# PCB_KioskMB_r3_2.net
KiCad netlist of a schematic drawn in EAGLE
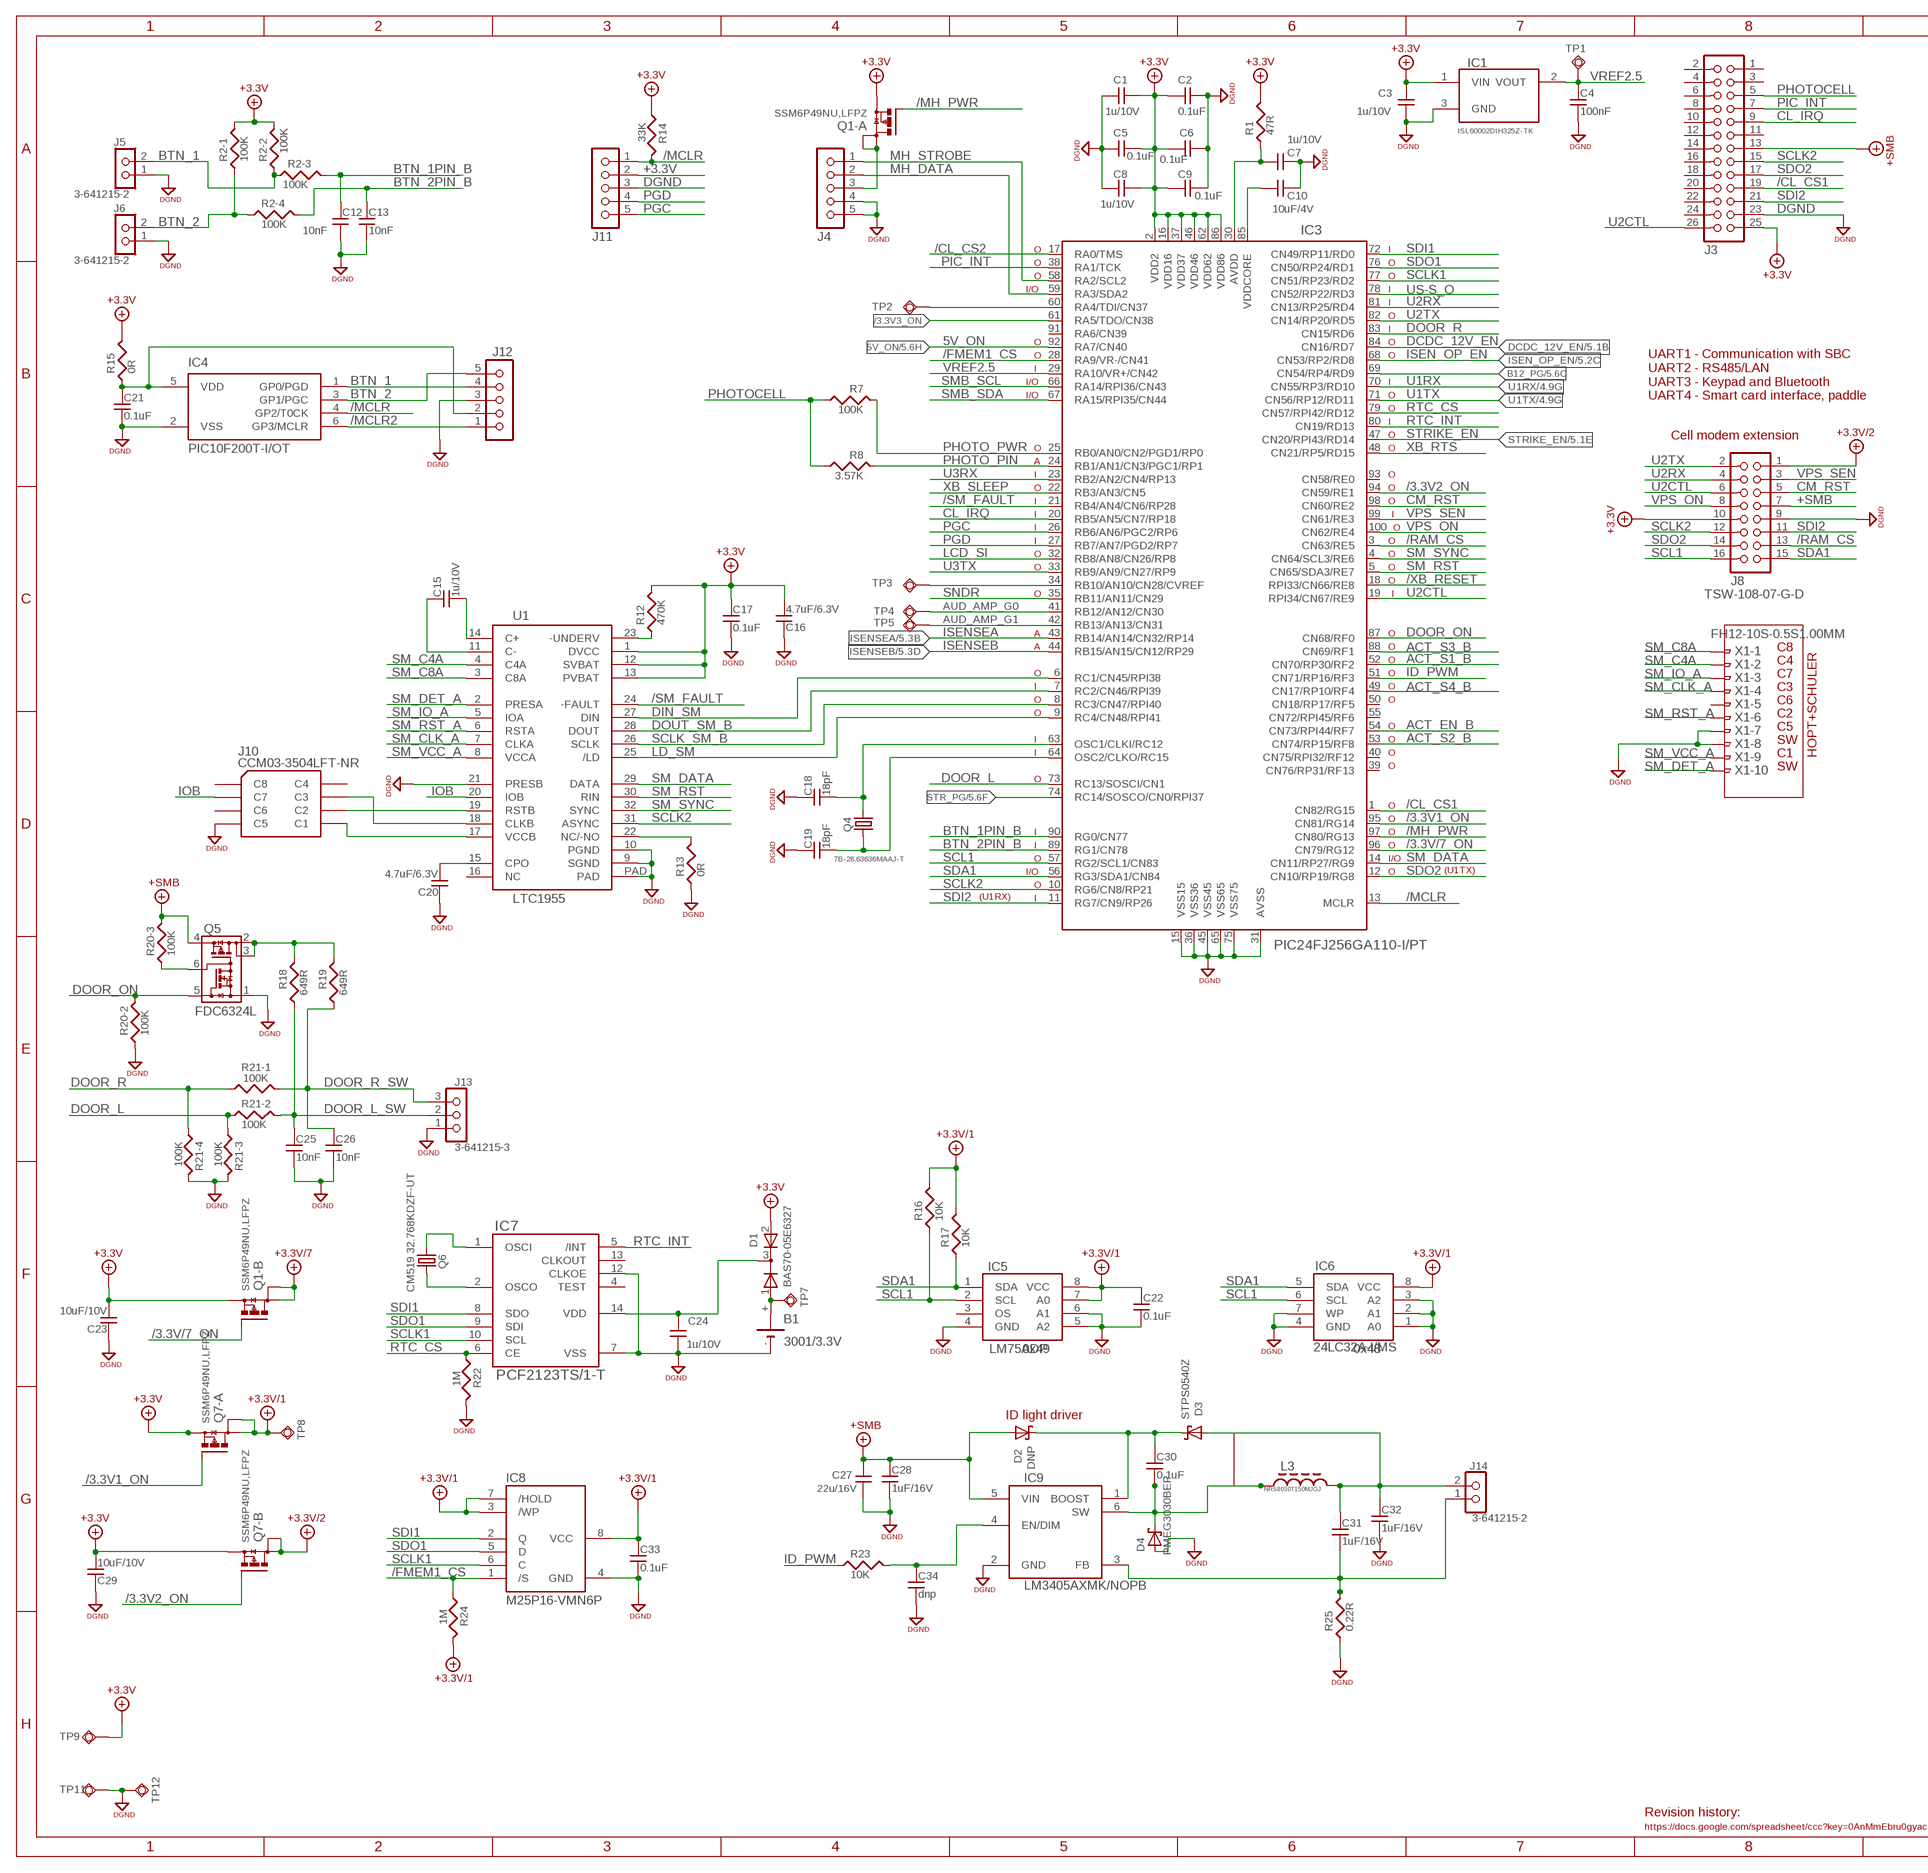
[diagram p0: schematic, sheet 1, part 1 of 2]
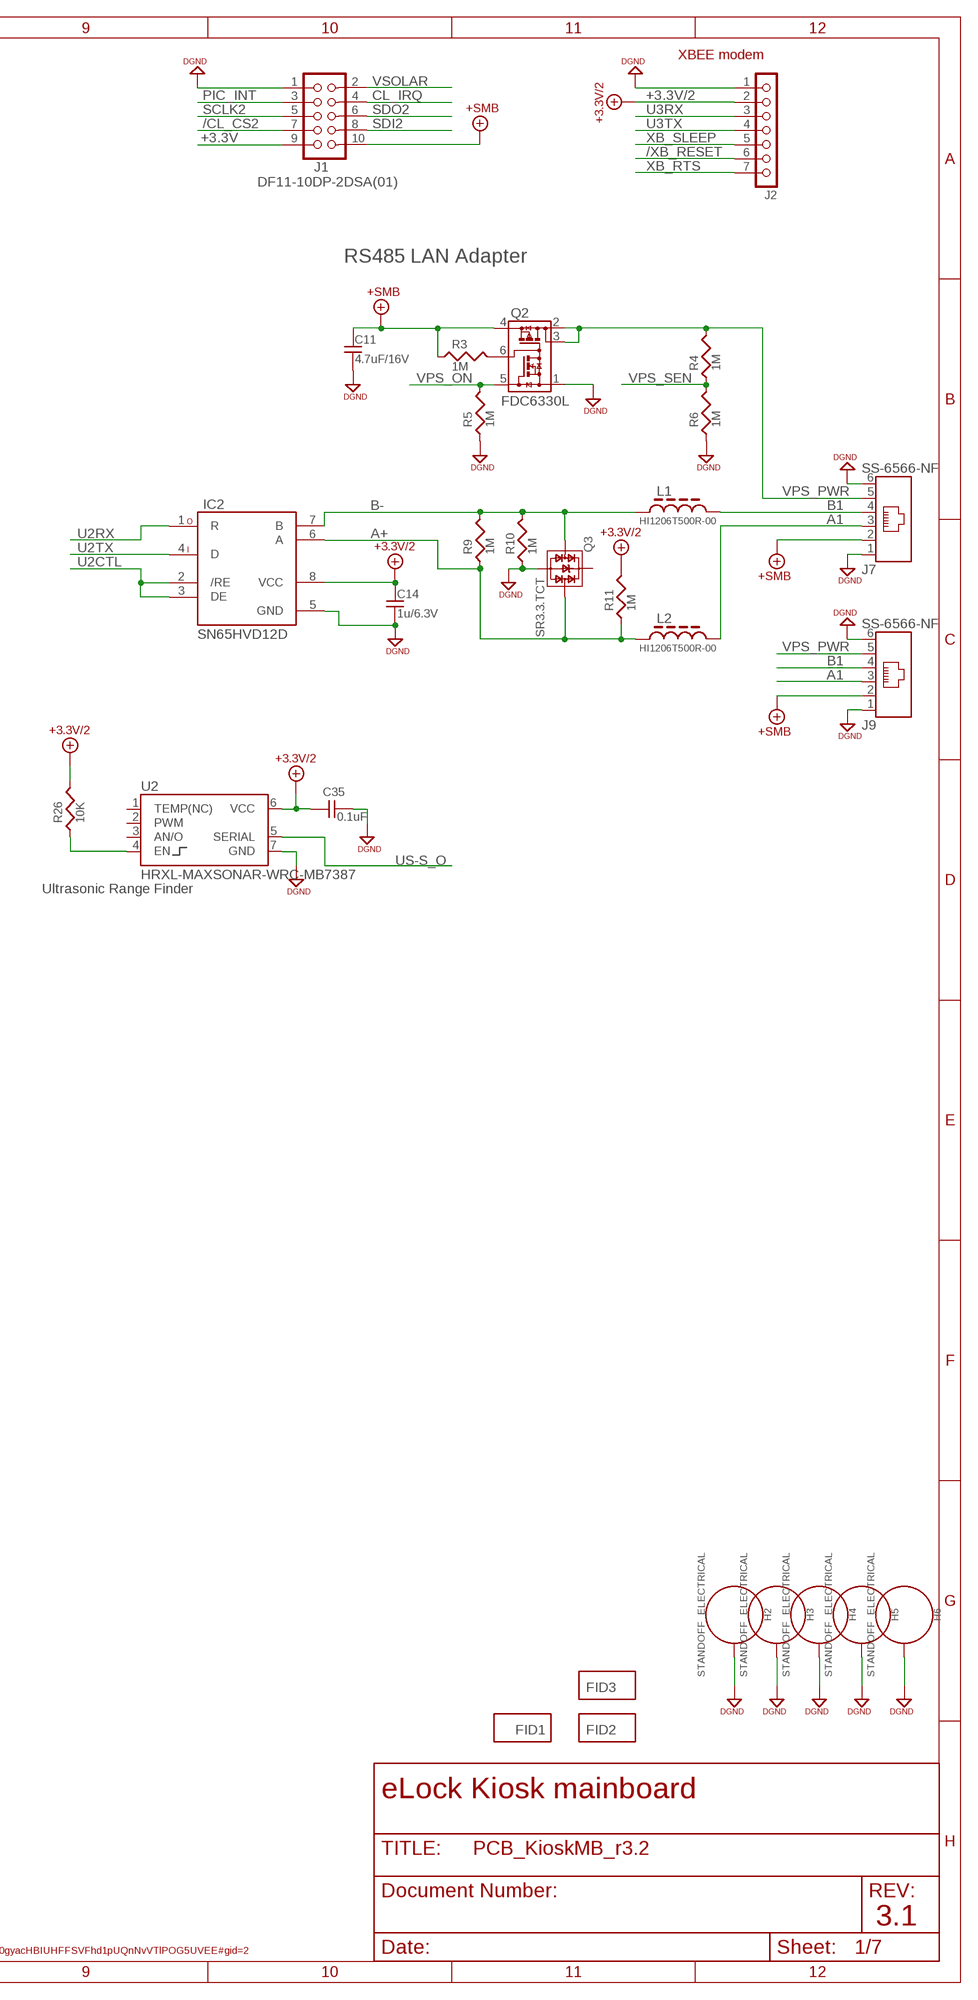
[diagram p1: schematic, sheet 1, part 2 of 2]
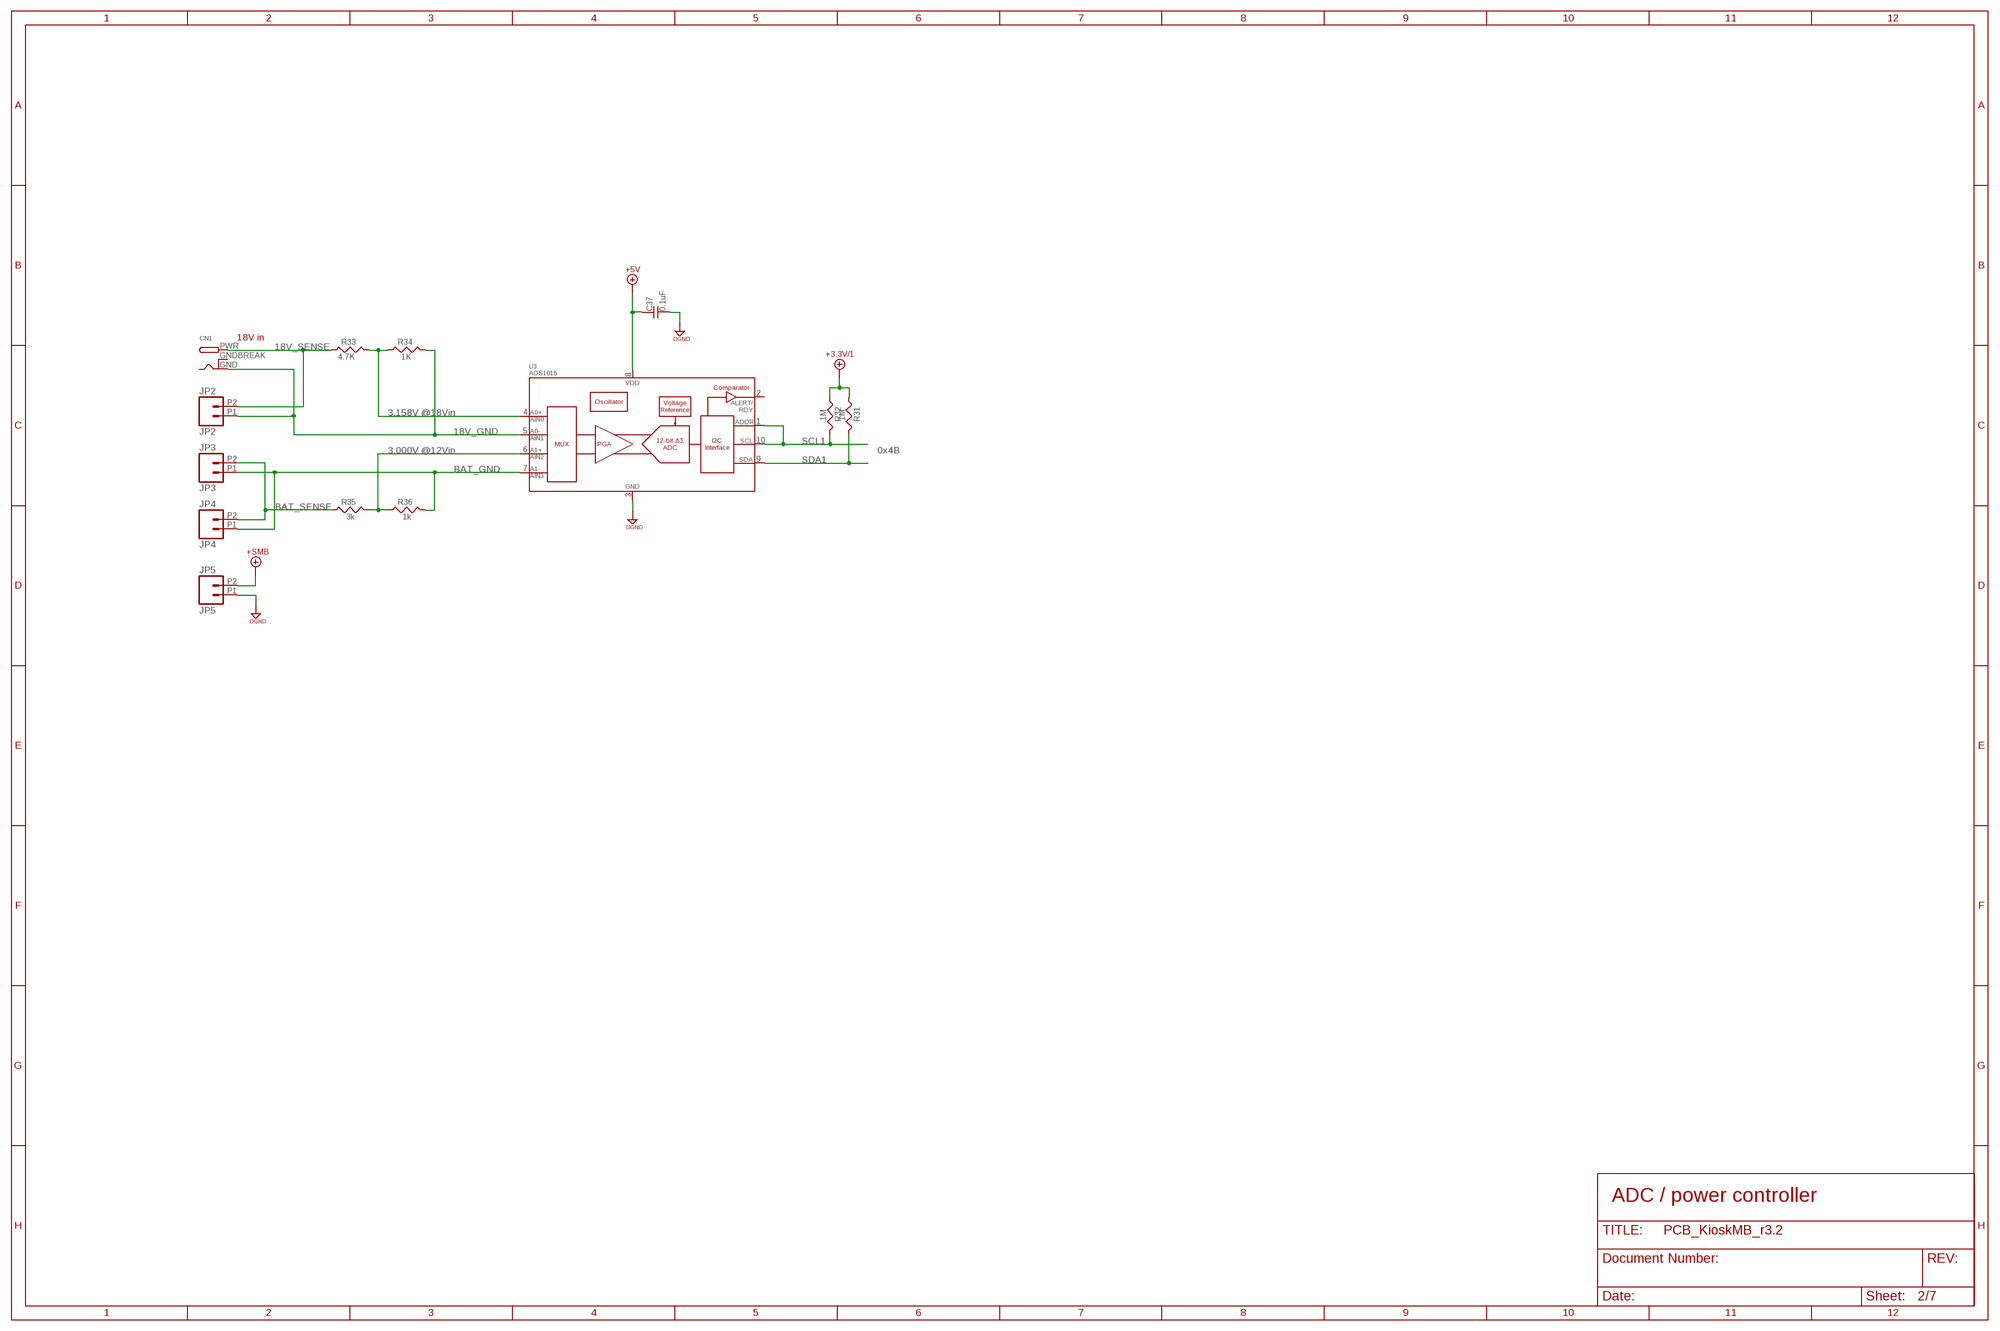
[diagram p2: schematic, sheet 2]
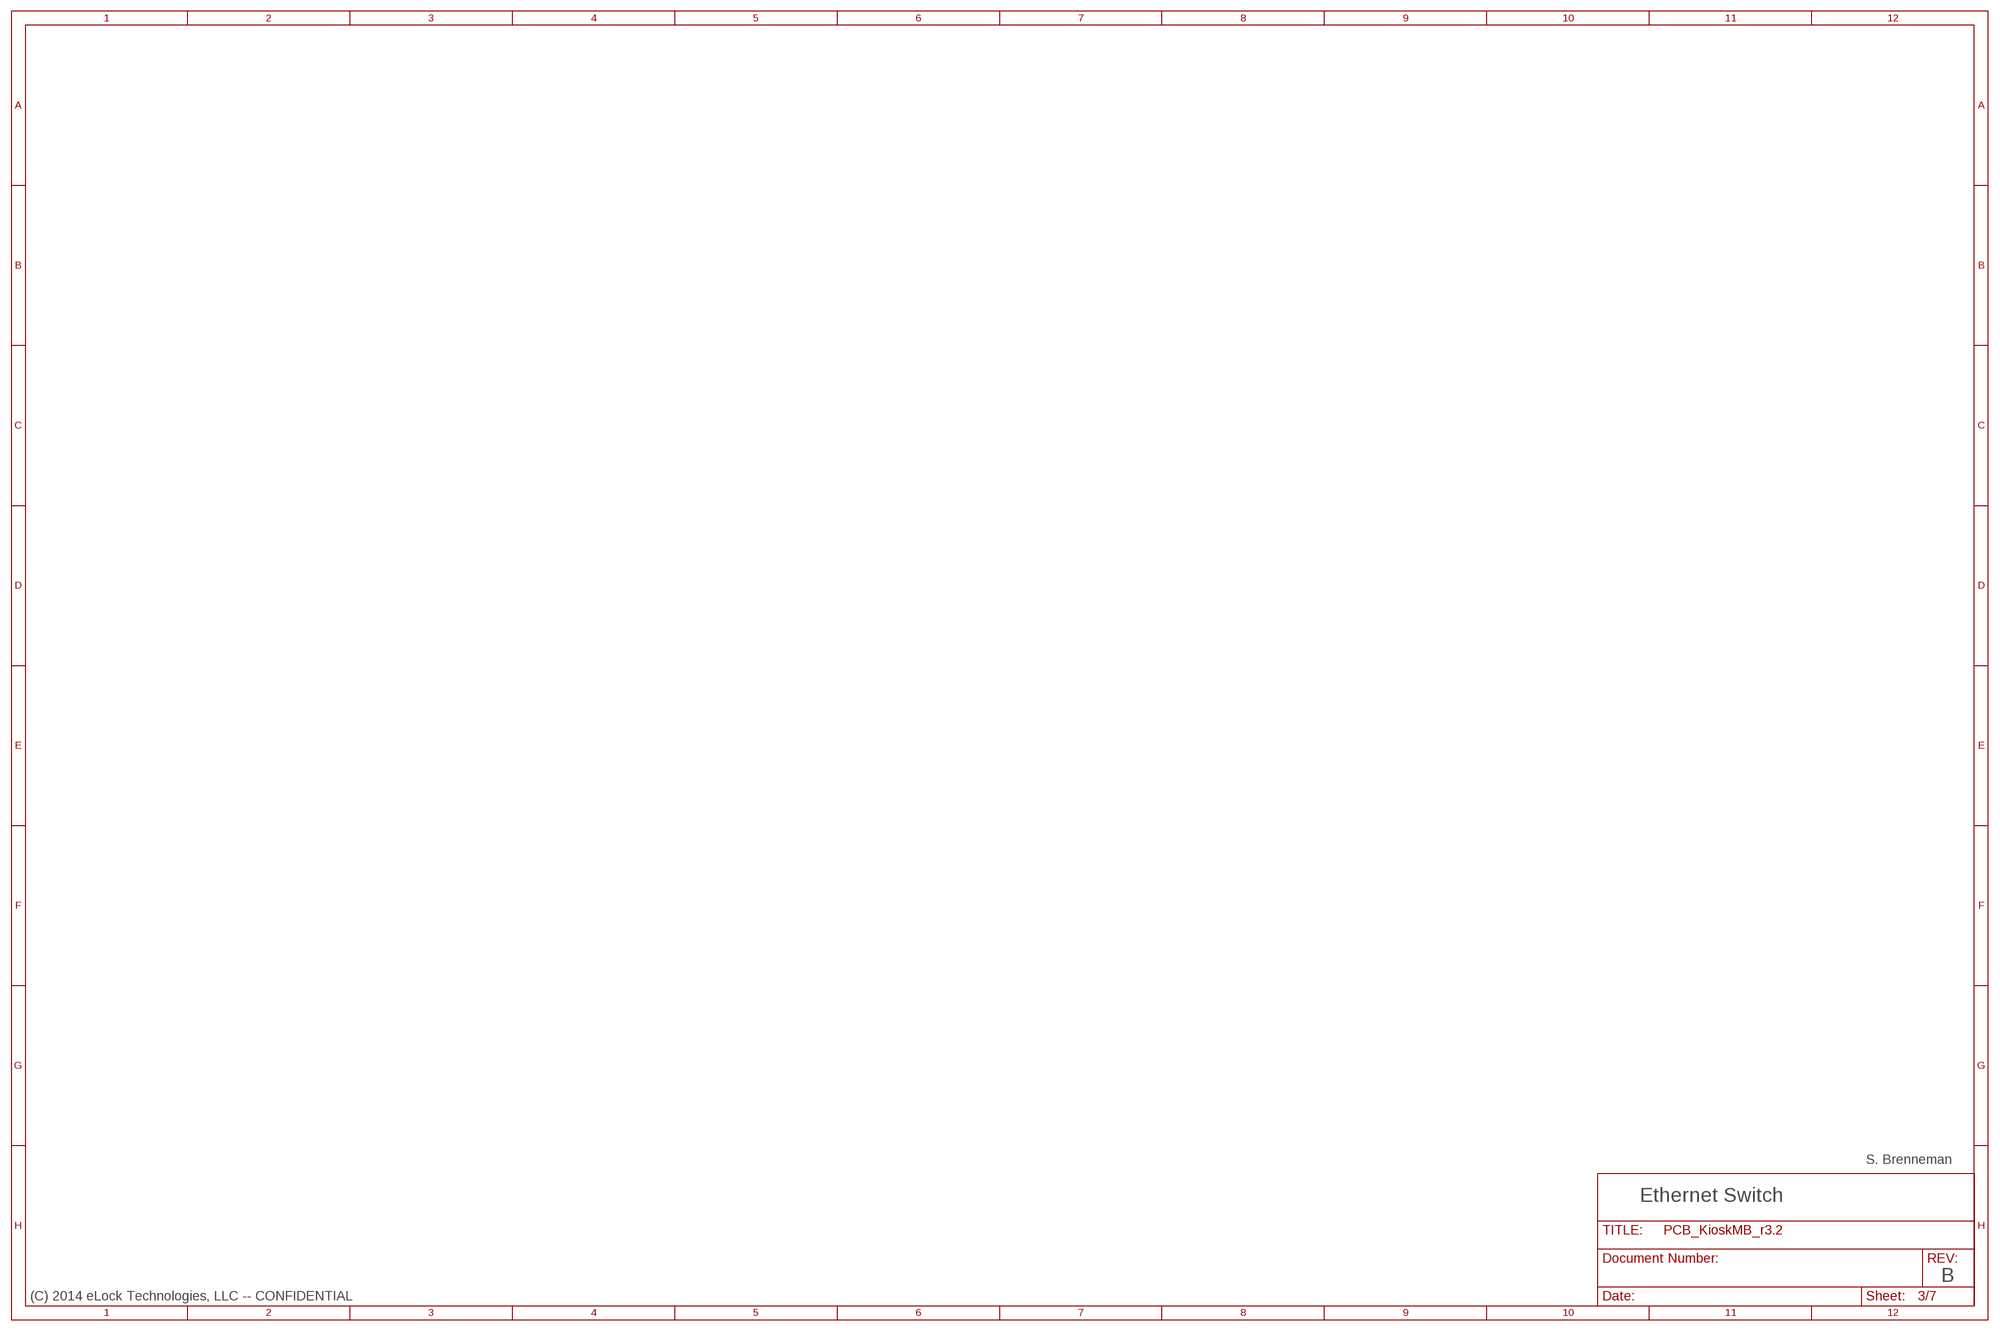
[diagram p3: schematic, sheet 3]
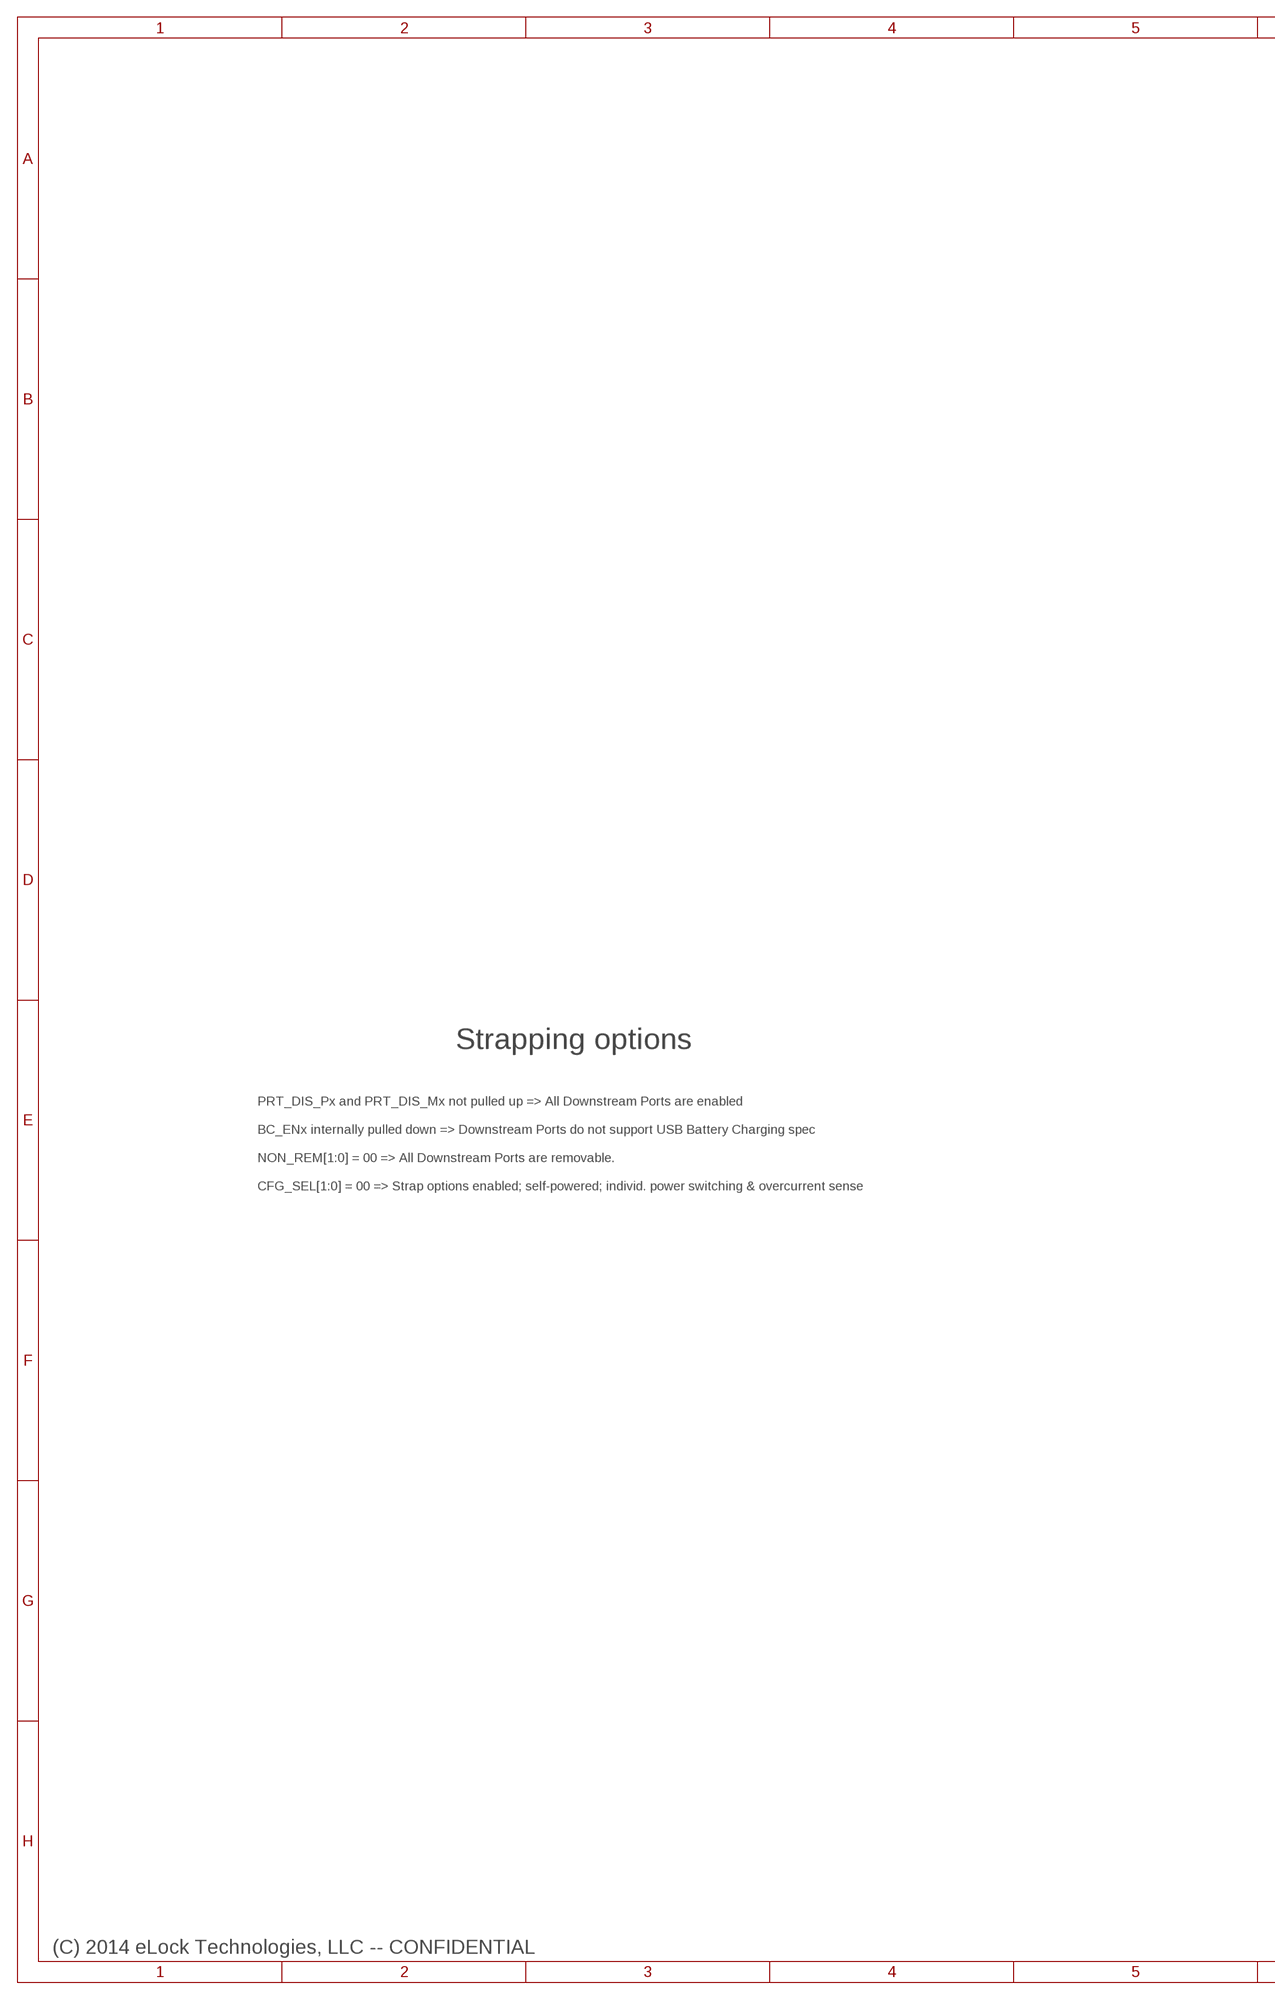
[diagram p4: schematic, sheet 4, part 1 of 2]
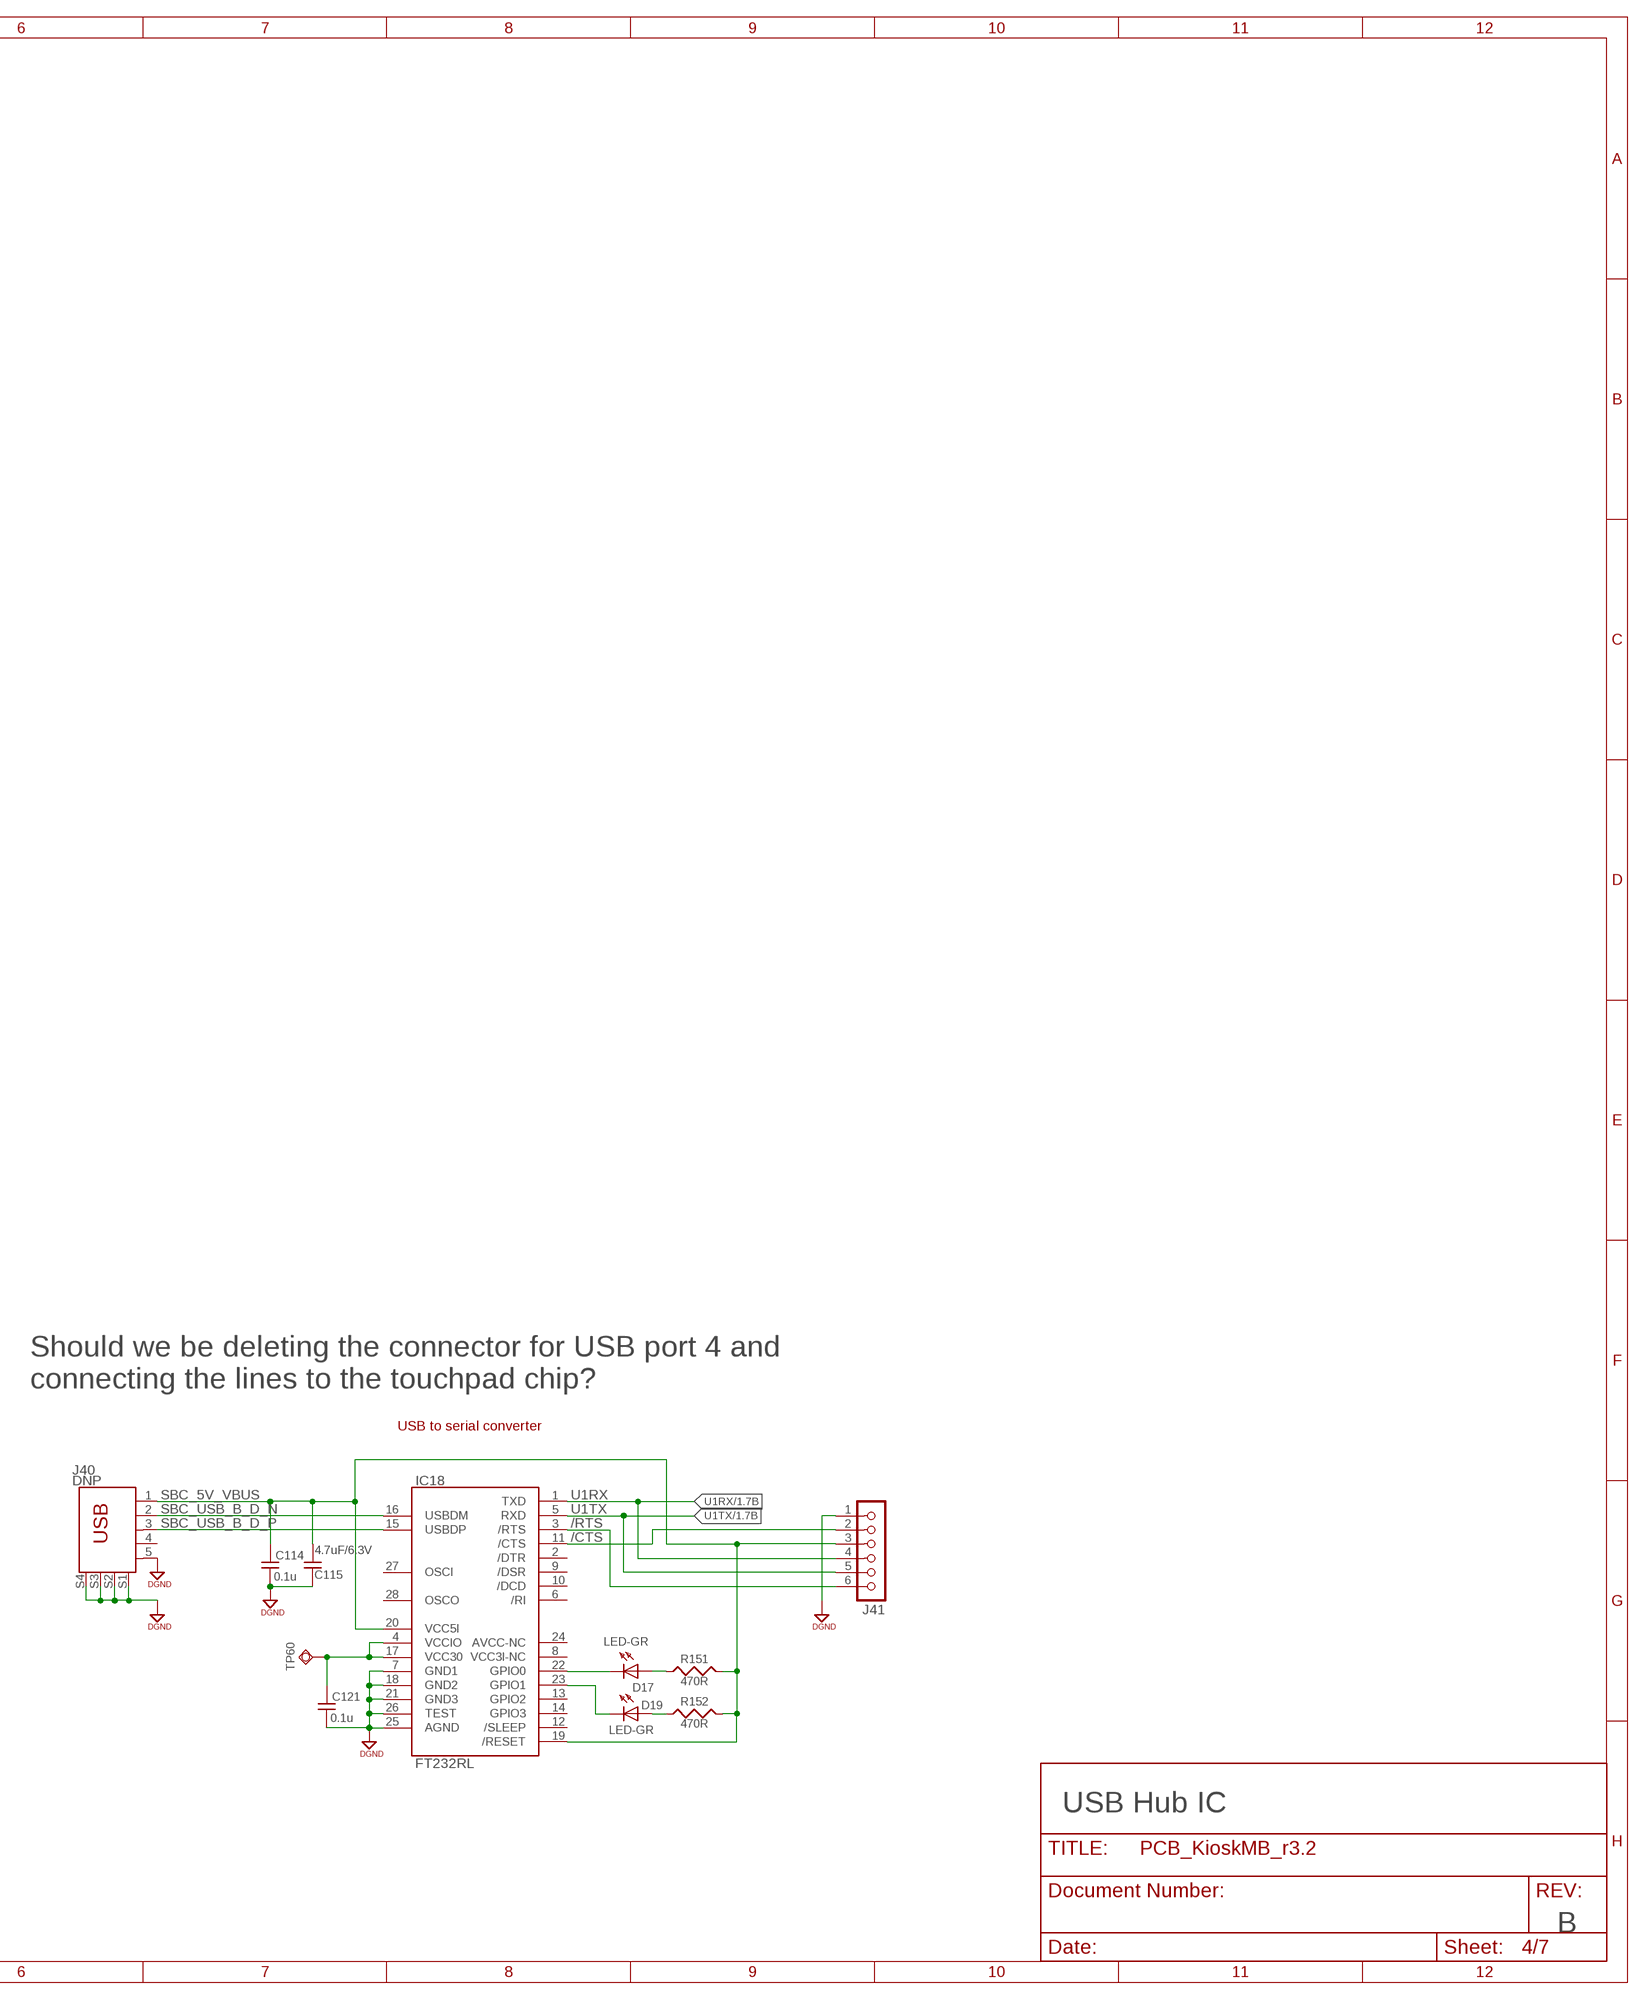
[diagram p5: schematic, sheet 4, part 2 of 2]
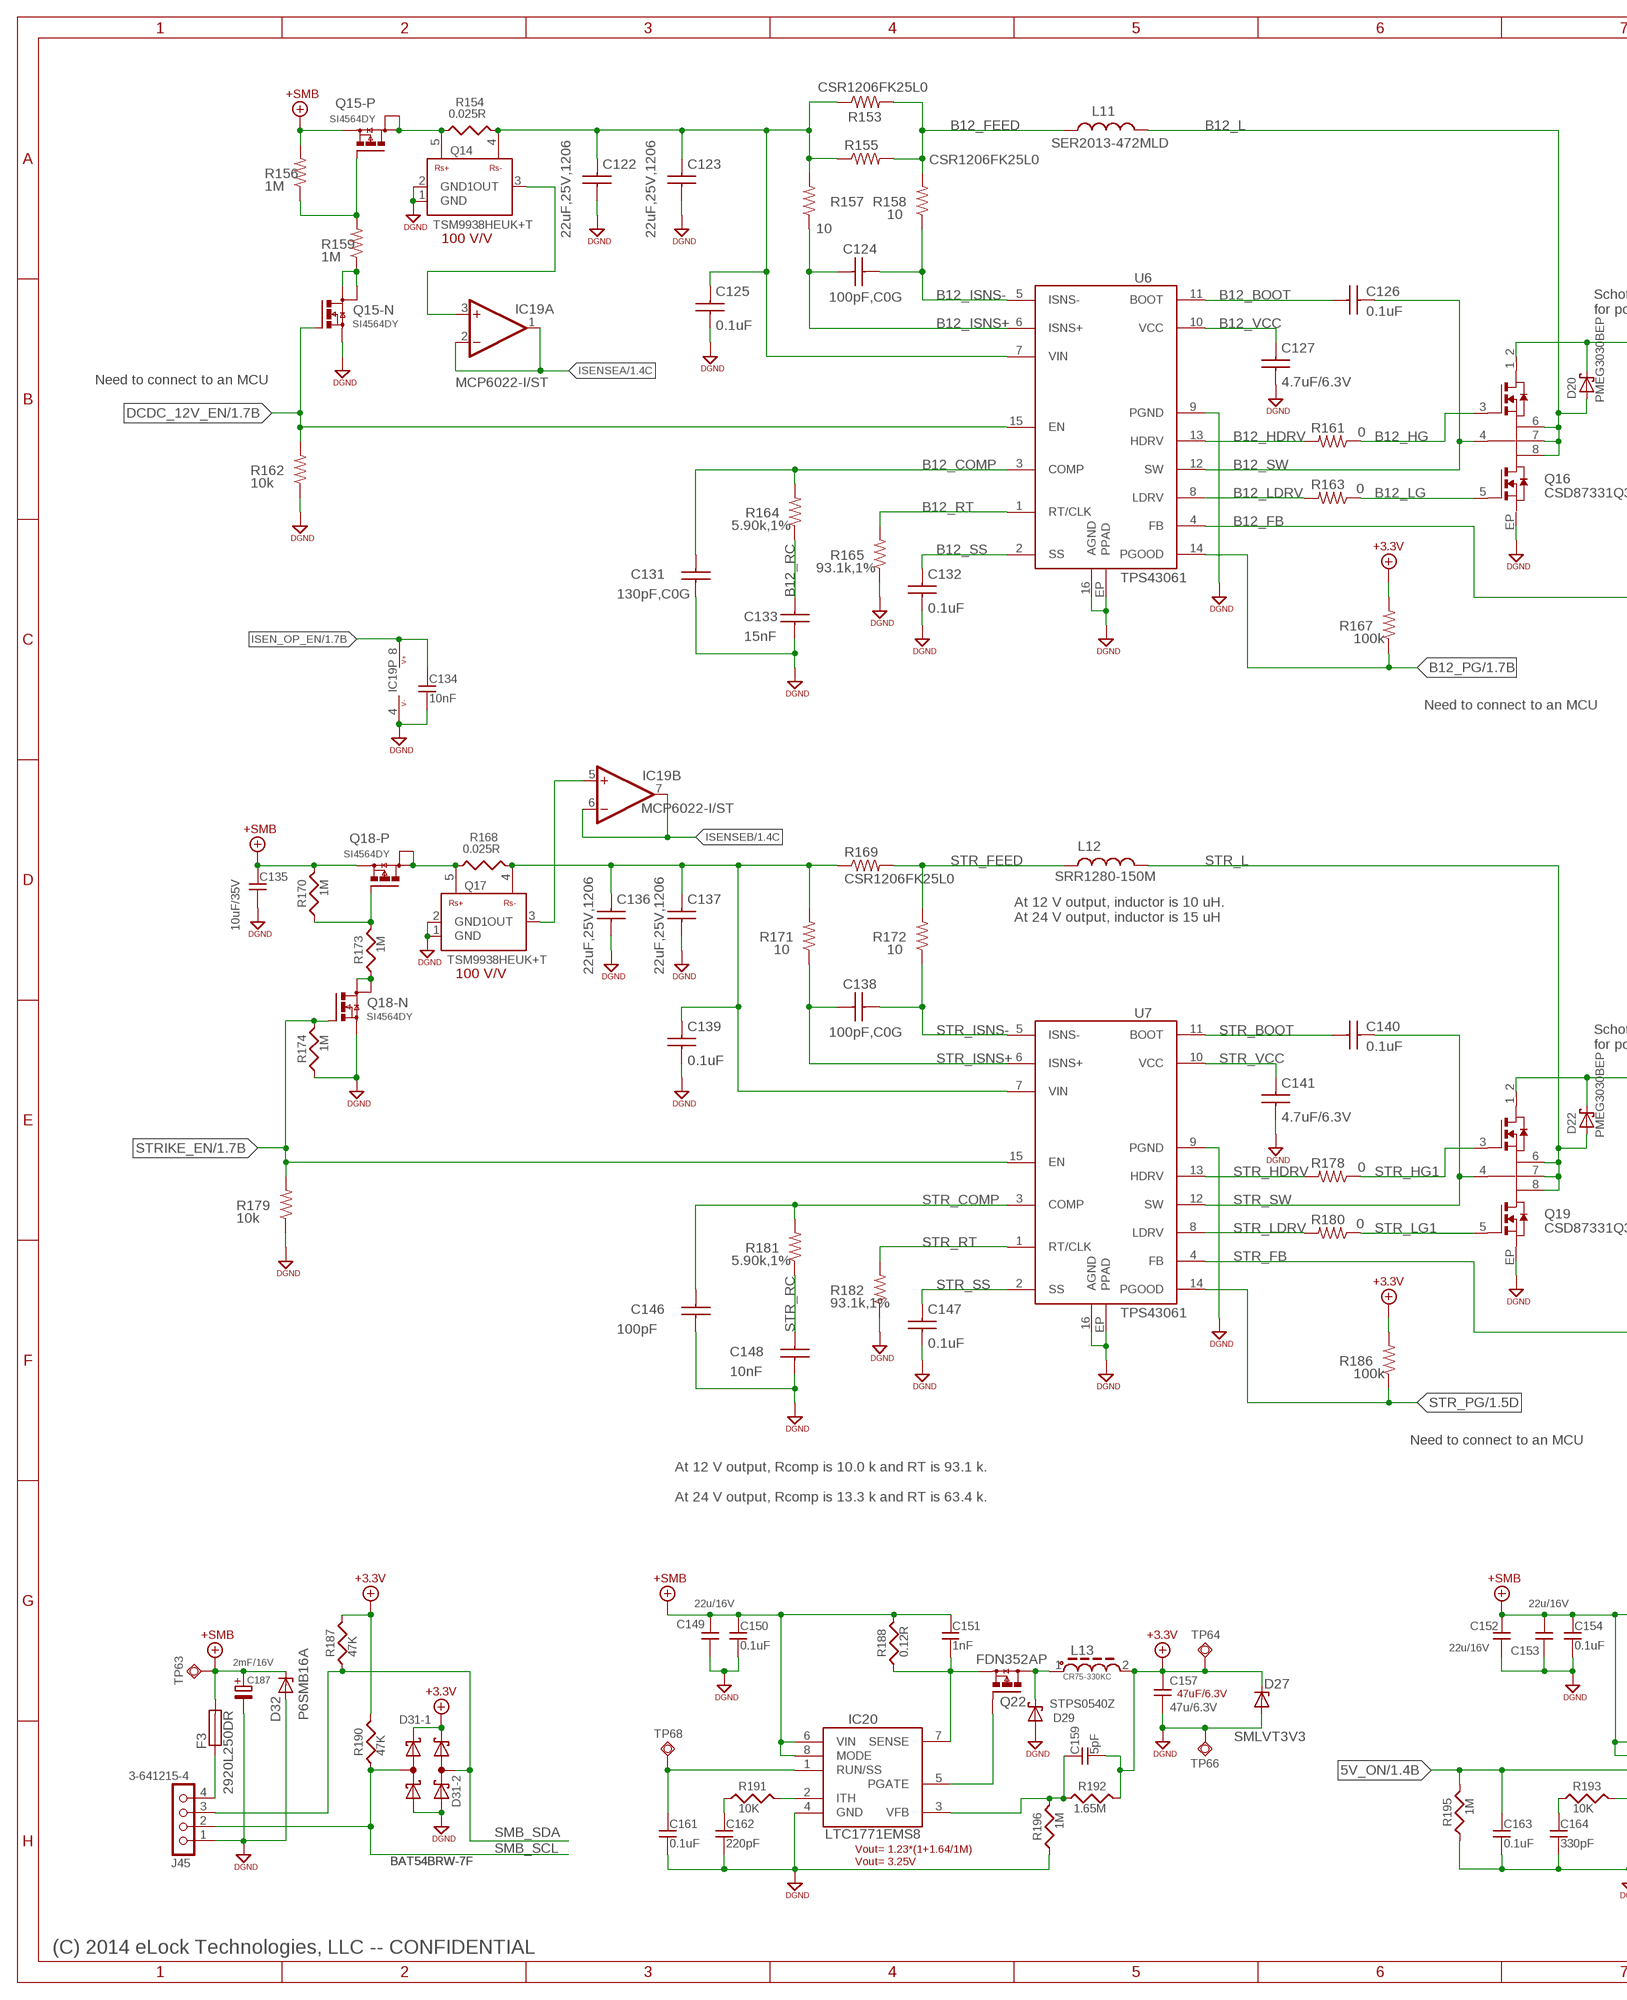
[diagram p6: schematic, sheet 5, part 1 of 2]
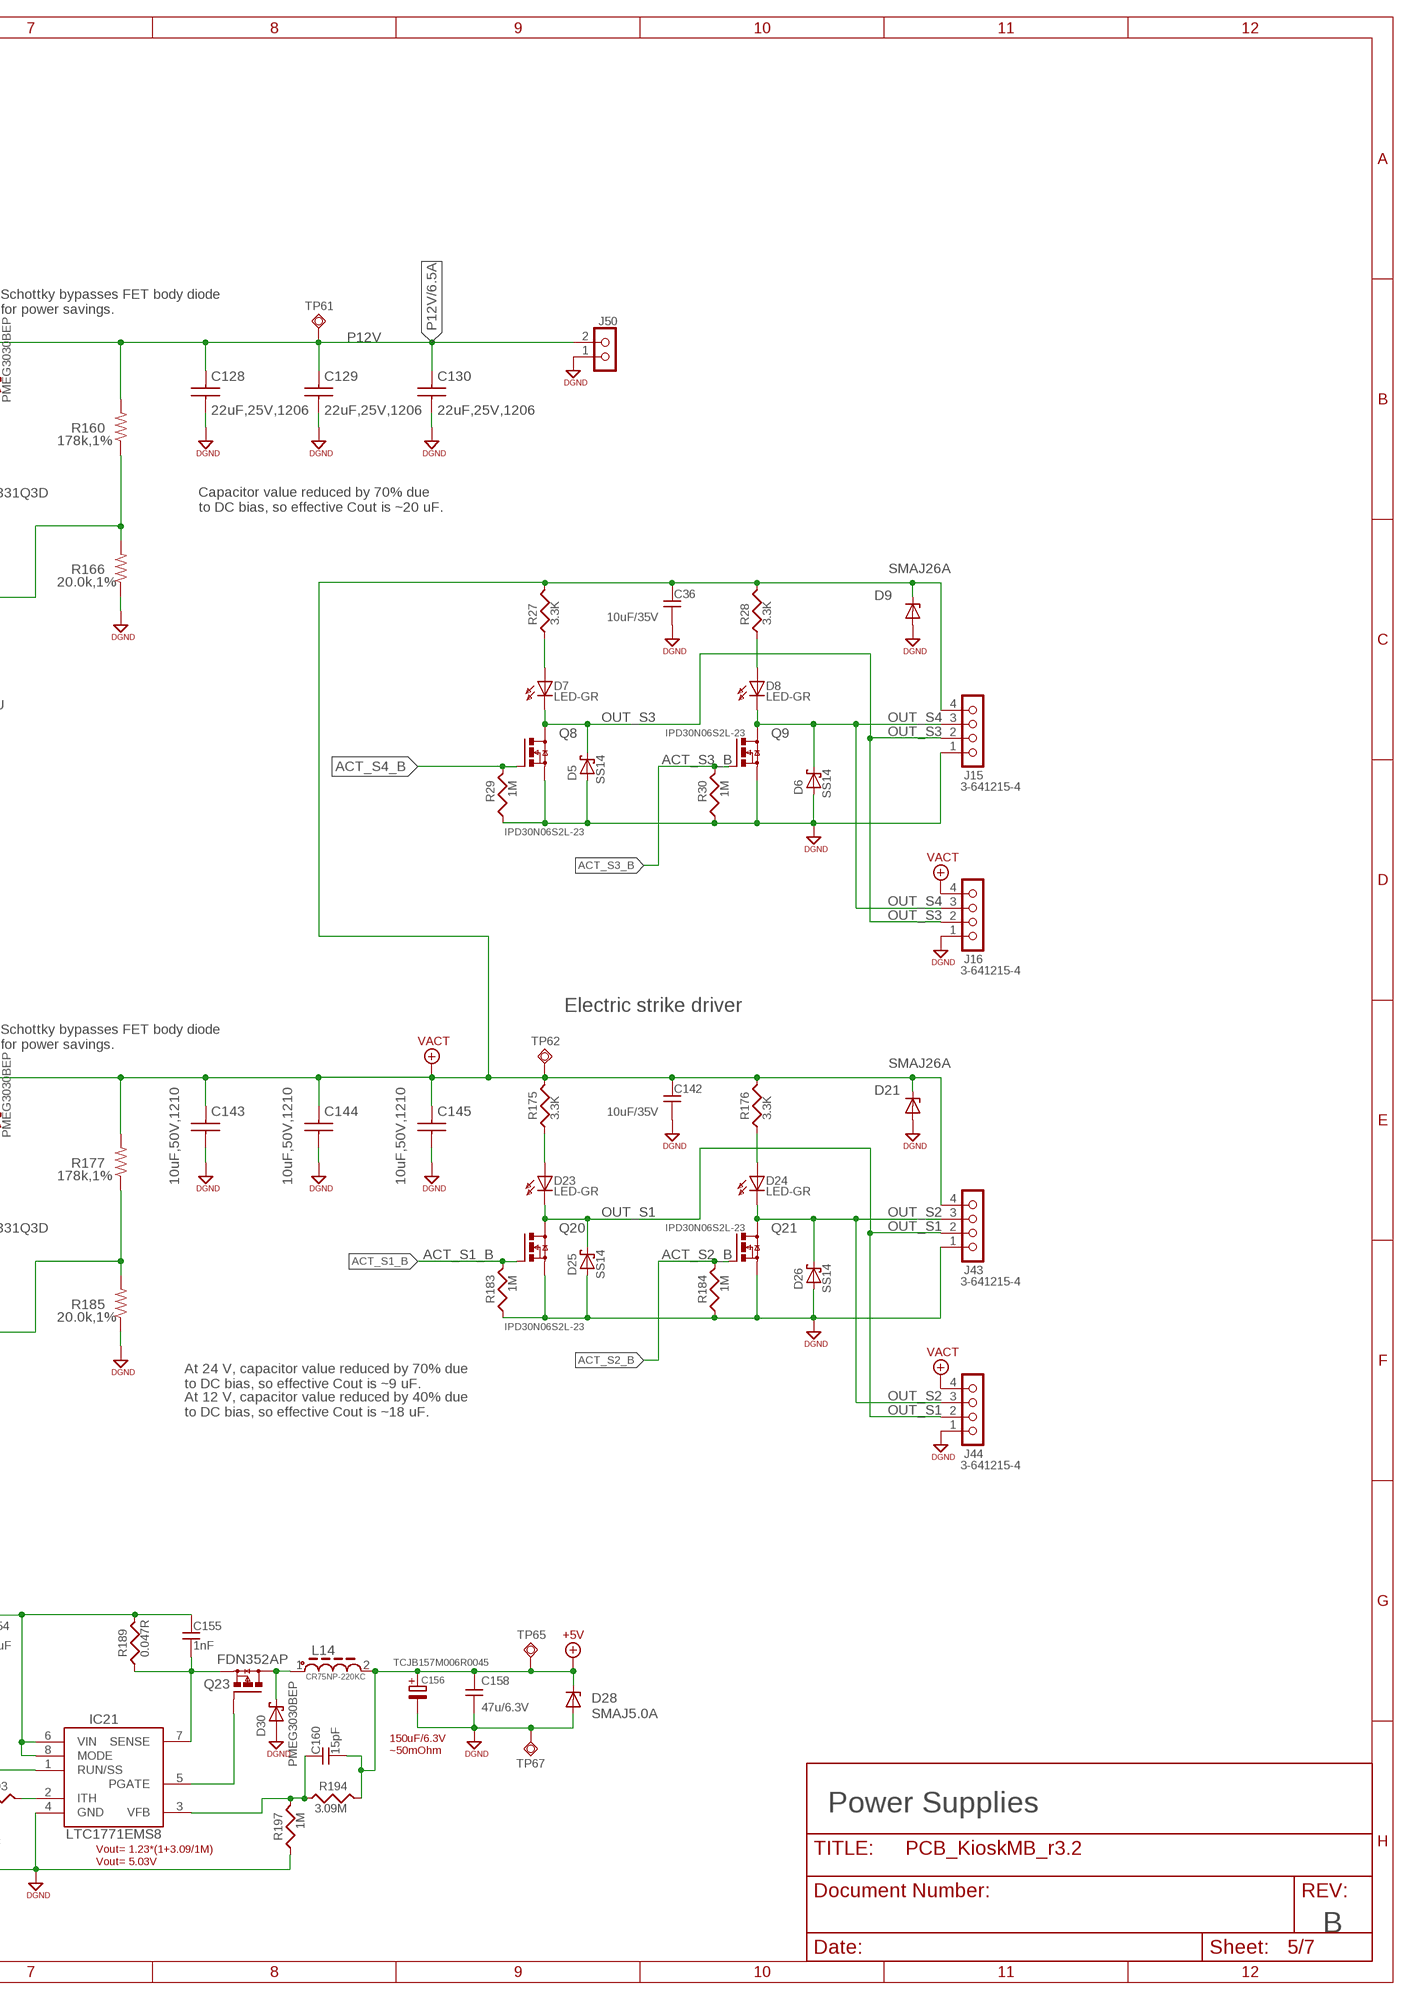
[diagram p7: schematic, sheet 5, part 2 of 2]
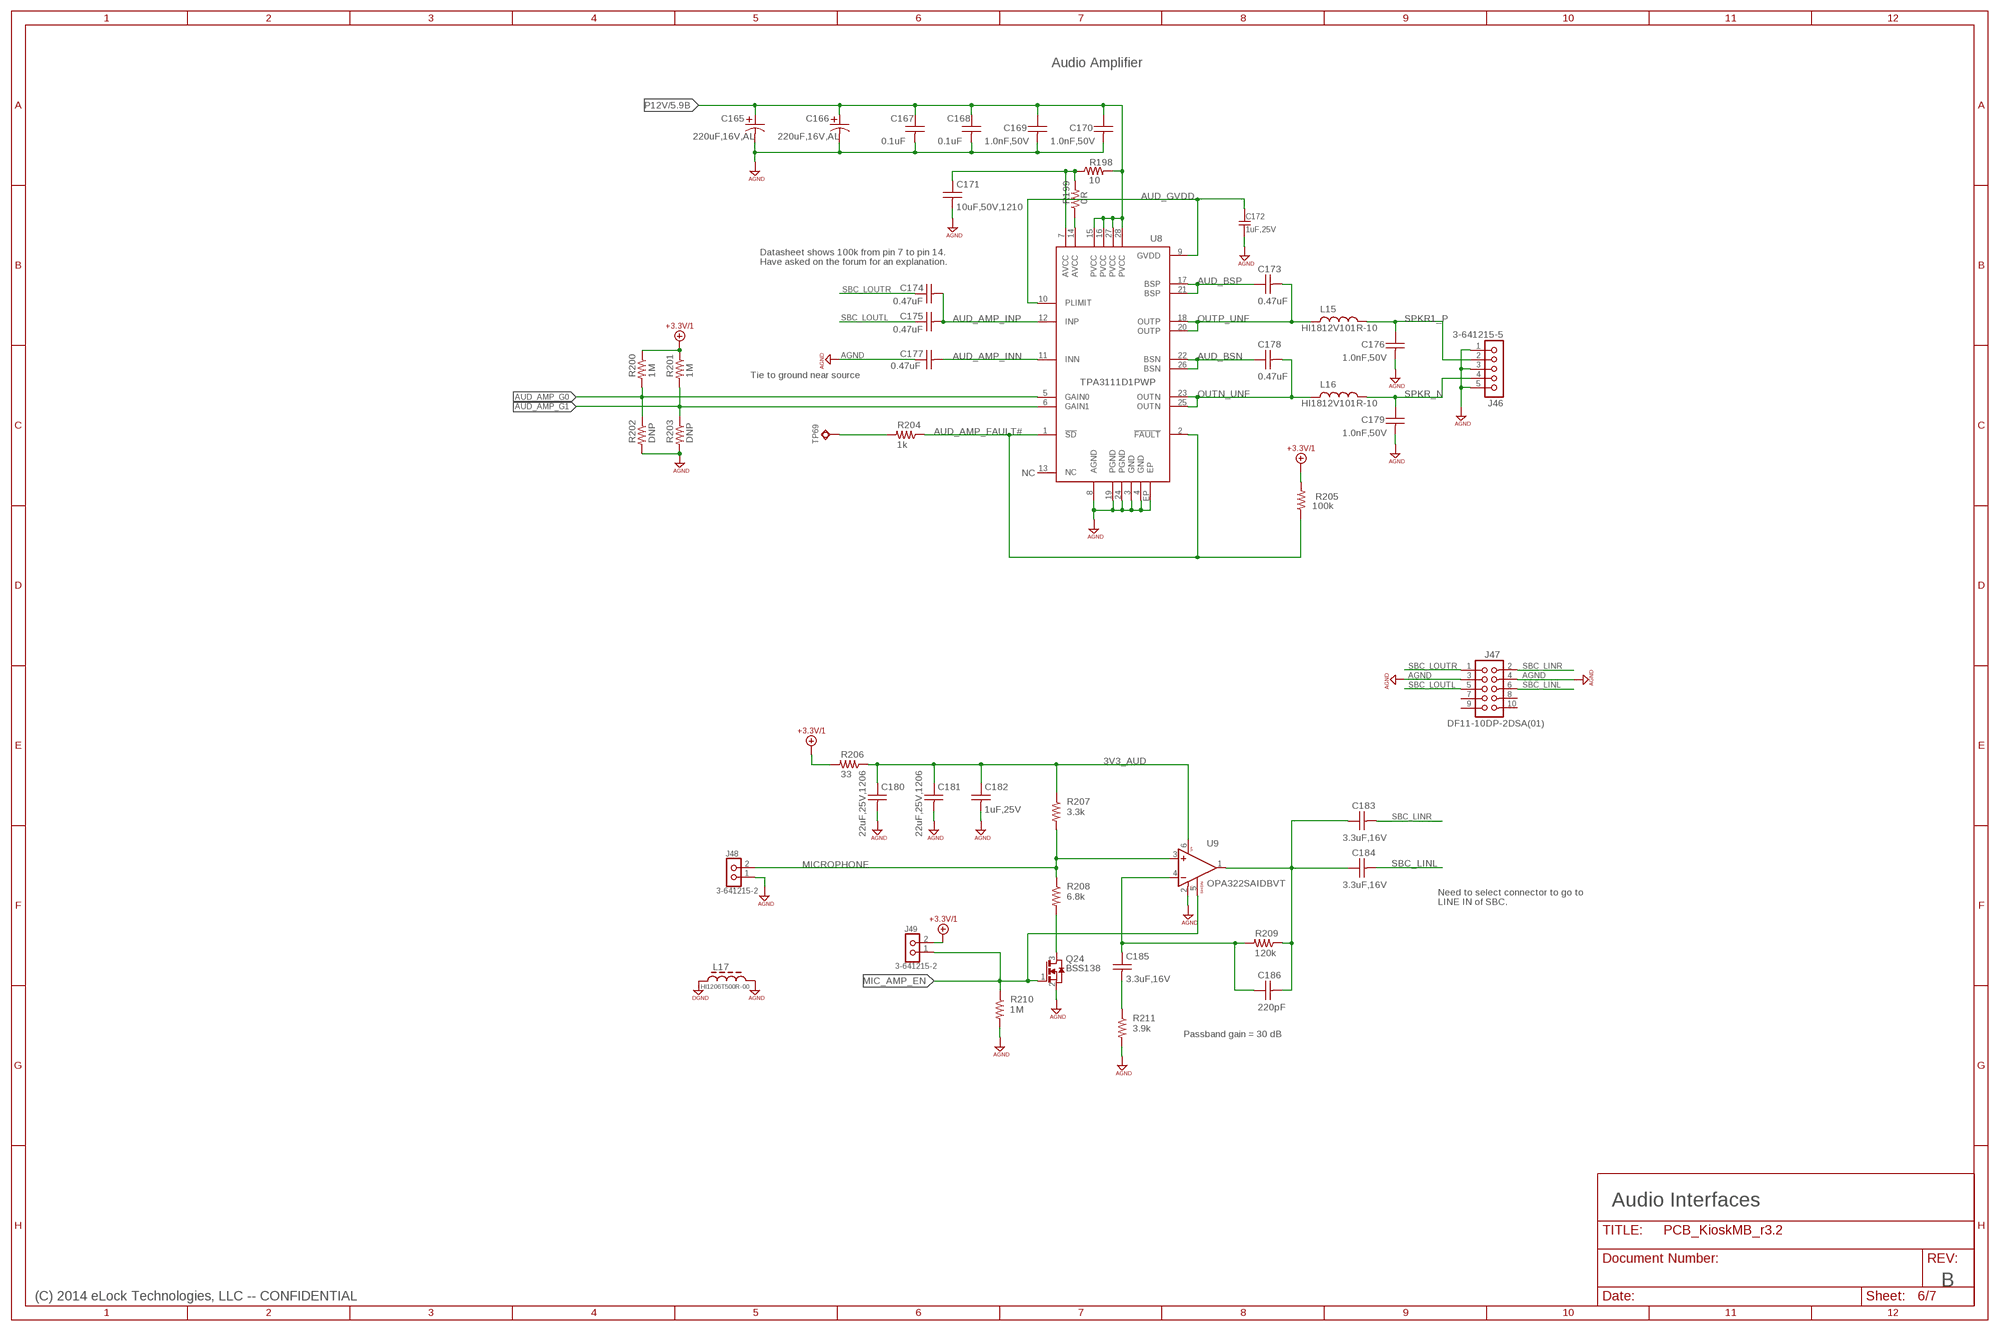
[diagram p8: schematic, sheet 6]
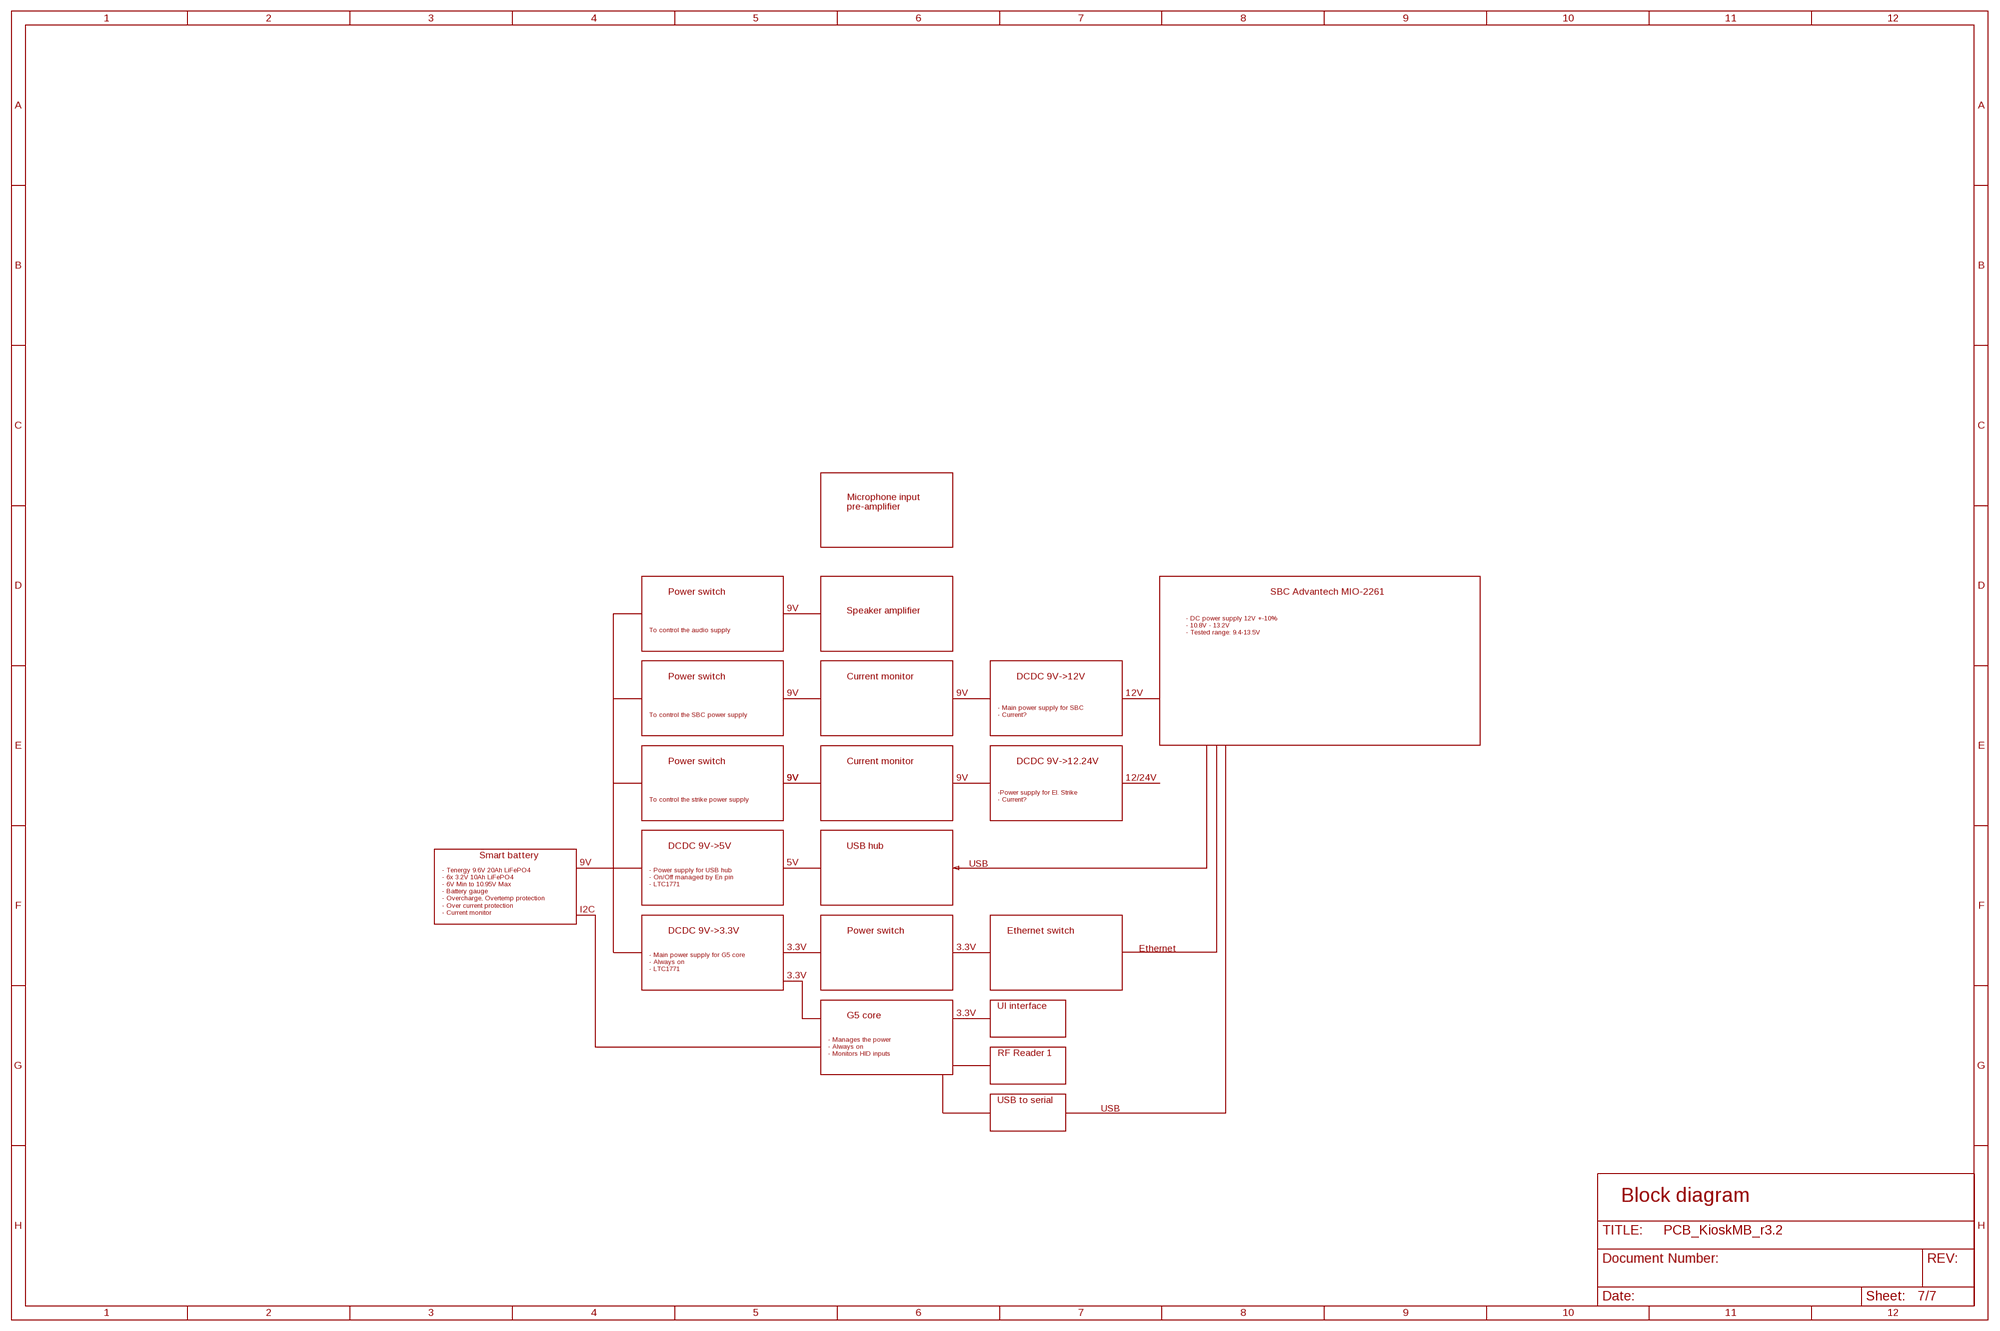
[diagram p9: schematic, sheet 7]

(export (version "E")
  (design (tool "Eeschema 10.0.6"))
  (components
    (comp (ref "C37")
      (value "0.1uF")
      (footprint "eagle-import:0603")
      (libsource (lib "eagle-import") (part "C-0603"))
    )
    (comp (ref "CN1")
      (value "DCBARRELPTH")
      (footprint "eagle-import:DCJACK_2MM_PTH")
      (libsource (lib "eagle-import") (part "DCBARRELPTH"))
    )
    (comp (ref "JP2")
      (value "M022.54MM_SCREWTERM")
      (footprint "eagle-import:1X02_2.54_SCREWTERM")
      (libsource (lib "eagle-import") (part "M022.54MM_SCREWTERM"))
    )
    (comp (ref "JP3")
      (value "M022.54MM_SCREWTERM")
      (footprint "eagle-import:1X02_2.54_SCREWTERM")
      (libsource (lib "eagle-import") (part "M022.54MM_SCREWTERM"))
    )
    (comp (ref "JP4")
      (value "M022.54MM_SCREWTERM")
      (footprint "eagle-import:1X02_2.54_SCREWTERM")
      (libsource (lib "eagle-import") (part "M022.54MM_SCREWTERM"))
    )
    (comp (ref "JP5")
      (value "M022.54MM_SCREWTERM")
      (footprint "eagle-import:1X02_2.54_SCREWTERM")
      (libsource (lib "eagle-import") (part "M022.54MM_SCREWTERM"))
    )
    (comp (ref "R31")
      (value "1M")
      (footprint "eagle-import:0603")
      (libsource (lib "eagle-import") (part "R-0603"))
    )
    (comp (ref "R32")
      (value "1M")
      (footprint "eagle-import:0603")
      (libsource (lib "eagle-import") (part "R-0603"))
    )
    (comp (ref "R33")
      (value "4.7K")
      (footprint "eagle-import:0603")
      (libsource (lib "eagle-import") (part "R-0603"))
    )
    (comp (ref "R34")
      (value "1K")
      (footprint "eagle-import:0603")
      (libsource (lib "eagle-import") (part "R-0603"))
    )
    (comp (ref "R35")
      (value "3k")
      (footprint "eagle-import:0603")
      (libsource (lib "eagle-import") (part "R-0603"))
    )
    (comp (ref "R36")
      (value "1k")
      (footprint "eagle-import:0603")
      (libsource (lib "eagle-import") (part "R-0603"))
    )
    (comp (ref "U3")
      (value "ADS1015")
      (footprint "eagle-import:MSOP10")
      (libsource (lib "eagle-import") (part "ADS1015"))
    )
    (comp (ref "C114")
      (value "0.1u")
      (footprint "eagle-import:0603")
      (libsource (lib "eagle-import") (part "C-0603"))
    )
    (comp (ref "C115")
      (value "4.7uF/6.3V")
      (footprint "eagle-import:0603")
      (libsource (lib "eagle-import") (part "C-0603"))
    )
    (comp (ref "C121")
      (value "0.1u")
      (footprint "eagle-import:0603")
      (libsource (lib "eagle-import") (part "C-0603"))
    )
    (comp (ref "D17")
      (value "LED-GR")
      (footprint "eagle-import:0805-POL")
      (libsource (lib "eagle-import") (part "LED-0805"))
    )
    (comp (ref "D19")
      (value "LED-GR")
      (footprint "eagle-import:0805-POL")
      (libsource (lib "eagle-import") (part "LED-0805"))
    )
    (comp (ref "IC18")
      (value "FT232RL")
      (footprint "eagle-import:SSOP28DB")
      (libsource (lib "eagle-import") (part "FT232RL"))
    )
    (comp (ref "J40")
      (value "DNP")
      (footprint "eagle-import:UX60")
      (libsource (lib "eagle-import") (part "UX60-MB-5ST"))
    )
    (comp (ref "J41")
      (value "MA06-1")
      (footprint "eagle-import:MA06-1")
      (libsource (lib "eagle-import") (part "MA06-1"))
    )
    (comp (ref "R151")
      (value "470R")
      (footprint "eagle-import:0603")
      (libsource (lib "eagle-import") (part "R-0603"))
    )
    (comp (ref "R152")
      (value "470R")
      (footprint "eagle-import:0603")
      (libsource (lib "eagle-import") (part "R-0603"))
    )
    (comp (ref "TP60")
      (value "ROUND_SMD0.7MM")
      (footprint "eagle-import:SMD_ROUND_07MM")
      (libsource (lib "eagle-import") (part "ROUND_SMD0.7MM"))
    )
    (comp (ref "C36")
      (value "10uF/35V")
      (footprint "eagle-import:1206")
      (libsource (lib "eagle-import") (part "C-1206"))
    )
    (comp (ref "C122")
      (value "22uF,25V,1206")
      (footprint "eagle-import:C1206")
      (fields (field (name "MANUFACTURER") "Samsung"))
      (libsource (lib "eagle-import") (part "C-US-NP1206"))
    )
    (comp (ref "C123")
      (value "22uF,25V,1206")
      (footprint "eagle-import:C1206")
      (fields (field (name "MANUFACTURER") "Samsung"))
      (libsource (lib "eagle-import") (part "C-US-NP1206"))
    )
    (comp (ref "C124")
      (value "100pF,C0G")
      (footprint "eagle-import:C0603")
      (fields (field (name "MANUFACTURER") "Samsung"))
      (libsource (lib "eagle-import") (part "C-US-NP0603"))
    )
    (comp (ref "C125")
      (value "0.1uF")
      (footprint "eagle-import:C0603")
      (fields (field (name "MANUFACTURER") "Murata"))
      (libsource (lib "eagle-import") (part "C-US-NP0603"))
    )
    (comp (ref "C126")
      (value "0.1uF")
      (footprint "eagle-import:C0603")
      (fields (field (name "MANUFACTURER") "Murata"))
      (libsource (lib "eagle-import") (part "C-US-NP0603"))
    )
    (comp (ref "C127")
      (value "4.7uF/6.3V")
      (footprint "eagle-import:C0603")
      (fields (field (name "MANUFACTURER") "Samsung"))
      (libsource (lib "eagle-import") (part "C-US-NP0603"))
    )
    (comp (ref "C128")
      (value "22uF,25V,1206")
      (footprint "eagle-import:C1206")
      (fields (field (name "MANUFACTURER") "Samsung"))
      (libsource (lib "eagle-import") (part "C-US-NP1206"))
    )
    (comp (ref "C129")
      (value "22uF,25V,1206")
      (footprint "eagle-import:C1206")
      (fields (field (name "MANUFACTURER") "Samsung"))
      (libsource (lib "eagle-import") (part "C-US-NP1206"))
    )
    (comp (ref "C130")
      (value "22uF,25V,1206")
      (footprint "eagle-import:C1206")
      (fields (field (name "MANUFACTURER") "Samsung"))
      (libsource (lib "eagle-import") (part "C-US-NP1206"))
    )
    (comp (ref "C131")
      (value "130pF,C0G")
      (footprint "eagle-import:C0603")
      (fields (field (name "MANUFACTURER") "Samsung"))
      (libsource (lib "eagle-import") (part "C-US-NP0603"))
    )
    (comp (ref "C132")
      (value "0.1uF")
      (footprint "eagle-import:C0603")
      (fields (field (name "MANUFACTURER") "Murata"))
      (libsource (lib "eagle-import") (part "C-US-NP0603"))
    )
    (comp (ref "C133")
      (value "15nF")
      (footprint "eagle-import:C0603")
      (fields (field (name "MANUFACTURER") "Samsung"))
      (libsource (lib "eagle-import") (part "C-US-NP0603"))
    )
    (comp (ref "C134")
      (value "10nF")
      (footprint "eagle-import:0603")
      (libsource (lib "eagle-import") (part "C-0603"))
    )
    (comp (ref "C135")
      (value "10uF/35V")
      (footprint "eagle-import:1206")
      (libsource (lib "eagle-import") (part "C-1206"))
    )
    (comp (ref "C136")
      (value "22uF,25V,1206")
      (footprint "eagle-import:C1206")
      (fields (field (name "MANUFACTURER") "Samsung"))
      (libsource (lib "eagle-import") (part "C-US-NP1206"))
    )
    (comp (ref "C137")
      (value "22uF,25V,1206")
      (footprint "eagle-import:C1206")
      (fields (field (name "MANUFACTURER") "Samsung"))
      (libsource (lib "eagle-import") (part "C-US-NP1206"))
    )
    (comp (ref "C138")
      (value "100pF,C0G")
      (footprint "eagle-import:C0603")
      (fields (field (name "MANUFACTURER") "Samsung"))
      (libsource (lib "eagle-import") (part "C-US-NP0603"))
    )
    (comp (ref "C139")
      (value "0.1uF")
      (footprint "eagle-import:C0603")
      (fields (field (name "MANUFACTURER") "Murata"))
      (libsource (lib "eagle-import") (part "C-US-NP0603"))
    )
    (comp (ref "C140")
      (value "0.1uF")
      (footprint "eagle-import:C0603")
      (fields (field (name "MANUFACTURER") "Murata"))
      (libsource (lib "eagle-import") (part "C-US-NP0603"))
    )
    (comp (ref "C141")
      (value "4.7uF/6.3V")
      (footprint "eagle-import:C0603")
      (fields (field (name "MANUFACTURER") "Samsung"))
      (libsource (lib "eagle-import") (part "C-US-NP0603"))
    )
    (comp (ref "C142")
      (value "10uF/35V")
      (footprint "eagle-import:1206")
      (libsource (lib "eagle-import") (part "C-1206"))
    )
    (comp (ref "C143")
      (value "10uF,50V,1210")
      (footprint "eagle-import:C1210")
      (fields (field (name "MANUFACTURER") "Samsung"))
      (libsource (lib "eagle-import") (part "C-US-NP1210"))
    )
    (comp (ref "C144")
      (value "10uF,50V,1210")
      (footprint "eagle-import:C1210")
      (fields (field (name "MANUFACTURER") "Samsung"))
      (libsource (lib "eagle-import") (part "C-US-NP1210"))
    )
    (comp (ref "C145")
      (value "10uF,50V,1210")
      (footprint "eagle-import:C1210")
      (fields (field (name "MANUFACTURER") "Samsung"))
      (libsource (lib "eagle-import") (part "C-US-NP1210"))
    )
    (comp (ref "C146")
      (value "100pF")
      (footprint "eagle-import:C0603")
      (fields (field (name "MANUFACTURER") "Samsung"))
      (libsource (lib "eagle-import") (part "C-US-NP0603"))
    )
    (comp (ref "C147")
      (value "0.1uF")
      (footprint "eagle-import:C0603")
      (fields (field (name "MANUFACTURER") "Murata"))
      (libsource (lib "eagle-import") (part "C-US-NP0603"))
    )
    (comp (ref "C148")
      (value "10nF")
      (footprint "eagle-import:C0603")
      (fields (field (name "MANUFACTURER") "Samsung"))
      (libsource (lib "eagle-import") (part "C-US-NP0603"))
    )
    (comp (ref "C149")
      (value "22u/16V")
      (footprint "eagle-import:1210")
      (libsource (lib "eagle-import") (part "C-1210"))
    )
    (comp (ref "C150")
      (value "0.1uF")
      (footprint "eagle-import:0603")
      (libsource (lib "eagle-import") (part "C-0603"))
    )
    (comp (ref "C151")
      (value "1nF")
      (footprint "eagle-import:0603")
      (libsource (lib "eagle-import") (part "C-0603"))
    )
    (comp (ref "C152")
      (value "22u/16V")
      (footprint "eagle-import:1210")
      (libsource (lib "eagle-import") (part "C-1210"))
    )
    (comp (ref "C153")
      (value "22u/16V")
      (footprint "eagle-import:1210")
      (libsource (lib "eagle-import") (part "C-1210"))
    )
    (comp (ref "C154")
      (value "0.1uF")
      (footprint "eagle-import:0603")
      (libsource (lib "eagle-import") (part "C-0603"))
    )
    (comp (ref "C155")
      (value "1nF")
      (footprint "eagle-import:0603")
      (libsource (lib "eagle-import") (part "C-0603"))
    )
    (comp (ref "C156")
      (value "TCJB157M006R0045")
      (footprint "eagle-import:3528-POL")
      (libsource (lib "eagle-import") (part "C-POL-3528"))
    )
    (comp (ref "C157")
      (value "47u/6.3V")
      (footprint "eagle-import:1210")
      (libsource (lib "eagle-import") (part "C-1210"))
    )
    (comp (ref "C158")
      (value "47u/6.3V")
      (footprint "eagle-import:1210")
      (libsource (lib "eagle-import") (part "C-1210"))
    )
    (comp (ref "C159")
      (value "5pF")
      (footprint "eagle-import:0603")
      (libsource (lib "eagle-import") (part "C-0603"))
    )
    (comp (ref "C160")
      (value "15pF")
      (footprint "eagle-import:0603")
      (libsource (lib "eagle-import") (part "C-0603"))
    )
    (comp (ref "C161")
      (value "0.1uF")
      (footprint "eagle-import:0603")
      (libsource (lib "eagle-import") (part "C-0603"))
    )
    (comp (ref "C162")
      (value "220pF")
      (footprint "eagle-import:0603")
      (libsource (lib "eagle-import") (part "C-0603"))
    )
    (comp (ref "C163")
      (value "0.1uF")
      (footprint "eagle-import:0603")
      (libsource (lib "eagle-import") (part "C-0603"))
    )
    (comp (ref "C164")
      (value "330pF")
      (footprint "eagle-import:0603")
      (libsource (lib "eagle-import") (part "C-0603"))
    )
    (comp (ref "C187")
      (value "2mF/16V")
      (footprint "eagle-import:ES-7,5")
      (libsource (lib "eagle-import") (part "ELC-7,5"))
    )
    (comp (ref "D5")
      (value "SS14")
      (footprint "eagle-import:SMA")
      (libsource (lib "eagle-import") (part "SS14"))
    )
    (comp (ref "D6")
      (value "SS14")
      (footprint "eagle-import:SMA")
      (libsource (lib "eagle-import") (part "SS14"))
    )
    (comp (ref "D7")
      (value "LED-GR")
      (footprint "eagle-import:0805-POL")
      (libsource (lib "eagle-import") (part "LED-0805"))
    )
    (comp (ref "D8")
      (value "LED-GR")
      (footprint "eagle-import:0805-POL")
      (libsource (lib "eagle-import") (part "LED-0805"))
    )
    (comp (ref "D9")
      (value "SMAJ26A")
      (footprint "eagle-import:SMA")
      (libsource (lib "eagle-import") (part "SMAJ5.0A"))
    )
    (comp (ref "D20")
      (value "PMEG3030BEP")
      (footprint "eagle-import:SOD-128")
      (libsource (lib "eagle-import") (part "PMEG3030BEP"))
    )
    (comp (ref "D21")
      (value "SMAJ26A")
      (footprint "eagle-import:SMA")
      (libsource (lib "eagle-import") (part "SMAJ5.0A"))
    )
    (comp (ref "D22")
      (value "PMEG3030BEP")
      (footprint "eagle-import:SOD-128")
      (libsource (lib "eagle-import") (part "PMEG3030BEP"))
    )
    (comp (ref "D23")
      (value "LED-GR")
      (footprint "eagle-import:0805-POL")
      (libsource (lib "eagle-import") (part "LED-0805"))
    )
    (comp (ref "D24")
      (value "LED-GR")
      (footprint "eagle-import:0805-POL")
      (libsource (lib "eagle-import") (part "LED-0805"))
    )
    (comp (ref "D25")
      (value "SS14")
      (footprint "eagle-import:SMA")
      (libsource (lib "eagle-import") (part "SS14"))
    )
    (comp (ref "D26")
      (value "SS14")
      (footprint "eagle-import:SMA")
      (libsource (lib "eagle-import") (part "SS14"))
    )
    (comp (ref "D27")
      (value "SMLVT3V3")
      (footprint "eagle-import:SMA")
      (libsource (lib "eagle-import") (part "SMLVT3V3"))
    )
    (comp (ref "D28")
      (value "SMAJ5.0A")
      (footprint "eagle-import:SMA")
      (libsource (lib "eagle-import") (part "SMAJ5.0A"))
    )
    (comp (ref "D29")
      (value "STPS0540Z")
      (footprint "eagle-import:SOD-123")
      (libsource (lib "eagle-import") (part "STPS0540Z"))
    )
    (comp (ref "D30")
      (value "PMEG3030BEP")
      (footprint "eagle-import:SOD-128")
      (libsource (lib "eagle-import") (part "PMEG3030BEP"))
    )
    (comp (ref "D31")
      (value "BAT54BRW-7F")
      (footprint "eagle-import:SOT-363")
      (libsource (lib "eagle-import") (part "BAT54BRW-7F"))
    )
    (comp (ref "D32")
      (value "P6SMB16A")
      (footprint "eagle-import:SMB")
      (libsource (lib "eagle-import") (part "P6SMB16A"))
    )
    (comp (ref "F3")
      (value "2920L250DR")
      (footprint "eagle-import:1812")
      (libsource (lib "eagle-import") (part "1812L014DR"))
    )
    (comp (ref "IC19")
      (value "MCP6022-I/ST")
      (footprint "eagle-import:TSSOP8")
      (libsource (lib "eagle-import") (part "MCP6022-I/ST"))
    )
    (comp (ref "IC20")
      (value "LTC1771EMS8")
      (footprint "eagle-import:MSOP-08")
      (libsource (lib "eagle-import") (part "LTC1771EMS8"))
    )
    (comp (ref "IC21")
      (value "LTC1771EMS8")
      (footprint "eagle-import:MSOP-08")
      (libsource (lib "eagle-import") (part "LTC1771EMS8"))
    )
    (comp (ref "J15")
      (value "3-641215-4")
      (footprint "eagle-import:3-641215-4")
      (libsource (lib "eagle-import") (part "3-641215-4"))
    )
    (comp (ref "J16")
      (value "3-641215-4")
      (footprint "eagle-import:3-641215-4")
      (libsource (lib "eagle-import") (part "3-641215-4"))
    )
    (comp (ref "J43")
      (value "3-641215-4")
      (footprint "eagle-import:3-641215-4")
      (libsource (lib "eagle-import") (part "3-641215-4"))
    )
    (comp (ref "J44")
      (value "3-641215-4")
      (footprint "eagle-import:3-641215-4")
      (libsource (lib "eagle-import") (part "3-641215-4"))
    )
    (comp (ref "J45")
      (value "3-641215-4")
      (footprint "eagle-import:3-641215-4")
      (libsource (lib "eagle-import") (part "3-641215-4"))
    )
    (comp (ref "J50")
      (value "TERM-2")
      (footprint "eagle-import:TERM-2")
      (libsource (lib "eagle-import") (part "TERM-2"))
    )
    (comp (ref "L11")
      (value "SER2013-472MLD")
      (footprint "eagle-import:L_SER20XX")
      (fields (field (name "MANUFACTURER") "Coilcraft"))
      (libsource (lib "eagle-import") (part "LSER20XX"))
    )
    (comp (ref "L12")
      (value "SRR1280-150M")
      (footprint "eagle-import:L_SRR1280")
      (fields (field (name "MANUFACTURER") "Bourns") (field (name "MFR_PN") "SRR1280-1x0M"))
      (libsource (lib "eagle-import") (part "LSRR1280"))
    )
    (comp (ref "L13")
      (value "CR75-330KC")
      (footprint "eagle-import:CR75")
      (libsource (lib "eagle-import") (part "CR75-330KC"))
    )
    (comp (ref "L14")
      (value "CR75NP-220KC")
      (footprint "eagle-import:CR75")
      (libsource (lib "eagle-import") (part "CR75-330KC"))
    )
    (comp (ref "Q8")
      (value "IPD30N06S2L-23")
      (footprint "eagle-import:TO252")
      (libsource (lib "eagle-import") (part "IPD30N06S2L-23"))
    )
    (comp (ref "Q9")
      (value "IPD30N06S2L-23")
      (footprint "eagle-import:TO252")
      (libsource (lib "eagle-import") (part "IPD30N06S2L-23"))
    )
    (comp (ref "Q14")
      (value "TSM9938HEUK+T")
      (footprint "eagle-import:SOT23-5")
      (libsource (lib "eagle-import") (part "TSM9938HEUK+T"))
    )
    (comp (ref "Q15")
      (value "SI4564DY")
      (footprint "eagle-import:SO-08")
      (libsource (lib "eagle-import") (part "SI4564DY"))
    )
    (comp (ref "Q16")
      (value "CSD87331Q3D")
      (footprint "eagle-import:SON8_3.3X3.3_TI")
      (fields (field (name "MANUFACTURER") "TI") (field (name "MFR_PN") "CSD87331Q3D"))
      (libsource (lib "eagle-import") (part "TRANS_DUAL_NFET_HALF-BRQ3D"))
    )
    (comp (ref "Q17")
      (value "TSM9938HEUK+T")
      (footprint "eagle-import:SOT23-5")
      (libsource (lib "eagle-import") (part "TSM9938HEUK+T"))
    )
    (comp (ref "Q18")
      (value "SI4564DY")
      (footprint "eagle-import:SO-08")
      (libsource (lib "eagle-import") (part "SI4564DY"))
    )
    (comp (ref "Q19")
      (value "CSD87331Q3D")
      (footprint "eagle-import:SON8_3.3X3.3_TI")
      (fields (field (name "MANUFACTURER") "TI") (field (name "MFR_PN") "CSD87331Q3D"))
      (libsource (lib "eagle-import") (part "TRANS_DUAL_NFET_HALF-BRQ3D"))
    )
    (comp (ref "Q20")
      (value "IPD30N06S2L-23")
      (footprint "eagle-import:TO252")
      (libsource (lib "eagle-import") (part "IPD30N06S2L-23"))
    )
    (comp (ref "Q21")
      (value "IPD30N06S2L-23")
      (footprint "eagle-import:TO252")
      (libsource (lib "eagle-import") (part "IPD30N06S2L-23"))
    )
    (comp (ref "Q22")
      (value "FDN352AP")
      (footprint "eagle-import:SOT-23")
      (libsource (lib "eagle-import") (part "FDN352AP"))
    )
    (comp (ref "Q23")
      (value "FDN352AP")
      (footprint "eagle-import:SOT-23")
      (libsource (lib "eagle-import") (part "FDN352AP"))
    )
    (comp (ref "R27")
      (value "3.3K")
      (footprint "eagle-import:0805")
      (libsource (lib "eagle-import") (part "R-0805"))
    )
    (comp (ref "R28")
      (value "3.3K")
      (footprint "eagle-import:0805")
      (libsource (lib "eagle-import") (part "R-0805"))
    )
    (comp (ref "R29")
      (value "1M")
      (footprint "eagle-import:0603")
      (libsource (lib "eagle-import") (part "R-0603"))
    )
    (comp (ref "R30")
      (value "1M")
      (footprint "eagle-import:0603")
      (libsource (lib "eagle-import") (part "R-0603"))
    )
    (comp (ref "R153")
      (value "CSR1206FK25L0")
      (footprint "eagle-import:R1206")
      (fields (field (name "MANUFACTURER") "Stackpole"))
      (libsource (lib "eagle-import") (part "R-US_R1206"))
    )
    (comp (ref "R154")
      (value "0.025R")
      (footprint "eagle-import:0805")
      (libsource (lib "eagle-import") (part "R-0805"))
    )
    (comp (ref "R155")
      (value "CSR1206FK25L0")
      (footprint "eagle-import:R1206")
      (fields (field (name "MANUFACTURER") "Stackpole"))
      (libsource (lib "eagle-import") (part "R-US_R1206"))
    )
    (comp (ref "R156")
      (value "1M")
      (footprint "eagle-import:R0603")
      (fields (field (name "MANUFACTURER") "Panasonic"))
      (libsource (lib "eagle-import") (part "R-US_R0603"))
    )
    (comp (ref "R157")
      (value "10")
      (footprint "eagle-import:R0603")
      (fields (field (name "MANUFACTURER") "Rohm"))
      (libsource (lib "eagle-import") (part "R-US_R0603"))
    )
    (comp (ref "R158")
      (value "10")
      (footprint "eagle-import:R0603")
      (fields (field (name "MANUFACTURER") "Rohm"))
      (libsource (lib "eagle-import") (part "R-US_R0603"))
    )
    (comp (ref "R159")
      (value "1M")
      (footprint "eagle-import:R0603")
      (fields (field (name "MANUFACTURER") "Panasonic"))
      (libsource (lib "eagle-import") (part "R-US_R0603"))
    )
    (comp (ref "R160")
      (value "178k,1%")
      (footprint "eagle-import:R0603")
      (fields (field (name "MANUFACTURER") "Panasonic"))
      (libsource (lib "eagle-import") (part "R-US_R0603"))
    )
    (comp (ref "R161")
      (value "0")
      (footprint "eagle-import:R0603")
      (fields (field (name "MANUFACTURER") "Panasonic"))
      (libsource (lib "eagle-import") (part "R-US_R0603"))
    )
    (comp (ref "R162")
      (value "10k")
      (footprint "eagle-import:R0603")
      (fields (field (name "MANUFACTURER") "Panasonic"))
      (libsource (lib "eagle-import") (part "R-US_R0603"))
    )
    (comp (ref "R163")
      (value "0")
      (footprint "eagle-import:R0603")
      (fields (field (name "MANUFACTURER") "Panasonic"))
      (libsource (lib "eagle-import") (part "R-US_R0603"))
    )
    (comp (ref "R164")
      (value "5.90k,1%")
      (footprint "eagle-import:R0603")
      (fields (field (name "MANUFACTURER") "Panasonic"))
      (libsource (lib "eagle-import") (part "R-US_R0603"))
    )
    (comp (ref "R165")
      (value "93.1k,1%")
      (footprint "eagle-import:R0603")
      (fields (field (name "MANUFACTURER") "Panasonic"))
      (libsource (lib "eagle-import") (part "R-US_R0603"))
    )
    (comp (ref "R166")
      (value "20.0k,1%")
      (footprint "eagle-import:R0603")
      (fields (field (name "MANUFACTURER") "Panasonic"))
      (libsource (lib "eagle-import") (part "R-US_R0603"))
    )
    (comp (ref "R167")
      (value "100k")
      (footprint "eagle-import:R0603")
      (fields (field (name "MANUFACTURER") "Panasonic"))
      (libsource (lib "eagle-import") (part "R-US_R0603"))
    )
    (comp (ref "R168")
      (value "0.025R")
      (footprint "eagle-import:0805")
      (libsource (lib "eagle-import") (part "R-0805"))
    )
    (comp (ref "R169")
      (value "CSR1206FK25L0")
      (footprint "eagle-import:R1206")
      (fields (field (name "MANUFACTURER") "Stackpole"))
      (libsource (lib "eagle-import") (part "R-US_R1206"))
    )
    (comp (ref "R170")
      (value "1M")
      (footprint "eagle-import:0603")
      (libsource (lib "eagle-import") (part "R-0603"))
    )
    (comp (ref "R171")
      (value "10")
      (footprint "eagle-import:R0603")
      (fields (field (name "MANUFACTURER") "Rohm"))
      (libsource (lib "eagle-import") (part "R-US_R0603"))
    )
    (comp (ref "R172")
      (value "10")
      (footprint "eagle-import:R0603")
      (fields (field (name "MANUFACTURER") "Rohm"))
      (libsource (lib "eagle-import") (part "R-US_R0603"))
    )
    (comp (ref "R173")
      (value "1M")
      (footprint "eagle-import:0603")
      (libsource (lib "eagle-import") (part "R-0603"))
    )
    (comp (ref "R174")
      (value "1M")
      (footprint "eagle-import:0603")
      (libsource (lib "eagle-import") (part "R-0603"))
    )
    (comp (ref "R175")
      (value "3.3K")
      (footprint "eagle-import:0805")
      (libsource (lib "eagle-import") (part "R-0805"))
    )
    (comp (ref "R176")
      (value "3.3K")
      (footprint "eagle-import:0805")
      (libsource (lib "eagle-import") (part "R-0805"))
    )
    (comp (ref "R177")
      (value "178k,1%")
      (footprint "eagle-import:R0603")
      (fields (field (name "MANUFACTURER") "Panasonic"))
      (libsource (lib "eagle-import") (part "R-US_R0603"))
    )
    (comp (ref "R178")
      (value "0")
      (footprint "eagle-import:R0603")
      (fields (field (name "MANUFACTURER") "Panasonic"))
      (libsource (lib "eagle-import") (part "R-US_R0603"))
    )
    (comp (ref "R179")
      (value "10k")
      (footprint "eagle-import:R0603")
      (fields (field (name "MANUFACTURER") "Panasonic"))
      (libsource (lib "eagle-import") (part "R-US_R0603"))
    )
    (comp (ref "R180")
      (value "0")
      (footprint "eagle-import:R0603")
      (fields (field (name "MANUFACTURER") "Panasonic"))
      (libsource (lib "eagle-import") (part "R-US_R0603"))
    )
    (comp (ref "R181")
      (value "5.90k,1%")
      (footprint "eagle-import:R0603")
      (fields (field (name "MANUFACTURER") "Panasonic"))
      (libsource (lib "eagle-import") (part "R-US_R0603"))
    )
    (comp (ref "R182")
      (value "93.1k,1%")
      (footprint "eagle-import:R0603")
      (fields (field (name "MANUFACTURER") "Panasonic"))
      (libsource (lib "eagle-import") (part "R-US_R0603"))
    )
    (comp (ref "R183")
      (value "1M")
      (footprint "eagle-import:0603")
      (libsource (lib "eagle-import") (part "R-0603"))
    )
    (comp (ref "R184")
      (value "1M")
      (footprint "eagle-import:0603")
      (libsource (lib "eagle-import") (part "R-0603"))
    )
    (comp (ref "R185")
      (value "20.0k,1%")
      (footprint "eagle-import:R0603")
      (fields (field (name "MANUFACTURER") "Panasonic"))
      (libsource (lib "eagle-import") (part "R-US_R0603"))
    )
    (comp (ref "R186")
      (value "100k")
      (footprint "eagle-import:R0603")
      (fields (field (name "MANUFACTURER") "Panasonic"))
      (libsource (lib "eagle-import") (part "R-US_R0603"))
    )
    (comp (ref "R187")
      (value "47K")
      (footprint "eagle-import:0603")
      (libsource (lib "eagle-import") (part "R-0603"))
    )
    (comp (ref "R188")
      (value "0.12R")
      (footprint "eagle-import:0805")
      (libsource (lib "eagle-import") (part "R-0805"))
    )
    (comp (ref "R189")
      (value "0.047R")
      (footprint "eagle-import:0805")
      (libsource (lib "eagle-import") (part "R-0805"))
    )
    (comp (ref "R190")
      (value "47K")
      (footprint "eagle-import:0603")
      (libsource (lib "eagle-import") (part "R-0603"))
    )
    (comp (ref "R191")
      (value "10K")
      (footprint "eagle-import:0603")
      (libsource (lib "eagle-import") (part "R-0603"))
    )
    (comp (ref "R192")
      (value "1.65M")
      (footprint "eagle-import:0603")
      (libsource (lib "eagle-import") (part "R-0603"))
    )
    (comp (ref "R193")
      (value "10K")
      (footprint "eagle-import:0603")
      (libsource (lib "eagle-import") (part "R-0603"))
    )
    (comp (ref "R194")
      (value "3.09M")
      (footprint "eagle-import:0603")
      (libsource (lib "eagle-import") (part "R-0603"))
    )
    (comp (ref "R195")
      (value "1M")
      (footprint "eagle-import:0603")
      (libsource (lib "eagle-import") (part "R-0603"))
    )
    (comp (ref "R196")
      (value "1M")
      (footprint "eagle-import:0603")
      (libsource (lib "eagle-import") (part "R-0603"))
    )
    (comp (ref "R197")
      (value "1M")
      (footprint "eagle-import:0603")
      (libsource (lib "eagle-import") (part "R-0603"))
    )
    (comp (ref "TP61")
      (value "TP0.8")
      (footprint "eagle-import:TP_0.8")
      (libsource (lib "eagle-import") (part "TP0.8"))
    )
    (comp (ref "TP62")
      (value "TP0.8")
      (footprint "eagle-import:TP_0.8")
      (libsource (lib "eagle-import") (part "TP0.8"))
    )
    (comp (ref "TP63")
      (value "TP0.8")
      (footprint "eagle-import:TP_0.8")
      (libsource (lib "eagle-import") (part "TP0.8"))
    )
    (comp (ref "TP64")
      (value "TP0.8")
      (footprint "eagle-import:TP_0.8")
      (libsource (lib "eagle-import") (part "TP0.8"))
    )
    (comp (ref "TP65")
      (value "TP0.8")
      (footprint "eagle-import:TP_0.8")
      (libsource (lib "eagle-import") (part "TP0.8"))
    )
    (comp (ref "TP66")
      (value "TP0.8")
      (footprint "eagle-import:TP_0.8")
      (libsource (lib "eagle-import") (part "TP0.8"))
    )
    (comp (ref "TP67")
      (value "TP0.8")
      (footprint "eagle-import:TP_0.8")
      (libsource (lib "eagle-import") (part "TP0.8"))
    )
    (comp (ref "TP68")
      (value "TP0.8")
      (footprint "eagle-import:TP_0.8")
      (libsource (lib "eagle-import") (part "TP0.8"))
    )
    (comp (ref "U6")
      (value "TPS43061")
      (footprint "eagle-import:QFN16_3X3_EP")
      (fields (field (name "MANUFACTURER") "TI"))
      (libsource (lib "eagle-import") (part "IC_TI_TPS43061RTE"))
    )
    (comp (ref "U7")
      (value "TPS43061")
      (footprint "eagle-import:QFN16_3X3_EP")
      (fields (field (name "MANUFACTURER") "TI"))
      (libsource (lib "eagle-import") (part "IC_TI_TPS43061RTE"))
    )
    (comp (ref "C165")
      (value "220uF,16V,AL")
      (footprint "eagle-import:CAP_6.3MM_DIA_SMT")
      (fields (field (name "MANUFACTURER") "Kemet") (field (name "MFR_PN") "EEV227M016A9HAA"))
      (libsource (lib "eagle-import") (part "CAP_ELEC_6.3MM_SMD"))
    )
    (comp (ref "C166")
      (value "220uF,16V,AL")
      (footprint "eagle-import:CAP_6.3MM_DIA_SMT")
      (fields (field (name "MANUFACTURER") "Kemet") (field (name "MFR_PN") "EEV227M016A9HAA"))
      (libsource (lib "eagle-import") (part "CAP_ELEC_6.3MM_SMD"))
    )
    (comp (ref "C167")
      (value "0.1uF")
      (footprint "eagle-import:C0603")
      (libsource (lib "eagle-import") (part "C-US-NP0603"))
    )
    (comp (ref "C168")
      (value "0.1uF")
      (footprint "eagle-import:C0603")
      (libsource (lib "eagle-import") (part "C-US-NP0603"))
    )
    (comp (ref "C169")
      (value "1.0nF,50V")
      (footprint "eagle-import:C0603")
      (fields (field (name "MANUFACTURER") "Samsung"))
      (libsource (lib "eagle-import") (part "C-US-NP0603"))
    )
    (comp (ref "C170")
      (value "1.0nF,50V")
      (footprint "eagle-import:C0603")
      (fields (field (name "MANUFACTURER") "Samsung"))
      (libsource (lib "eagle-import") (part "C-US-NP0603"))
    )
    (comp (ref "C171")
      (value "10uF,50V,1210")
      (footprint "eagle-import:C1210")
      (fields (field (name "MANUFACTURER") "Samsung"))
      (libsource (lib "eagle-import") (part "C-US-NP1210"))
    )
    (comp (ref "C172")
      (value "1uF,25V")
      (footprint "eagle-import:0603")
      (libsource (lib "eagle-import") (part "C-0603"))
    )
    (comp (ref "C173")
      (value "0.47uF")
      (footprint "eagle-import:C0603")
      (fields (field (name "MANUFACTURER") "Taiyo Yuden"))
      (libsource (lib "eagle-import") (part "C-US-NP0603"))
    )
    (comp (ref "C174")
      (value "0.47uF")
      (footprint "eagle-import:C0603")
      (fields (field (name "MANUFACTURER") "Samsung"))
      (libsource (lib "eagle-import") (part "C-US-NP0603"))
    )
    (comp (ref "C175")
      (value "0.47uF")
      (footprint "eagle-import:C0603")
      (fields (field (name "MANUFACTURER") "Samsung"))
      (libsource (lib "eagle-import") (part "C-US-NP0603"))
    )
    (comp (ref "C176")
      (value "1.0nF,50V")
      (footprint "eagle-import:C0603")
      (fields (field (name "MANUFACTURER") "Samsung"))
      (libsource (lib "eagle-import") (part "C-US-NP0603"))
    )
    (comp (ref "C177")
      (value "0.47uF")
      (footprint "eagle-import:C0603")
      (fields (field (name "MANUFACTURER") "Samsung"))
      (libsource (lib "eagle-import") (part "C-US-NP0603"))
    )
    (comp (ref "C178")
      (value "0.47uF")
      (footprint "eagle-import:C0603")
      (fields (field (name "MANUFACTURER") "Taiyo Yuden"))
      (libsource (lib "eagle-import") (part "C-US-NP0603"))
    )
    (comp (ref "C179")
      (value "1.0nF,50V")
      (footprint "eagle-import:C0603")
      (fields (field (name "MANUFACTURER") "Samsung"))
      (libsource (lib "eagle-import") (part "C-US-NP0603"))
    )
    (comp (ref "C180")
      (value "22uF,25V,1206")
      (footprint "eagle-import:C1206")
      (fields (field (name "MANUFACTURER") "Samsung"))
      (libsource (lib "eagle-import") (part "C-US-NP1206"))
    )
    (comp (ref "C181")
      (value "22uF,25V,1206")
      (footprint "eagle-import:C1206")
      (fields (field (name "MANUFACTURER") "Samsung"))
      (libsource (lib "eagle-import") (part "C-US-NP1206"))
    )
    (comp (ref "C182")
      (value "1uF,25V")
      (footprint "eagle-import:C0603")
      (libsource (lib "eagle-import") (part "C-US-NP0603"))
    )
    (comp (ref "C183")
      (value "3.3uF,16V")
      (footprint "eagle-import:C0603")
      (libsource (lib "eagle-import") (part "C-US-NP0603"))
    )
    (comp (ref "C184")
      (value "3.3uF,16V")
      (footprint "eagle-import:C0603")
      (libsource (lib "eagle-import") (part "C-US-NP0603"))
    )
    (comp (ref "C185")
      (value "3.3uF,16V")
      (footprint "eagle-import:C0603")
      (libsource (lib "eagle-import") (part "C-US-NP0603"))
    )
    (comp (ref "C186")
      (value "220pF")
      (footprint "eagle-import:C0603")
      (libsource (lib "eagle-import") (part "C-US-NP0603"))
    )
    (comp (ref "J46")
      (value "3-641215-5")
      (footprint "eagle-import:3-641215-5")
      (libsource (lib "eagle-import") (part "3-641215-5"))
    )
    (comp (ref "J47")
      (value "DF11-10DP-2DSA(01)")
      (footprint "eagle-import:DF11-10DP-2DSA")
      (libsource (lib "eagle-import") (part "DF11-10DP-2DSA(01)"))
    )
    (comp (ref "J48")
      (value "3-641215-2")
      (footprint "eagle-import:3-641215-2")
      (libsource (lib "eagle-import") (part "3-641215-2"))
    )
    (comp (ref "J49")
      (value "3-641215-2")
      (footprint "eagle-import:3-641215-2")
      (libsource (lib "eagle-import") (part "3-641215-2"))
    )
    (comp (ref "L15")
      (value "HI1812V101R-10")
      (footprint "eagle-import:L1812")
      (fields (field (name "MANUFACTURER") "Laird") (field (name "MFR_PN") "HI1812V101R-10"))
      (libsource (lib "eagle-import") (part "L1812"))
    )
    (comp (ref "L16")
      (value "HI1812V101R-10")
      (footprint "eagle-import:L1812")
      (fields (field (name "MANUFACTURER") "Laird") (field (name "MFR_PN") "HI1812V101R-10"))
      (libsource (lib "eagle-import") (part "L1812"))
    )
    (comp (ref "L17")
      (value "HI1206T500R-00")
      (footprint "eagle-import:1206")
      (libsource (lib "eagle-import") (part "L-1206"))
    )
    (comp (ref "Q24")
      (value "BSS138")
      (footprint "eagle-import:SOT23")
      (libsource (lib "eagle-import") (part "BSS138"))
    )
    (comp (ref "R198")
      (value "10")
      (footprint "eagle-import:R0603")
      (fields (field (name "MANUFACTURER") "Rohm"))
      (libsource (lib "eagle-import") (part "R-US_R0603"))
    )
    (comp (ref "R199")
      (value "0R")
      (footprint "eagle-import:R0603")
      (fields (field (name "MANUFACTURER") "Rohm"))
      (libsource (lib "eagle-import") (part "R-US_R0603"))
    )
    (comp (ref "R200")
      (value "1M")
      (footprint "eagle-import:R0603")
      (libsource (lib "eagle-import") (part "R-US_R0603"))
    )
    (comp (ref "R201")
      (value "1M")
      (footprint "eagle-import:R0603")
      (libsource (lib "eagle-import") (part "R-US_R0603"))
    )
    (comp (ref "R202")
      (value "DNP")
      (footprint "eagle-import:R0603")
      (libsource (lib "eagle-import") (part "R-US_R0603"))
    )
    (comp (ref "R203")
      (value "DNP")
      (footprint "eagle-import:R0603")
      (libsource (lib "eagle-import") (part "R-US_R0603"))
    )
    (comp (ref "R204")
      (value "1k")
      (footprint "eagle-import:R0603")
      (libsource (lib "eagle-import") (part "R-US_R0603"))
    )
    (comp (ref "R205")
      (value "100k")
      (footprint "eagle-import:R0603")
      (libsource (lib "eagle-import") (part "R-US_R0603"))
    )
    (comp (ref "R206")
      (value "33")
      (footprint "eagle-import:R0603")
      (libsource (lib "eagle-import") (part "R-US_R0603"))
    )
    (comp (ref "R207")
      (value "3.3k")
      (footprint "eagle-import:R0603")
      (libsource (lib "eagle-import") (part "R-US_R0603"))
    )
    (comp (ref "R208")
      (value "6.8k")
      (footprint "eagle-import:R0603")
      (libsource (lib "eagle-import") (part "R-US_R0603"))
    )
    (comp (ref "R209")
      (value "120k")
      (footprint "eagle-import:R0603")
      (libsource (lib "eagle-import") (part "R-US_R0603"))
    )
    (comp (ref "R210")
      (value "1M")
      (footprint "eagle-import:R0603")
      (libsource (lib "eagle-import") (part "R-US_R0603"))
    )
    (comp (ref "R211")
      (value "3.9k")
      (footprint "eagle-import:R0603")
      (libsource (lib "eagle-import") (part "R-US_R0603"))
    )
    (comp (ref "TP69")
      (value "P1-13")
      (footprint "eagle-import:P1-13")
      (libsource (lib "eagle-import") (part "P1-13"))
    )
    (comp (ref "U8")
      (value "TPA3111D1PWP")
      (footprint "eagle-import:TSSOP28_EP")
      (fields (field (name "MANUFACTURER") "TI"))
      (libsource (lib "eagle-import") (part "IC_TI_TPA3111D1PWP"))
    )
    (comp (ref "U9")
      (value "OPA322SAIDBVT")
      (footprint "eagle-import:SOT23-6")
      (fields (field (name "MANUFACTURER") "TI"))
      (libsource (lib "eagle-import") (part "IC_TI_OPA322SDBVAI"))
    )
    (comp (ref "B1")
      (value "3001/3.3V")
      (footprint "eagle-import:3001")
      (libsource (lib "eagle-import") (part "3001"))
    )
    (comp (ref "C1")
      (value "1u/10V")
      (footprint "eagle-import:0603")
      (libsource (lib "eagle-import") (part "C-0603"))
    )
    (comp (ref "C2")
      (value "0.1uF")
      (footprint "eagle-import:0603")
      (libsource (lib "eagle-import") (part "C-0603"))
    )
    (comp (ref "C3")
      (value "1u/10V")
      (footprint "eagle-import:0603")
      (libsource (lib "eagle-import") (part "C-0603"))
    )
    (comp (ref "C4")
      (value "100nF")
      (footprint "eagle-import:0603")
      (libsource (lib "eagle-import") (part "C-0603"))
    )
    (comp (ref "C5")
      (value "0.1uF")
      (footprint "eagle-import:0603")
      (libsource (lib "eagle-import") (part "C-0603"))
    )
    (comp (ref "C6")
      (value "0.1uF")
      (footprint "eagle-import:0603")
      (libsource (lib "eagle-import") (part "C-0603"))
    )
    (comp (ref "C7")
      (value "1u/10V")
      (footprint "eagle-import:0603")
      (libsource (lib "eagle-import") (part "C-0603"))
    )
    (comp (ref "C8")
      (value "1u/10V")
      (footprint "eagle-import:0603")
      (libsource (lib "eagle-import") (part "C-0603"))
    )
    (comp (ref "C9")
      (value "0.1uF")
      (footprint "eagle-import:0603")
      (libsource (lib "eagle-import") (part "C-0603"))
    )
    (comp (ref "C10")
      (value "10uF/4V")
      (footprint "eagle-import:0603")
      (libsource (lib "eagle-import") (part "C-0603"))
    )
    (comp (ref "C11")
      (value "4.7uF/16V")
      (footprint "eagle-import:0805")
      (libsource (lib "eagle-import") (part "C-0805"))
    )
    (comp (ref "C12")
      (value "10nF")
      (footprint "eagle-import:0603")
      (libsource (lib "eagle-import") (part "C-0603"))
    )
    (comp (ref "C13")
      (value "10nF")
      (footprint "eagle-import:0603")
      (libsource (lib "eagle-import") (part "C-0603"))
    )
    (comp (ref "C14")
      (value "1u/6.3V")
      (footprint "eagle-import:0603")
      (libsource (lib "eagle-import") (part "C-0603"))
    )
    (comp (ref "C15")
      (value "1u/10V")
      (footprint "eagle-import:0603")
      (libsource (lib "eagle-import") (part "C-0603"))
    )
    (comp (ref "C16")
      (value "4.7uF/6.3V")
      (footprint "eagle-import:0603")
      (libsource (lib "eagle-import") (part "C-0603"))
    )
    (comp (ref "C17")
      (value "0.1uF")
      (footprint "eagle-import:0603")
      (libsource (lib "eagle-import") (part "C-0603"))
    )
    (comp (ref "C18")
      (value "18pF")
      (footprint "eagle-import:0603")
      (libsource (lib "eagle-import") (part "C-0603"))
    )
    (comp (ref "C19")
      (value "18pF")
      (footprint "eagle-import:0603")
      (libsource (lib "eagle-import") (part "C-0603"))
    )
    (comp (ref "C20")
      (value "4.7uF/6.3V")
      (footprint "eagle-import:0603")
      (libsource (lib "eagle-import") (part "C-0603"))
    )
    (comp (ref "C21")
      (value "0.1uF")
      (footprint "eagle-import:0603")
      (libsource (lib "eagle-import") (part "C-0603"))
    )
    (comp (ref "C22")
      (value "0.1uF")
      (footprint "eagle-import:0603")
      (libsource (lib "eagle-import") (part "C-0603"))
    )
    (comp (ref "C23")
      (value "10uF/10V")
      (footprint "eagle-import:0603")
      (libsource (lib "eagle-import") (part "C-0603"))
    )
    (comp (ref "C24")
      (value "1u/10V")
      (footprint "eagle-import:0603")
      (libsource (lib "eagle-import") (part "C-0603"))
    )
    (comp (ref "C25")
      (value "10nF")
      (footprint "eagle-import:0603")
      (libsource (lib "eagle-import") (part "C-0603"))
    )
    (comp (ref "C26")
      (value "10nF")
      (footprint "eagle-import:0603")
      (libsource (lib "eagle-import") (part "C-0603"))
    )
    (comp (ref "C27")
      (value "22u/16V")
      (footprint "eagle-import:1210")
      (libsource (lib "eagle-import") (part "C-1210"))
    )
    (comp (ref "C28")
      (value "1uF/16V")
      (footprint "eagle-import:0603")
      (libsource (lib "eagle-import") (part "C-0603"))
    )
    (comp (ref "C29")
      (value "10uF/10V")
      (footprint "eagle-import:0603")
      (libsource (lib "eagle-import") (part "C-0603"))
    )
    (comp (ref "C30")
      (value "0.1uF")
      (footprint "eagle-import:0603")
      (libsource (lib "eagle-import") (part "C-0603"))
    )
    (comp (ref "C31")
      (value "1uF/16V")
      (footprint "eagle-import:0603")
      (libsource (lib "eagle-import") (part "C-0603"))
    )
    (comp (ref "C32")
      (value "1uF/16V")
      (footprint "eagle-import:0603")
      (libsource (lib "eagle-import") (part "C-0603"))
    )
    (comp (ref "C33")
      (value "0.1uF")
      (footprint "eagle-import:0603")
      (libsource (lib "eagle-import") (part "C-0603"))
    )
    (comp (ref "C34")
      (value "dnp")
      (footprint "eagle-import:0603")
      (libsource (lib "eagle-import") (part "C-0603"))
    )
    (comp (ref "C35")
      (value "0.1uF")
      (footprint "eagle-import:0603")
      (libsource (lib "eagle-import") (part "C-0603"))
    )
    (comp (ref "D1")
      (value "BAS70-05E6327")
      (footprint "eagle-import:SOT-23")
      (libsource (lib "eagle-import") (part "BAS70-05E6327"))
    )
    (comp (ref "D2")
      (value "DNP")
      (footprint "eagle-import:SOD-123")
      (libsource (lib "eagle-import") (part "STPS0540Z"))
    )
    (comp (ref "D3")
      (value "STPS0540Z")
      (footprint "eagle-import:SOD-123")
      (libsource (lib "eagle-import") (part "STPS0540Z"))
    )
    (comp (ref "D4")
      (value "PMEG3030BEP")
      (footprint "eagle-import:SOD-128")
      (libsource (lib "eagle-import") (part "PMEG3030BEP"))
    )
    (comp (ref "FID1")
      (value "REF")
      (footprint "eagle-import:REF")
      (libsource (lib "eagle-import") (part "REF"))
    )
    (comp (ref "FID2")
      (value "REF")
      (footprint "eagle-import:REF")
      (libsource (lib "eagle-import") (part "REF"))
    )
    (comp (ref "FID3")
      (value "REF")
      (footprint "eagle-import:REF")
      (libsource (lib "eagle-import") (part "REF"))
    )
    (comp (ref "H2")
      (value "STANDOFF_ELECTRICAL")
      (footprint "eagle-import:STANDOFF-ELECTRICAL")
      (libsource (lib "eagle-import") (part "STANDOFF_ELECTRICAL"))
    )
    (comp (ref "H3")
      (value "STANDOFF_ELECTRICAL")
      (footprint "eagle-import:STANDOFF-ELECTRICAL")
      (libsource (lib "eagle-import") (part "STANDOFF_ELECTRICAL"))
    )
    (comp (ref "H4")
      (value "STANDOFF_ELECTRICAL")
      (footprint "eagle-import:STANDOFF-ELECTRICAL")
      (libsource (lib "eagle-import") (part "STANDOFF_ELECTRICAL"))
    )
    (comp (ref "H5")
      (value "STANDOFF_ELECTRICAL")
      (footprint "eagle-import:STANDOFF-ELECTRICAL")
      (libsource (lib "eagle-import") (part "STANDOFF_ELECTRICAL"))
    )
    (comp (ref "H6")
      (value "STANDOFF_ELECTRICAL")
      (footprint "eagle-import:STANDOFF-ELECTRICAL")
      (libsource (lib "eagle-import") (part "STANDOFF_ELECTRICAL"))
    )
    (comp (ref "IC1")
      (value "ISL60002DIH325Z-TK")
      (footprint "eagle-import:SOT-23")
      (libsource (lib "eagle-import") (part "ISL60002DIH325Z-TK"))
    )
    (comp (ref "IC2")
      (value "SN65HVD12D")
      (footprint "eagle-import:SO08")
      (libsource (lib "eagle-import") (part "SN65HVD3082ED"))
    )
    (comp (ref "IC3")
      (value "PIC24FJ256GA110-I/PT")
      (footprint "eagle-import:SQFP-S-12X12-100")
      (libsource (lib "eagle-import") (part "PIC24FJ256GA110-I/PT"))
    )
    (comp (ref "IC4")
      (value "PIC10F200T-I/OT")
      (footprint "eagle-import:SOT23-6")
      (libsource (lib "eagle-import") (part "PIC10F200T-I/OT"))
    )
    (comp (ref "IC5")
      (value "LM75ADP")
      (footprint "eagle-import:TSSOP08-3")
      (libsource (lib "eagle-import") (part "LM75ADP"))
    )
    (comp (ref "IC6")
      (value "24LC32A-I/MS")
      (footprint "eagle-import:MSOP-08")
      (libsource (lib "eagle-import") (part "24-I/MS"))
    )
    (comp (ref "IC7")
      (value "PCF2123TS/1-T")
      (footprint "eagle-import:TSSOP014")
      (libsource (lib "eagle-import") (part "PCF2123TS/1-T"))
    )
    (comp (ref "IC8")
      (value "M25P16-VMN6P")
      (footprint "eagle-import:SO-08")
      (libsource (lib "eagle-import") (part "M25P16-VMN6P"))
    )
    (comp (ref "IC9")
      (value "LM3405AXMK/NOPB")
      (footprint "eagle-import:SOT23-6")
      (libsource (lib "eagle-import") (part "LM3405AXMK/NOPB"))
    )
    (comp (ref "J1")
      (value "DF11-10DP-2DSA(01)")
      (footprint "eagle-import:DF11-10DP-2DSA")
      (libsource (lib "eagle-import") (part "DF11-10DP-2DSA(01)"))
    )
    (comp (ref "J2")
      (value "MA07-1")
      (footprint "eagle-import:MA07-1")
      (libsource (lib "eagle-import") (part "MA07-1"))
    )
    (comp (ref "J3")
      (value "MA13-2")
      (footprint "eagle-import:MA13-2")
      (libsource (lib "eagle-import") (part "MA13-2"))
    )
    (comp (ref "J4")
      (value "53047-05")
      (footprint "eagle-import:53047-05")
      (libsource (lib "eagle-import") (part "53?-05047"))
    )
    (comp (ref "J5")
      (value "3-641215-2")
      (footprint "eagle-import:3-641215-2")
      (libsource (lib "eagle-import") (part "3-641215-2"))
    )
    (comp (ref "J6")
      (value "3-641215-2")
      (footprint "eagle-import:3-641215-2")
      (libsource (lib "eagle-import") (part "3-641215-2"))
    )
    (comp (ref "J7")
      (value "SS-6566-NF")
      (footprint "eagle-import:SS-6566-NF")
      (libsource (lib "eagle-import") (part "SS-6566-NF"))
    )
    (comp (ref "J8")
      (value "TSW-108-07-G-D")
      (footprint "eagle-import:MA08-2")
      (libsource (lib "eagle-import") (part "MA08-2"))
    )
    (comp (ref "J9")
      (value "SS-6566-NF")
      (footprint "eagle-import:SS-6566-NF")
      (libsource (lib "eagle-import") (part "SS-6566-NF"))
    )
    (comp (ref "J10")
      (value "CCM03-3504LFT-NR")
      (footprint "eagle-import:CCM03-3504LFT-NR")
      (libsource (lib "eagle-import") (part "CCM03-3504LFT-NR"))
    )
    (comp (ref "J11")
      (value "MA05-1")
      (footprint "eagle-import:MA05-1")
      (libsource (lib "eagle-import") (part "MA05-1"))
    )
    (comp (ref "J12")
      (value "MA05-1")
      (footprint "eagle-import:MA05-1")
      (libsource (lib "eagle-import") (part "MA05-1"))
    )
    (comp (ref "J13")
      (value "3-641215-3")
      (footprint "eagle-import:3-641215-3")
      (libsource (lib "eagle-import") (part "3-641215-3"))
    )
    (comp (ref "J14")
      (value "3-641215-2")
      (footprint "eagle-import:3-641215-2")
      (libsource (lib "eagle-import") (part "3-641215-2"))
    )
    (comp (ref "L1")
      (value "HI1206T500R-00")
      (footprint "eagle-import:1206")
      (libsource (lib "eagle-import") (part "L-1206"))
    )
    (comp (ref "L2")
      (value "HI1206T500R-00")
      (footprint "eagle-import:1206")
      (libsource (lib "eagle-import") (part "L-1206"))
    )
    (comp (ref "L3")
      (value "NRS8030T150MJGJ")
      (footprint "eagle-import:NRS8030")
      (libsource (lib "eagle-import") (part "NRS8030T150MJGJ"))
    )
    (comp (ref "Q1")
      (value "SSM6P49NU,LFPZ")
      (footprint "eagle-import:MICRO_FET")
      (libsource (lib "eagle-import") (part "SSM6P49PZNU,LF"))
    )
    (comp (ref "Q2")
      (value "FDC6330L")
      (footprint "eagle-import:SSOT-6")
      (libsource (lib "eagle-import") (part "FDC6330L"))
    )
    (comp (ref "Q3")
      (value "SR3.3.TCT")
      (footprint "eagle-import:SOT-143")
      (libsource (lib "eagle-import") (part "SR05.TCT"))
    )
    (comp (ref "Q4")
      (value "7B-28.63636MAAJ-T")
      (footprint "eagle-import:7B")
      (libsource (lib "eagle-import") (part "7B-27.120MAAJ-T"))
    )
    (comp (ref "Q5")
      (value "FDC6324L")
      (footprint "eagle-import:SSOT-6")
      (libsource (lib "eagle-import") (part "FDC6324L"))
    )
    (comp (ref "Q6")
      (value "CM519 32.768KDZF-UT")
      (footprint "eagle-import:CM519")
      (libsource (lib "eagle-import") (part "CM519"))
    )
    (comp (ref "Q7")
      (value "SSM6P49NU,LFPZ")
      (footprint "eagle-import:MICRO_FET")
      (libsource (lib "eagle-import") (part "SSM6P49PZNU,LF"))
    )
    (comp (ref "R1")
      (value "47R")
      (footprint "eagle-import:0603")
      (libsource (lib "eagle-import") (part "R-0603"))
    )
    (comp (ref "R2")
      (value "100K")
      (footprint "eagle-import:0603-ARRAY")
      (libsource (lib "eagle-import") (part "EXB-38"))
    )
    (comp (ref "R3")
      (value "1M")
      (footprint "eagle-import:0603")
      (libsource (lib "eagle-import") (part "R-0603"))
    )
    (comp (ref "R4")
      (value "1M")
      (footprint "eagle-import:0603")
      (libsource (lib "eagle-import") (part "R-0603"))
    )
    (comp (ref "R5")
      (value "1M")
      (footprint "eagle-import:0603")
      (libsource (lib "eagle-import") (part "R-0603"))
    )
    (comp (ref "R6")
      (value "1M")
      (footprint "eagle-import:0603")
      (libsource (lib "eagle-import") (part "R-0603"))
    )
    (comp (ref "R7")
      (value "100K")
      (footprint "eagle-import:0603")
      (libsource (lib "eagle-import") (part "R-0603"))
    )
    (comp (ref "R8")
      (value "3.57K")
      (footprint "eagle-import:0603")
      (libsource (lib "eagle-import") (part "R-0603"))
    )
    (comp (ref "R9")
      (value "1M")
      (footprint "eagle-import:0603")
      (libsource (lib "eagle-import") (part "R-0603"))
    )
    (comp (ref "R10")
      (value "1M")
      (footprint "eagle-import:0603")
      (libsource (lib "eagle-import") (part "R-0603"))
    )
    (comp (ref "R11")
      (value "1M")
      (footprint "eagle-import:0603")
      (libsource (lib "eagle-import") (part "R-0603"))
    )
    (comp (ref "R12")
      (value "470K")
      (footprint "eagle-import:0603-0RTOP")
      (libsource (lib "eagle-import") (part "R-0603-0RTOP"))
    )
    (comp (ref "R13")
      (value "0R")
      (footprint "eagle-import:0603-0RTOP")
      (libsource (lib "eagle-import") (part "R-0603-0RTOP"))
    )
    (comp (ref "R14")
      (value "33K")
      (footprint "eagle-import:0603")
      (libsource (lib "eagle-import") (part "R-0603"))
    )
    (comp (ref "R15")
      (value "0R")
      (footprint "eagle-import:0603-0RTOP")
      (libsource (lib "eagle-import") (part "R-0603-0RTOP"))
    )
    (comp (ref "R16")
      (value "10K")
      (footprint "eagle-import:0603-0RTOP")
      (libsource (lib "eagle-import") (part "R-0603-0RTOP"))
    )
    (comp (ref "R17")
      (value "10K")
      (footprint "eagle-import:0603-0RTOP")
      (libsource (lib "eagle-import") (part "R-0603-0RTOP"))
    )
    (comp (ref "R18")
      (value "649R")
      (footprint "eagle-import:0603")
      (libsource (lib "eagle-import") (part "R-0603"))
    )
    (comp (ref "R19")
      (value "649R")
      (footprint "eagle-import:0603")
      (libsource (lib "eagle-import") (part "R-0603"))
    )
    (comp (ref "R20")
      (value "100K")
      (footprint "eagle-import:0603-ARRAY")
      (libsource (lib "eagle-import") (part "EXB-38"))
    )
    (comp (ref "R21")
      (value "100K")
      (footprint "eagle-import:0603-ARRAY")
      (libsource (lib "eagle-import") (part "EXB-38"))
    )
    (comp (ref "R22")
      (value "1M")
      (footprint "eagle-import:0603")
      (libsource (lib "eagle-import") (part "R-0603"))
    )
    (comp (ref "R23")
      (value "10K")
      (footprint "eagle-import:0603-0RTOP")
      (libsource (lib "eagle-import") (part "R-0603-0RTOP"))
    )
    (comp (ref "R24")
      (value "1M")
      (footprint "eagle-import:0603")
      (libsource (lib "eagle-import") (part "R-0603"))
    )
    (comp (ref "R25")
      (value "0.22R")
      (footprint "eagle-import:0603-0RTOP")
      (libsource (lib "eagle-import") (part "R-0603-0RTOP"))
    )
    (comp (ref "R26")
      (value "10K")
      (footprint "eagle-import:0603-0RTOP")
      (libsource (lib "eagle-import") (part "R-0603-0RTOP"))
    )
    (comp (ref "TP1")
      (value "ROUND_SMD1MM")
      (footprint "eagle-import:SMD_ROUND_1MM")
      (libsource (lib "eagle-import") (part "ROUND_SMD1MM"))
    )
    (comp (ref "TP2")
      (value "ROUND_SMD1MM")
      (footprint "eagle-import:SMD_ROUND_1MM")
      (libsource (lib "eagle-import") (part "ROUND_SMD1MM"))
    )
    (comp (ref "TP3")
      (value "ROUND_SMD1MM")
      (footprint "eagle-import:SMD_ROUND_1MM")
      (libsource (lib "eagle-import") (part "ROUND_SMD1MM"))
    )
    (comp (ref "TP4")
      (value "ROUND_SMD1MM")
      (footprint "eagle-import:SMD_ROUND_1MM")
      (libsource (lib "eagle-import") (part "ROUND_SMD1MM"))
    )
    (comp (ref "TP5")
      (value "ROUND_SMD1MM")
      (footprint "eagle-import:SMD_ROUND_1MM")
      (libsource (lib "eagle-import") (part "ROUND_SMD1MM"))
    )
    (comp (ref "TP7")
      (value "ROUND_SMD1MM")
      (footprint "eagle-import:SMD_ROUND_1MM")
      (libsource (lib "eagle-import") (part "ROUND_SMD1MM"))
    )
    (comp (ref "TP8")
      (value "ROUND_SMD1MM")
      (footprint "eagle-import:SMD_ROUND_1MM")
      (libsource (lib "eagle-import") (part "ROUND_SMD1MM"))
    )
    (comp (ref "TP9")
      (value "ROUND_SMD0.7MM")
      (footprint "eagle-import:SMD_ROUND_07MM")
      (libsource (lib "eagle-import") (part "ROUND_SMD0.7MM"))
    )
    (comp (ref "TP11")
      (value "ROUND_SMD0.7MM")
      (footprint "eagle-import:SMD_ROUND_07MM")
      (libsource (lib "eagle-import") (part "ROUND_SMD0.7MM"))
    )
    (comp (ref "TP12")
      (value "TP_0812")
      (footprint "eagle-import:TP_0.8_1.2")
      (libsource (lib "eagle-import") (part "TP_0812"))
    )
    (comp (ref "U1")
      (value "LTC1955")
      (footprint "eagle-import:LFCSP_5X5_032")
      (libsource (lib "eagle-import") (part "LTC1955"))
    )
    (comp (ref "U2")
      (value "HRXL-MAXSONAR-WRC-MB7387")
      (footprint "eagle-import:HRXL-MAXSONAR-WRC-MB7387")
      (libsource (lib "eagle-import") (part "HRXL-MAXSONAR-WRC-MB7387"))
    )
    (comp (ref "X1")
      (value "FH12-10S-0.5S1.00MM")
      (footprint "eagle-import:CON-FPC-1.0MM-10POS")
      (libsource (lib "eagle-import") (part "FH12-10S-0.5S1.00MM"))
    )
  )
  (nets
    (net (code "1") (name "+3.3V") (class "Default")
      (node (ref "C1") (pin "1") (pinfunction "1_1") (pintype "passive"))
      (node (ref "C157") (pin "1") (pinfunction "1_1") (pintype "passive"))
      (node (ref "C159") (pin "2") (pinfunction "2_2") (pintype "passive"))
      (node (ref "C16") (pin "2") (pinfunction "2_2") (pintype "passive"))
      (node (ref "C17") (pin "1") (pinfunction "1_1") (pintype "passive"))
      (node (ref "C2") (pin "1") (pinfunction "1_1") (pintype "passive"))
      (node (ref "C23") (pin "2") (pinfunction "2_2") (pintype "passive"))
      (node (ref "C29") (pin "2") (pinfunction "2_2") (pintype "passive"))
      (node (ref "C3") (pin "1") (pinfunction "1_1") (pintype "passive"))
      (node (ref "C5") (pin "1") (pinfunction "1_1") (pintype "passive"))
      (node (ref "C6") (pin "1") (pinfunction "1_1") (pintype "passive"))
      (node (ref "C8") (pin "1") (pinfunction "1_1") (pintype "passive"))
      (node (ref "C9") (pin "1") (pinfunction "1_1") (pintype "passive"))
      (node (ref "D1") (pin "2") (pinfunction "A2_2") (pintype "passive"))
      (node (ref "D27") (pin "+") (pinfunction "C_+") (pintype "passive"))
      (node (ref "D31") (pin "4") (pinfunction "K_4") (pintype "passive"))
      (node (ref "D31") (pin "5") (pinfunction "K_5") (pintype "passive"))
      (node (ref "IC1") (pin "1") (pinfunction "VIN_1") (pintype "power_in"))
      (node (ref "IC3") (pin "16") (pinfunction "VDD16_16") (pintype "power_in"))
      (node (ref "IC3") (pin "2") (pinfunction "VDD2_2") (pintype "power_in"))
      (node (ref "IC3") (pin "37") (pinfunction "VDD37_37") (pintype "power_in"))
      (node (ref "IC3") (pin "46") (pinfunction "VDD46_46") (pintype "power_in"))
      (node (ref "IC3") (pin "62") (pinfunction "VDD62_62") (pintype "power_in"))
      (node (ref "IC3") (pin "86") (pinfunction "VDD86_86") (pintype "power_in"))
      (node (ref "J1") (pin "9") (pinfunction "9_9") (pintype "passive"))
      (node (ref "J11") (pin "2") (pinfunction "2_2") (pintype "passive"))
      (node (ref "J3") (pin "25") (pinfunction "25_25") (pintype "passive"))
      (node (ref "J8") (pin "10") (pinfunction "10_10") (pintype "passive"))
      (node (ref "L13") (pin "2") (pinfunction "2_2") (pintype "passive"))
      (node (ref "Q1") (pin "1") (pinfunction "S_1") (pintype "passive"))
      (node (ref "Q1") (pin "4") (pinfunction "S_4") (pintype "passive"))
      (node (ref "Q7") (pin "1") (pinfunction "S_1") (pintype "passive"))
      (node (ref "Q7") (pin "4") (pinfunction "S_4") (pintype "passive"))
      (node (ref "R1") (pin "2") (pinfunction "2_2") (pintype "passive"))
      (node (ref "R12") (pin "2") (pinfunction "2_2") (pintype "passive"))
      (node (ref "R14") (pin "2") (pinfunction "2_2") (pintype "passive"))
      (node (ref "R15") (pin "2") (pinfunction "2_2") (pintype "passive"))
      (node (ref "R167") (pin "2") (pinfunction "2_2") (pintype "passive"))
      (node (ref "R186") (pin "2") (pinfunction "2_2") (pintype "passive"))
      (node (ref "R187") (pin "2") (pinfunction "2_2") (pintype "passive"))
      (node (ref "R190") (pin "2") (pinfunction "2_2") (pintype "passive"))
      (node (ref "R192") (pin "1") (pinfunction "1_1") (pintype "passive"))
      (node (ref "R2") (pin "7") (pinfunction "2_7") (pintype "passive"))
      (node (ref "R2") (pin "8") (pinfunction "2_8") (pintype "passive"))
      (node (ref "TP64") (pin "1") (pinfunction "TP_1") (pintype "passive"))
      (node (ref "TP9") (pin "P$1") (pinfunction "TP_P$1") (pintype "passive"))
      (node (ref "U1") (pin "1") (pinfunction "DVCC_1") (pintype "bidirectional"))
      (node (ref "U1") (pin "12") (pinfunction "SVBAT_12") (pintype "bidirectional"))
      (node (ref "U1") (pin "13") (pinfunction "PVBAT_13") (pintype "bidirectional"))
    )
    (net (code "2") (name "+3.3V{slash}1") (class "Default")
      (node (ref "C22") (pin "1") (pinfunction "1_1") (pintype "passive"))
      (node (ref "C33") (pin "1") (pinfunction "1_1") (pintype "passive"))
      (node (ref "IC5") (pin "7") (pinfunction "A0_7") (pintype "input"))
      (node (ref "IC5") (pin "8") (pinfunction "VCC_8") (pintype "power_in"))
      (node (ref "IC6") (pin "8") (pinfunction "VCC_8") (pintype "power_in"))
      (node (ref "IC8") (pin "3") (pinfunction "/WP_3") (pintype "input"))
      (node (ref "IC8") (pin "7") (pinfunction "/HOLD_7") (pintype "input"))
      (node (ref "IC8") (pin "8") (pinfunction "VCC_8") (pintype "power_in"))
      (node (ref "J49") (pin "2") (pinfunction "2_2") (pintype "passive"))
      (node (ref "Q7") (pin "6") (pinfunction "D_6") (pintype "passive"))
      (node (ref "Q7") (pin "P1") (pinfunction "D1_P1") (pintype "passive"))
      (node (ref "R16") (pin "2") (pinfunction "2_2") (pintype "passive"))
      (node (ref "R17") (pin "2") (pinfunction "2_2") (pintype "passive"))
      (node (ref "R200") (pin "1") (pinfunction "1_1") (pintype "passive"))
      (node (ref "R201") (pin "1") (pinfunction "1_1") (pintype "passive"))
      (node (ref "R205") (pin "2") (pinfunction "2_2") (pintype "passive"))
      (node (ref "R206") (pin "2") (pinfunction "2_2") (pintype "passive"))
      (node (ref "R24") (pin "1") (pinfunction "1_1") (pintype "passive"))
      (node (ref "R31") (pin "2") (pinfunction "2_2") (pintype "passive"))
      (node (ref "R32") (pin "2") (pinfunction "2_2") (pintype "passive"))
      (node (ref "TP8") (pin "P$1") (pinfunction "TP_P$1") (pintype "passive"))
    )
    (net (code "3") (name "+3.3V{slash}2") (class "Default")
      (node (ref "C14") (pin "1") (pinfunction "1_1") (pintype "passive"))
      (node (ref "C35") (pin "2") (pinfunction "2_2") (pintype "passive"))
      (node (ref "IC2") (pin "8") (pinfunction "VCC_8") (pintype "power_in"))
      (node (ref "J2") (pin "2") (pinfunction "2_2") (pintype "passive"))
      (node (ref "J8") (pin "1") (pinfunction "1_1") (pintype "passive"))
      (node (ref "Q7") (pin "3") (pinfunction "D_3") (pintype "passive"))
      (node (ref "Q7") (pin "P2") (pinfunction "D1_P2") (pintype "passive"))
      (node (ref "R11") (pin "2") (pinfunction "2_2") (pintype "passive"))
      (node (ref "R26") (pin "2") (pinfunction "2_2") (pintype "passive"))
      (node (ref "U2") (pin "6") (pinfunction "VCC_6") (pintype "bidirectional"))
    )
    (net (code "4") (name "+3.3V{slash}7") (class "Default")
      (node (ref "Q1") (pin "3") (pinfunction "D_3") (pintype "passive"))
      (node (ref "Q1") (pin "P2") (pinfunction "D1_P2") (pintype "passive"))
    )
    (net (code "5") (name "+5V") (class "Default")
      (node (ref "C156") (pin "1") (pinfunction "PIN+_1") (pintype "passive"))
      (node (ref "C158") (pin "1") (pinfunction "1_1") (pintype "passive"))
      (node (ref "C160") (pin "2") (pinfunction "2_2") (pintype "passive"))
      (node (ref "C37") (pin "1") (pinfunction "1_1") (pintype "passive"))
      (node (ref "D28") (pin "+") (pinfunction "C_+") (pintype "passive"))
      (node (ref "L14") (pin "2") (pinfunction "2_2") (pintype "passive"))
      (node (ref "R194") (pin "1") (pinfunction "1_1") (pintype "passive"))
      (node (ref "TP65") (pin "1") (pinfunction "TP_1") (pintype "passive"))
      (node (ref "U3") (pin "8") (pinfunction "VDD_8") (pintype "bidirectional"))
    )
    (net (code "6") (name "+SMB") (class "Default")
      (node (ref "C11") (pin "1") (pinfunction "1_1") (pintype "passive"))
      (node (ref "C135") (pin "1") (pinfunction "1_1") (pintype "passive"))
      (node (ref "C149") (pin "1") (pinfunction "1_1") (pintype "passive"))
      (node (ref "C150") (pin "1") (pinfunction "1_1") (pintype "passive"))
      (node (ref "C151") (pin "1") (pinfunction "1_1") (pintype "passive"))
      (node (ref "C152") (pin "1") (pinfunction "1_1") (pintype "passive"))
      (node (ref "C153") (pin "1") (pinfunction "1_1") (pintype "passive"))
      (node (ref "C154") (pin "1") (pinfunction "1_1") (pintype "passive"))
      (node (ref "C155") (pin "1") (pinfunction "1_1") (pintype "passive"))
      (node (ref "C187") (pin "1") (pinfunction "PIN+_1") (pintype "passive"))
      (node (ref "C27") (pin "1") (pinfunction "1_1") (pintype "passive"))
      (node (ref "C28") (pin "1") (pinfunction "1_1") (pintype "passive"))
      (node (ref "D2") (pin "A") (pinfunction "A_A") (pintype "passive"))
      (node (ref "D32") (pin "C") (pinfunction "C_C") (pintype "passive"))
      (node (ref "F3") (pin "2") (pinfunction "2_2") (pintype "passive"))
      (node (ref "IC20") (pin "6") (pinfunction "VIN_6") (pintype "power_in"))
      (node (ref "IC20") (pin "8") (pinfunction "MODE_8") (pintype "input"))
      (node (ref "IC21") (pin "6") (pinfunction "VIN_6") (pintype "power_in"))
      (node (ref "IC21") (pin "8") (pinfunction "MODE_8") (pintype "input"))
      (node (ref "IC9") (pin "5") (pinfunction "VIN_5") (pintype "power_in"))
      (node (ref "J1") (pin "10") (pinfunction "10_10") (pintype "passive"))
      (node (ref "J3") (pin "13") (pinfunction "13_13") (pintype "passive"))
      (node (ref "J7") (pin "2") (pinfunction "2_2") (pintype "passive"))
      (node (ref "J8") (pin "7") (pinfunction "7_7") (pintype "passive"))
      (node (ref "J9") (pin "2") (pinfunction "2_2") (pintype "passive"))
      (node (ref "JP5") (pin "P2") (pinfunction "2_P2") (pintype "passive"))
      (node (ref "Q15") (pin "3") (pinfunction "S_3") (pintype "passive"))
      (node (ref "Q18") (pin "3") (pinfunction "S_3") (pintype "passive"))
      (node (ref "Q2") (pin "4") (pinfunction "Q2S_4") (pintype "bidirectional"))
      (node (ref "Q5") (pin "4") (pinfunction "Q2S_4") (pintype "bidirectional"))
      (node (ref "R156") (pin "2") (pinfunction "2_2") (pintype "passive"))
      (node (ref "R170") (pin "1") (pinfunction "1_1") (pintype "passive"))
      (node (ref "R188") (pin "2") (pinfunction "2_2") (pintype "passive"))
      (node (ref "R189") (pin "2") (pinfunction "2_2") (pintype "passive"))
      (node (ref "R20") (pin "6") (pinfunction "2_6") (pintype "passive"))
      (node (ref "R3") (pin "1") (pinfunction "1_1") (pintype "passive"))
      (node (ref "TP63") (pin "1") (pinfunction "TP_1") (pintype "passive"))
    )
    (net (code "7") (name "3V3_AUD") (class "Default")
      (node (ref "C180") (pin "1") (pinfunction "1_1") (pintype "passive"))
      (node (ref "C181") (pin "1") (pinfunction "1_1") (pintype "passive"))
      (node (ref "C182") (pin "1") (pinfunction "1_1") (pintype "passive"))
      (node (ref "R206") (pin "1") (pinfunction "1_1") (pintype "passive"))
      (node (ref "R207") (pin "1") (pinfunction "1_1") (pintype "passive"))
      (node (ref "U9") (pin "6") (pinfunction "V+_6") (pintype "power_in"))
    )
    (net (code "8") (name "5V_ON") (class "Default")
      (node (ref "C163") (pin "1") (pinfunction "1_1") (pintype "passive"))
      (node (ref "IC21") (pin "1") (pinfunction "RUN/SS_1") (pintype "input"))
      (node (ref "IC3") (pin "92") (pinfunction "RA7/CN40_92") (pintype "bidirectional"))
      (node (ref "R195") (pin "1") (pinfunction "1_1") (pintype "passive"))
    )
    (net (code "9") (name "18V_GND") (class "Default")
      (node (ref "CN1") (pin "GND") (pinfunction "GND_GND") (pintype "power_in"))
      (node (ref "JP2") (pin "P1") (pinfunction "1_P1") (pintype "passive"))
      (node (ref "R34") (pin "1") (pinfunction "1_1") (pintype "passive"))
      (node (ref "U3") (pin "5") (pinfunction "AIN1_5") (pintype "bidirectional"))
    )
    (net (code "10") (name "18V_SENSE") (class "Default")
      (node (ref "CN1") (pin "PWR") (pinfunction "PWR_PWR") (pintype "power_in"))
      (node (ref "JP2") (pin "P2") (pinfunction "2_P2") (pintype "passive"))
      (node (ref "R33") (pin "2") (pinfunction "2_2") (pintype "passive"))
    )
    (net (code "11") (name "A+") (class "Default")
      (node (ref "IC2") (pin "6") (pinfunction "A_6") (pintype "bidirectional"))
      (node (ref "L2") (pin "1") (pinfunction "1_1") (pintype "passive"))
      (node (ref "Q3") (pin "3") (pinfunction "3_3") (pintype "passive"))
      (node (ref "R11") (pin "1") (pinfunction "1_1") (pintype "passive"))
      (node (ref "R9") (pin "1") (pinfunction "1_1") (pintype "passive"))
    )
    (net (code "12") (name "A1") (class "Default")
      (node (ref "J7") (pin "3") (pinfunction "3_3") (pintype "passive"))
      (node (ref "J9") (pin "3") (pinfunction "3_3") (pintype "passive"))
      (node (ref "L2") (pin "2") (pinfunction "2_2") (pintype "passive"))
    )
    (net (code "13") (name "ACT_EN_B") (class "Default")
      (node (ref "IC3") (pin "54") (pinfunction "CN73/RPI44/RF7_54") (pintype "bidirectional"))
    )
    (net (code "14") (name "ACT_S1_B") (class "Default")
      (node (ref "IC3") (pin "52") (pinfunction "CN70/RP30/RF2_52") (pintype "bidirectional"))
      (node (ref "Q20") (pin "1") (pinfunction "G_1") (pintype "passive"))
      (node (ref "R183") (pin "1") (pinfunction "1_1") (pintype "passive"))
    )
    (net (code "15") (name "ACT_S2_B") (class "Default")
      (node (ref "IC3") (pin "53") (pinfunction "CN74/RP15/RF8_53") (pintype "bidirectional"))
      (node (ref "Q21") (pin "1") (pinfunction "G_1") (pintype "passive"))
      (node (ref "R184") (pin "1") (pinfunction "1_1") (pintype "passive"))
    )
    (net (code "16") (name "ACT_S3_B") (class "Default")
      (node (ref "IC3") (pin "88") (pinfunction "CN69/RF1_88") (pintype "bidirectional"))
      (node (ref "Q9") (pin "1") (pinfunction "G_1") (pintype "passive"))
      (node (ref "R30") (pin "1") (pinfunction "1_1") (pintype "passive"))
    )
    (net (code "17") (name "ACT_S4_B") (class "Default")
      (node (ref "IC3") (pin "49") (pinfunction "CN17/RP10/RF4_49") (pintype "bidirectional"))
      (node (ref "Q8") (pin "1") (pinfunction "G_1") (pintype "passive"))
      (node (ref "R29") (pin "1") (pinfunction "1_1") (pintype "passive"))
    )
    (net (code "18") (name "AGND") (class "Default")
      (node (ref "C165") (pin "2") (pinfunction "2_2") (pintype "passive"))
      (node (ref "C166") (pin "2") (pinfunction "2_2") (pintype "passive"))
      (node (ref "C167") (pin "2") (pinfunction "2_2") (pintype "passive"))
      (node (ref "C168") (pin "2") (pinfunction "2_2") (pintype "passive"))
      (node (ref "C169") (pin "2") (pinfunction "2_2") (pintype "passive"))
      (node (ref "C170") (pin "2") (pinfunction "2_2") (pintype "passive"))
      (node (ref "C171") (pin "2") (pinfunction "2_2") (pintype "passive"))
      (node (ref "C172") (pin "2") (pinfunction "2_2") (pintype "passive"))
      (node (ref "C176") (pin "2") (pinfunction "2_2") (pintype "passive"))
      (node (ref "C177") (pin "1") (pinfunction "1_1") (pintype "passive"))
      (node (ref "C179") (pin "2") (pinfunction "2_2") (pintype "passive"))
      (node (ref "C180") (pin "2") (pinfunction "2_2") (pintype "passive"))
      (node (ref "C181") (pin "2") (pinfunction "2_2") (pintype "passive"))
      (node (ref "C182") (pin "2") (pinfunction "2_2") (pintype "passive"))
      (node (ref "J46") (pin "1") (pinfunction "1_1") (pintype "passive"))
      (node (ref "J46") (pin "3") (pinfunction "3_3") (pintype "passive"))
      (node (ref "J46") (pin "5") (pinfunction "5_5") (pintype "passive"))
      (node (ref "J47") (pin "3") (pinfunction "3_3") (pintype "passive"))
      (node (ref "J47") (pin "4") (pinfunction "4_4") (pintype "passive"))
      (node (ref "J48") (pin "1") (pinfunction "1_1") (pintype "passive"))
      (node (ref "L17") (pin "2") (pinfunction "2_2") (pintype "passive"))
      (node (ref "Q24") (pin "2") (pinfunction "S_2") (pintype "passive"))
      (node (ref "R202") (pin "2") (pinfunction "2_2") (pintype "passive"))
      (node (ref "R203") (pin "2") (pinfunction "2_2") (pintype "passive"))
      (node (ref "R210") (pin "2") (pinfunction "2_2") (pintype "passive"))
      (node (ref "R211") (pin "2") (pinfunction "2_2") (pintype "passive"))
      (node (ref "U8") (pin "19") (pinfunction "PGND_19") (pintype "power_in"))
      (node (ref "U8") (pin "24") (pinfunction "PGND_24") (pintype "power_in"))
      (node (ref "U8") (pin "3") (pinfunction "GND_3") (pintype "power_in"))
      (node (ref "U8") (pin "4") (pinfunction "GND_4") (pintype "power_in"))
      (node (ref "U8") (pin "8") (pinfunction "AGND_8") (pintype "power_in"))
      (node (ref "U8") (pin "EP") (pinfunction "EP_EP") (pintype "power_in"))
      (node (ref "U9") (pin "2") (pinfunction "V-_2") (pintype "power_in"))
    )
    (net (code "19") (name "AUD_AMP_FAULT#") (class "Default")
      (node (ref "R204") (pin "1") (pinfunction "1_1") (pintype "passive"))
      (node (ref "R205") (pin "1") (pinfunction "1_1") (pintype "passive"))
      (node (ref "U8") (pin "1") (pinfunction "~{SD}_1") (pintype "input"))
      (node (ref "U8") (pin "2") (pinfunction "~{FAULT}_2") (pintype "output"))
    )
    (net (code "20") (name "AUD_AMP_G0") (class "Default")
      (node (ref "IC3") (pin "41") (pinfunction "RB12/AN12/CN30_41") (pintype "bidirectional"))
      (node (ref "R200") (pin "2") (pinfunction "2_2") (pintype "passive"))
      (node (ref "R202") (pin "1") (pinfunction "1_1") (pintype "passive"))
      (node (ref "TP4") (pin "P$1") (pinfunction "TP_P$1") (pintype "passive"))
      (node (ref "U8") (pin "5") (pinfunction "GAIN0_5") (pintype "input"))
    )
    (net (code "21") (name "AUD_AMP_G1") (class "Default")
      (node (ref "IC3") (pin "42") (pinfunction "RB13/AN13/CN31_42") (pintype "bidirectional"))
      (node (ref "R201") (pin "2") (pinfunction "2_2") (pintype "passive"))
      (node (ref "R203") (pin "1") (pinfunction "1_1") (pintype "passive"))
      (node (ref "TP5") (pin "P$1") (pinfunction "TP_P$1") (pintype "passive"))
      (node (ref "U8") (pin "6") (pinfunction "GAIN1_6") (pintype "input"))
    )
    (net (code "22") (name "AUD_AMP_INN") (class "Default")
      (node (ref "C177") (pin "2") (pinfunction "2_2") (pintype "passive"))
      (node (ref "U8") (pin "11") (pinfunction "INN_11") (pintype "input"))
    )
    (net (code "23") (name "AUD_AMP_INP") (class "Default")
      (node (ref "C174") (pin "2") (pinfunction "2_2") (pintype "passive"))
      (node (ref "C175") (pin "2") (pinfunction "2_2") (pintype "passive"))
      (node (ref "U8") (pin "12") (pinfunction "INP_12") (pintype "input"))
    )
    (net (code "24") (name "AUD_BSN") (class "Default")
      (node (ref "C178") (pin "1") (pinfunction "1_1") (pintype "passive"))
      (node (ref "U8") (pin "22") (pinfunction "BSN_22") (pintype "input"))
      (node (ref "U8") (pin "26") (pinfunction "BSN_26") (pintype "input"))
    )
    (net (code "25") (name "AUD_BSP") (class "Default")
      (node (ref "C173") (pin "1") (pinfunction "1_1") (pintype "passive"))
      (node (ref "U8") (pin "17") (pinfunction "BSP_17") (pintype "input"))
      (node (ref "U8") (pin "21") (pinfunction "BSP_21") (pintype "input"))
    )
    (net (code "26") (name "AUD_GVDD") (class "Default")
      (node (ref "C172") (pin "1") (pinfunction "1_1") (pintype "passive"))
      (node (ref "U8") (pin "10") (pinfunction "PLIMIT_10") (pintype "input"))
      (node (ref "U8") (pin "9") (pinfunction "GVDD_9") (pintype "output"))
    )
    (net (code "27") (name "B-") (class "Default")
      (node (ref "IC2") (pin "7") (pinfunction "B_7") (pintype "bidirectional"))
      (node (ref "L1") (pin "1") (pinfunction "1_1") (pintype "passive"))
      (node (ref "Q3") (pin "2") (pinfunction "2_2") (pintype "passive"))
      (node (ref "R10") (pin "2") (pinfunction "2_2") (pintype "passive"))
      (node (ref "R9") (pin "2") (pinfunction "2_2") (pintype "passive"))
    )
    (net (code "28") (name "B1") (class "Default")
      (node (ref "J7") (pin "4") (pinfunction "4_4") (pintype "passive"))
      (node (ref "J9") (pin "4") (pinfunction "4_4") (pintype "passive"))
      (node (ref "L1") (pin "2") (pinfunction "2_2") (pintype "passive"))
    )
    (net (code "29") (name "B12_BOOT") (class "Default")
      (node (ref "C126") (pin "1") (pinfunction "1_1") (pintype "passive"))
      (node (ref "U6") (pin "11") (pinfunction "BOOT_11") (pintype "passive"))
    )
    (net (code "30") (name "B12_COMP") (class "Default")
      (node (ref "C131") (pin "1") (pinfunction "1_1") (pintype "passive"))
      (node (ref "R164") (pin "2") (pinfunction "2_2") (pintype "passive"))
      (node (ref "U6") (pin "3") (pinfunction "COMP_3") (pintype "passive"))
    )
    (net (code "31") (name "B12_FB") (class "Default")
      (node (ref "R160") (pin "1") (pinfunction "1_1") (pintype "passive"))
      (node (ref "R166") (pin "2") (pinfunction "2_2") (pintype "passive"))
      (node (ref "U6") (pin "4") (pinfunction "FB_4") (pintype "input"))
    )
    (net (code "32") (name "B12_FEED") (class "Default")
      (node (ref "L11") (pin "2") (pinfunction "2_2") (pintype "passive"))
      (node (ref "R153") (pin "2") (pinfunction "2_2") (pintype "passive"))
      (node (ref "R155") (pin "2") (pinfunction "2_2") (pintype "passive"))
      (node (ref "R158") (pin "2") (pinfunction "2_2") (pintype "passive"))
    )
    (net (code "33") (name "B12_HDRV") (class "Default")
      (node (ref "R161") (pin "2") (pinfunction "2_2") (pintype "passive"))
      (node (ref "U6") (pin "13") (pinfunction "HDRV_13") (pintype "output"))
    )
    (net (code "34") (name "B12_HG") (class "Default")
      (node (ref "Q16") (pin "3") (pinfunction "TG_3") (pintype "passive"))
      (node (ref "R161") (pin "1") (pinfunction "1_1") (pintype "passive"))
    )
    (net (code "35") (name "B12_ISNS+") (class "Default")
      (node (ref "C124") (pin "1") (pinfunction "1_1") (pintype "passive"))
      (node (ref "R157") (pin "1") (pinfunction "1_1") (pintype "passive"))
      (node (ref "U6") (pin "6") (pinfunction "ISNS+_6") (pintype "input"))
    )
    (net (code "36") (name "B12_ISNS-") (class "Default")
      (node (ref "C124") (pin "2") (pinfunction "2_2") (pintype "passive"))
      (node (ref "R158") (pin "1") (pinfunction "1_1") (pintype "passive"))
      (node (ref "U6") (pin "5") (pinfunction "ISNS-_5") (pintype "input"))
    )
    (net (code "37") (name "B12_L") (class "Default")
      (node (ref "D20") (pin "A") (pinfunction "A_A") (pintype "passive"))
      (node (ref "L11") (pin "1") (pinfunction "1_1") (pintype "passive"))
      (node (ref "Q16") (pin "6") (pinfunction "VSW_6") (pintype "passive"))
      (node (ref "Q16") (pin "7") (pinfunction "VSW_7") (pintype "passive"))
      (node (ref "Q16") (pin "8") (pinfunction "VSW_8") (pintype "passive"))
    )
    (net (code "38") (name "B12_LDRV") (class "Default")
      (node (ref "R163") (pin "2") (pinfunction "2_2") (pintype "passive"))
      (node (ref "U6") (pin "8") (pinfunction "LDRV_8") (pintype "output"))
    )
    (net (code "39") (name "B12_LG") (class "Default")
      (node (ref "Q16") (pin "5") (pinfunction "BG_5") (pintype "passive"))
      (node (ref "R163") (pin "1") (pinfunction "1_1") (pintype "passive"))
    )
    (net (code "40") (name "B12_PG") (class "Default")
      (node (ref "IC3") (pin "69") (pinfunction "CN54/RP4/RD9_69") (pintype "bidirectional"))
      (node (ref "R167") (pin "1") (pinfunction "1_1") (pintype "passive"))
      (node (ref "U6") (pin "14") (pinfunction "PGOOD_14") (pintype "open_collector"))
    )
    (net (code "41") (name "B12_RC") (class "Default")
      (node (ref "C133") (pin "1") (pinfunction "1_1") (pintype "passive"))
      (node (ref "R164") (pin "1") (pinfunction "1_1") (pintype "passive"))
    )
    (net (code "42") (name "B12_RT") (class "Default")
      (node (ref "R165") (pin "2") (pinfunction "2_2") (pintype "passive"))
      (node (ref "U6") (pin "1") (pinfunction "RT/CLK_1") (pintype "passive"))
    )
    (net (code "43") (name "B12_SS") (class "Default")
      (node (ref "C132") (pin "1") (pinfunction "1_1") (pintype "passive"))
      (node (ref "U6") (pin "2") (pinfunction "SS_2") (pintype "passive"))
    )
    (net (code "44") (name "B12_SW") (class "Default")
      (node (ref "C126") (pin "2") (pinfunction "2_2") (pintype "passive"))
      (node (ref "Q16") (pin "4") (pinfunction "TGR_4") (pintype "passive"))
      (node (ref "U6") (pin "12") (pinfunction "SW_12") (pintype "output"))
    )
    (net (code "45") (name "B12_VCC") (class "Default")
      (node (ref "C127") (pin "1") (pinfunction "1_1") (pintype "passive"))
      (node (ref "U6") (pin "10") (pinfunction "VCC_10") (pintype "output"))
    )
    (net (code "46") (name "BAT_GND") (class "Default")
      (node (ref "JP3") (pin "P1") (pinfunction "1_P1") (pintype "passive"))
      (node (ref "JP4") (pin "P1") (pinfunction "1_P1") (pintype "passive"))
      (node (ref "R36") (pin "1") (pinfunction "1_1") (pintype "passive"))
      (node (ref "U3") (pin "7") (pinfunction "AIN3_7") (pintype "bidirectional"))
    )
    (net (code "47") (name "BAT_SENSE") (class "Default")
      (node (ref "JP3") (pin "P2") (pinfunction "2_P2") (pintype "passive"))
      (node (ref "JP4") (pin "P2") (pinfunction "2_P2") (pintype "passive"))
      (node (ref "R35") (pin "2") (pinfunction "2_2") (pintype "passive"))
    )
    (net (code "48") (name "BTN_1") (class "Default")
      (node (ref "IC4") (pin "1") (pinfunction "GP0/PGD_1") (pintype "bidirectional"))
      (node (ref "J12") (pin "4") (pinfunction "4_4") (pintype "passive"))
      (node (ref "J5") (pin "2") (pinfunction "2_2") (pintype "passive"))
      (node (ref "R2") (pin "2") (pinfunction "1_2") (pintype "passive"))
      (node (ref "R2") (pin "3") (pinfunction "1_3") (pintype "passive"))
    )
    (net (code "49") (name "BTN_1PIN_B") (class "Default")
      (node (ref "C12") (pin "1") (pinfunction "1_1") (pintype "passive"))
      (node (ref "IC3") (pin "90") (pinfunction "RG0/CN77_90") (pintype "bidirectional"))
      (node (ref "R2") (pin "6") (pinfunction "2_6") (pintype "passive"))
    )
    (net (code "50") (name "BTN_2") (class "Default")
      (node (ref "IC4") (pin "3") (pinfunction "GP1/PGC_3") (pintype "bidirectional"))
      (node (ref "J12") (pin "5") (pinfunction "5_5") (pintype "passive"))
      (node (ref "J6") (pin "2") (pinfunction "2_2") (pintype "passive"))
      (node (ref "R2") (pin "1") (pinfunction "1_1") (pintype "passive"))
      (node (ref "R2") (pin "4") (pinfunction "1_4") (pintype "passive"))
    )
    (net (code "51") (name "BTN_2PIN_B") (class "Default")
      (node (ref "C13") (pin "1") (pinfunction "1_1") (pintype "passive"))
      (node (ref "IC3") (pin "89") (pinfunction "RG1/CN78_89") (pintype "bidirectional"))
      (node (ref "R2") (pin "5") (pinfunction "2_5") (pintype "passive"))
    )
    (net (code "52") (name "CL_IRQ") (class "Default")
      (node (ref "IC3") (pin "20") (pinfunction "RB5/AN5/CN7/RP18_20") (pintype "bidirectional"))
      (node (ref "J1") (pin "4") (pinfunction "4_4") (pintype "passive"))
      (node (ref "J3") (pin "9") (pinfunction "9_9") (pintype "passive"))
    )
    (net (code "53") (name "CM_RST") (class "Default")
      (node (ref "IC3") (pin "98") (pinfunction "CN60/RE2_98") (pintype "bidirectional"))
      (node (ref "J8") (pin "5") (pinfunction "5_5") (pintype "passive"))
    )
    (net (code "54") (name "DCDC_12V_EN") (class "Default")
      (node (ref "IC3") (pin "84") (pinfunction "CN16/RD7_84") (pintype "bidirectional"))
      (node (ref "Q15") (pin "2") (pinfunction "G_2") (pintype "passive"))
      (node (ref "R162") (pin "2") (pinfunction "2_2") (pintype "passive"))
      (node (ref "U6") (pin "15") (pinfunction "EN_15") (pintype "input"))
    )
    (net (code "55") (name "DGND") (class "Default")
      (node (ref "B1") (pin "-") (pinfunction "-_-") (pintype "passive"))
      (node (ref "C1") (pin "2") (pinfunction "2_2") (pintype "passive"))
      (node (ref "C10") (pin "1") (pinfunction "1_1") (pintype "passive"))
      (node (ref "C11") (pin "2") (pinfunction "2_2") (pintype "passive"))
      (node (ref "C114") (pin "1") (pinfunction "1_1") (pintype "passive"))
      (node (ref "C115") (pin "1") (pinfunction "1_1") (pintype "passive"))
      (node (ref "C12") (pin "2") (pinfunction "2_2") (pintype "passive"))
      (node (ref "C121") (pin "1") (pinfunction "1_1") (pintype "passive"))
      (node (ref "C122") (pin "2") (pinfunction "2_2") (pintype "passive"))
      (node (ref "C123") (pin "2") (pinfunction "2_2") (pintype "passive"))
      (node (ref "C125") (pin "2") (pinfunction "2_2") (pintype "passive"))
      (node (ref "C127") (pin "2") (pinfunction "2_2") (pintype "passive"))
      (node (ref "C128") (pin "2") (pinfunction "2_2") (pintype "passive"))
      (node (ref "C129") (pin "2") (pinfunction "2_2") (pintype "passive"))
      (node (ref "C13") (pin "2") (pinfunction "2_2") (pintype "passive"))
      (node (ref "C130") (pin "2") (pinfunction "2_2") (pintype "passive"))
      (node (ref "C131") (pin "2") (pinfunction "2_2") (pintype "passive"))
      (node (ref "C132") (pin "2") (pinfunction "2_2") (pintype "passive"))
      (node (ref "C133") (pin "2") (pinfunction "2_2") (pintype "passive"))
      (node (ref "C134") (pin "2") (pinfunction "2_2") (pintype "passive"))
      (node (ref "C135") (pin "2") (pinfunction "2_2") (pintype "passive"))
      (node (ref "C136") (pin "2") (pinfunction "2_2") (pintype "passive"))
      (node (ref "C137") (pin "2") (pinfunction "2_2") (pintype "passive"))
      (node (ref "C139") (pin "2") (pinfunction "2_2") (pintype "passive"))
      (node (ref "C14") (pin "2") (pinfunction "2_2") (pintype "passive"))
      (node (ref "C141") (pin "2") (pinfunction "2_2") (pintype "passive"))
      (node (ref "C142") (pin "2") (pinfunction "2_2") (pintype "passive"))
      (node (ref "C143") (pin "2") (pinfunction "2_2") (pintype "passive"))
      (node (ref "C144") (pin "2") (pinfunction "2_2") (pintype "passive"))
      (node (ref "C145") (pin "2") (pinfunction "2_2") (pintype "passive"))
      (node (ref "C146") (pin "2") (pinfunction "2_2") (pintype "passive"))
      (node (ref "C147") (pin "2") (pinfunction "2_2") (pintype "passive"))
      (node (ref "C148") (pin "2") (pinfunction "2_2") (pintype "passive"))
      (node (ref "C149") (pin "2") (pinfunction "2_2") (pintype "passive"))
      (node (ref "C150") (pin "2") (pinfunction "2_2") (pintype "passive"))
      (node (ref "C152") (pin "2") (pinfunction "2_2") (pintype "passive"))
      (node (ref "C153") (pin "2") (pinfunction "2_2") (pintype "passive"))
      (node (ref "C154") (pin "2") (pinfunction "2_2") (pintype "passive"))
      (node (ref "C156") (pin "2") (pinfunction "PIN-_2") (pintype "passive"))
      (node (ref "C157") (pin "2") (pinfunction "2_2") (pintype "passive"))
      (node (ref "C158") (pin "2") (pinfunction "2_2") (pintype "passive"))
      (node (ref "C16") (pin "1") (pinfunction "1_1") (pintype "passive"))
      (node (ref "C161") (pin "2") (pinfunction "2_2") (pintype "passive"))
      (node (ref "C162") (pin "2") (pinfunction "2_2") (pintype "passive"))
      (node (ref "C163") (pin "2") (pinfunction "2_2") (pintype "passive"))
      (node (ref "C164") (pin "2") (pinfunction "2_2") (pintype "passive"))
      (node (ref "C17") (pin "2") (pinfunction "2_2") (pintype "passive"))
      (node (ref "C18") (pin "1") (pinfunction "1_1") (pintype "passive"))
      (node (ref "C187") (pin "2") (pinfunction "PIN-_2") (pintype "passive"))
      (node (ref "C19") (pin "1") (pinfunction "1_1") (pintype "passive"))
      (node (ref "C2") (pin "2") (pinfunction "2_2") (pintype "passive"))
      (node (ref "C20") (pin "1") (pinfunction "1_1") (pintype "passive"))
      (node (ref "C21") (pin "2") (pinfunction "2_2") (pintype "passive"))
      (node (ref "C22") (pin "2") (pinfunction "2_2") (pintype "passive"))
      (node (ref "C23") (pin "1") (pinfunction "1_1") (pintype "passive"))
      (node (ref "C24") (pin "2") (pinfunction "2_2") (pintype "passive"))
      (node (ref "C25") (pin "2") (pinfunction "2_2") (pintype "passive"))
      (node (ref "C26") (pin "2") (pinfunction "2_2") (pintype "passive"))
      (node (ref "C27") (pin "2") (pinfunction "2_2") (pintype "passive"))
      (node (ref "C28") (pin "2") (pinfunction "2_2") (pintype "passive"))
      (node (ref "C29") (pin "1") (pinfunction "1_1") (pintype "passive"))
      (node (ref "C3") (pin "2") (pinfunction "2_2") (pintype "passive"))
      (node (ref "C32") (pin "2") (pinfunction "2_2") (pintype "passive"))
      (node (ref "C33") (pin "2") (pinfunction "2_2") (pintype "passive"))
      (node (ref "C34") (pin "2") (pinfunction "2_2") (pintype "passive"))
      (node (ref "C35") (pin "1") (pinfunction "1_1") (pintype "passive"))
      (node (ref "C36") (pin "2") (pinfunction "2_2") (pintype "passive"))
      (node (ref "C37") (pin "2") (pinfunction "2_2") (pintype "passive"))
      (node (ref "C4") (pin "2") (pinfunction "2_2") (pintype "passive"))
      (node (ref "C5") (pin "2") (pinfunction "2_2") (pintype "passive"))
      (node (ref "C6") (pin "2") (pinfunction "2_2") (pintype "passive"))
      (node (ref "C7") (pin "2") (pinfunction "2_2") (pintype "passive"))
      (node (ref "C8") (pin "2") (pinfunction "2_2") (pintype "passive"))
      (node (ref "C9") (pin "2") (pinfunction "2_2") (pintype "passive"))
      (node (ref "D21") (pin "-") (pinfunction "A_-") (pintype "passive"))
      (node (ref "D25") (pin "A") (pinfunction "A_A") (pintype "passive"))
      (node (ref "D26") (pin "A") (pinfunction "A_A") (pintype "passive"))
      (node (ref "D27") (pin "-") (pinfunction "A_-") (pintype "passive"))
      (node (ref "D28") (pin "-") (pinfunction "A_-") (pintype "passive"))
      (node (ref "D29") (pin "A") (pinfunction "A_A") (pintype "passive"))
      (node (ref "D30") (pin "A") (pinfunction "A_A") (pintype "passive"))
      (node (ref "D31") (pin "1") (pinfunction "A_1") (pintype "passive"))
      (node (ref "D31") (pin "2") (pinfunction "A_2") (pintype "passive"))
      (node (ref "D32") (pin "A") (pinfunction "A_A") (pintype "passive"))
      (node (ref "D4") (pin "A") (pinfunction "A_A") (pintype "passive"))
      (node (ref "D5") (pin "A") (pinfunction "A_A") (pintype "passive"))
      (node (ref "D6") (pin "A") (pinfunction "A_A") (pintype "passive"))
      (node (ref "D9") (pin "-") (pinfunction "A_-") (pintype "passive"))
      (node (ref "H2") (pin "P1") (pinfunction "P$1_P1") (pintype "bidirectional"))
      (node (ref "H3") (pin "P1") (pinfunction "P$1_P1") (pintype "bidirectional"))
      (node (ref "H4") (pin "P1") (pinfunction "P$1_P1") (pintype "bidirectional"))
      (node (ref "H5") (pin "P1") (pinfunction "P$1_P1") (pintype "bidirectional"))
      (node (ref "H6") (pin "P1") (pinfunction "P$1_P1") (pintype "bidirectional"))
      (node (ref "IC1") (pin "3") (pinfunction "GND_3") (pintype "power_in"))
      (node (ref "IC18") (pin "18") (pinfunction "GND2_18") (pintype "power_in"))
      (node (ref "IC18") (pin "21") (pinfunction "GND3_21") (pintype "power_in"))
      (node (ref "IC18") (pin "25") (pinfunction "AGND_25") (pintype "power_in"))
      (node (ref "IC18") (pin "26") (pinfunction "TEST_26") (pintype "bidirectional"))
      (node (ref "IC18") (pin "7") (pinfunction "GND1_7") (pintype "power_in"))
      (node (ref "IC19") (pin "4") (pinfunction "V-_4") (pintype "power_in"))
      (node (ref "IC2") (pin "5") (pinfunction "GND_5") (pintype "power_in"))
      (node (ref "IC20") (pin "4") (pinfunction "GND_4") (pintype "power_in"))
      (node (ref "IC21") (pin "4") (pinfunction "GND_4") (pintype "power_in"))
      (node (ref "IC3") (pin "15") (pinfunction "VSS15_15") (pintype "power_in"))
      (node (ref "IC3") (pin "31") (pinfunction "AVSS_31") (pintype "power_in"))
      (node (ref "IC3") (pin "36") (pinfunction "VSS36_36") (pintype "power_in"))
      (node (ref "IC3") (pin "45") (pinfunction "VSS45_45") (pintype "power_in"))
      (node (ref "IC3") (pin "65") (pinfunction "VSS65_65") (pintype "power_in"))
      (node (ref "IC3") (pin "75") (pinfunction "VSS75_75") (pintype "power_in"))
      (node (ref "IC4") (pin "2") (pinfunction "VSS_2") (pintype "power_in"))
      (node (ref "IC5") (pin "4") (pinfunction "GND_4") (pintype "power_in"))
      (node (ref "IC5") (pin "5") (pinfunction "A2_5") (pintype "input"))
      (node (ref "IC5") (pin "6") (pinfunction "A1_6") (pintype "input"))
      (node (ref "IC6") (pin "1") (pinfunction "A0_1") (pintype "input"))
      (node (ref "IC6") (pin "2") (pinfunction "A1_2") (pintype "input"))
      (node (ref "IC6") (pin "3") (pinfunction "A2_3") (pintype "input"))
      (node (ref "IC6") (pin "4") (pinfunction "GND_4") (pintype "power_in"))
      (node (ref "IC6") (pin "7") (pinfunction "WP_7") (pintype "input"))
      (node (ref "IC7") (pin "12") (pinfunction "CLKOE_12") (pintype "input"))
      (node (ref "IC7") (pin "7") (pinfunction "VSS_7") (pintype "power_in"))
      (node (ref "IC8") (pin "4") (pinfunction "GND_4") (pintype "power_in"))
      (node (ref "IC9") (pin "2") (pinfunction "GND_2") (pintype "power_in"))
      (node (ref "J1") (pin "1") (pinfunction "1_1") (pintype "passive"))
      (node (ref "J10") (pin "C5") (pinfunction "C5_C5") (pintype "bidirectional"))
      (node (ref "J11") (pin "3") (pinfunction "3_3") (pintype "passive"))
      (node (ref "J12") (pin "3") (pinfunction "3_3") (pintype "passive"))
      (node (ref "J13") (pin "1") (pinfunction "1_1") (pintype "passive"))
      (node (ref "J15") (pin "1") (pinfunction "1_1") (pintype "passive"))
      (node (ref "J16") (pin "1") (pinfunction "1_1") (pintype "passive"))
      (node (ref "J2") (pin "1") (pinfunction "1_1") (pintype "passive"))
      (node (ref "J3") (pin "23") (pinfunction "23_23") (pintype "passive"))
      (node (ref "J4") (pin "4") (pinfunction "4_4") (pintype "passive"))
      (node (ref "J4") (pin "5") (pinfunction "5_5") (pintype "passive"))
      (node (ref "J40") (pin "5") (pinfunction "5_5") (pintype "bidirectional"))
      (node (ref "J40") (pin "S1") (pinfunction "GND1_S1") (pintype "bidirectional"))
      (node (ref "J40") (pin "S2") (pinfunction "GND2_S2") (pintype "bidirectional"))
      (node (ref "J40") (pin "S3") (pinfunction "GND3_S3") (pintype "bidirectional"))
      (node (ref "J40") (pin "S4") (pinfunction "GND4_S4") (pintype "bidirectional"))
      (node (ref "J41") (pin "1") (pinfunction "1_1") (pintype "passive"))
      (node (ref "J43") (pin "1") (pinfunction "1_1") (pintype "passive"))
      (node (ref "J44") (pin "1") (pinfunction "1_1") (pintype "passive"))
      (node (ref "J45") (pin "1") (pinfunction "1_1") (pintype "passive"))
      (node (ref "J5") (pin "1") (pinfunction "1_1") (pintype "passive"))
      (node (ref "J50") (pin "1") (pinfunction "1_1") (pintype "passive"))
      (node (ref "J6") (pin "1") (pinfunction "1_1") (pintype "passive"))
      (node (ref "J7") (pin "1") (pinfunction "1_1") (pintype "passive"))
      (node (ref "J7") (pin "6") (pinfunction "6_6") (pintype "passive"))
      (node (ref "J8") (pin "9") (pinfunction "9_9") (pintype "passive"))
      (node (ref "J9") (pin "1") (pinfunction "1_1") (pintype "passive"))
      (node (ref "J9") (pin "6") (pinfunction "6_6") (pintype "passive"))
      (node (ref "JP5") (pin "P1") (pinfunction "1_P1") (pintype "passive"))
      (node (ref "L17") (pin "1") (pinfunction "1_1") (pintype "passive"))
      (node (ref "Q14") (pin "1") (pinfunction "GND_1") (pintype "power_in"))
      (node (ref "Q14") (pin "2") (pinfunction "GND1_2") (pintype "power_in"))
      (node (ref "Q15") (pin "1") (pinfunction "S_1") (pintype "passive"))
      (node (ref "Q16") (pin "EP") (pinfunction "PGND_EP") (pintype "passive"))
      (node (ref "Q17") (pin "1") (pinfunction "GND_1") (pintype "power_in"))
      (node (ref "Q17") (pin "2") (pinfunction "GND1_2") (pintype "power_in"))
      (node (ref "Q18") (pin "1") (pinfunction "S_1") (pintype "passive"))
      (node (ref "Q19") (pin "EP") (pinfunction "PGND_EP") (pintype "passive"))
      (node (ref "Q2") (pin "1") (pinfunction "Q1S_1") (pintype "bidirectional"))
      (node (ref "Q20") (pin "2") (pinfunction "S_2") (pintype "passive"))
      (node (ref "Q21") (pin "2") (pinfunction "S_2") (pintype "passive"))
      (node (ref "Q3") (pin "1") (pinfunction "1_1") (pintype "passive"))
      (node (ref "Q5") (pin "1") (pinfunction "Q1S_1") (pintype "bidirectional"))
      (node (ref "Q8") (pin "2") (pinfunction "S_2") (pintype "passive"))
      (node (ref "Q9") (pin "2") (pinfunction "S_2") (pintype "passive"))
      (node (ref "R10") (pin "1") (pinfunction "1_1") (pintype "passive"))
      (node (ref "R13") (pin "1") (pinfunction "1_1") (pintype "passive"))
      (node (ref "R162") (pin "1") (pinfunction "1_1") (pintype "passive"))
      (node (ref "R165") (pin "1") (pinfunction "1_1") (pintype "passive"))
      (node (ref "R166") (pin "1") (pinfunction "1_1") (pintype "passive"))
      (node (ref "R174") (pin "2") (pinfunction "2_2") (pintype "passive"))
      (node (ref "R179") (pin "1") (pinfunction "1_1") (pintype "passive"))
      (node (ref "R182") (pin "1") (pinfunction "1_1") (pintype "passive"))
      (node (ref "R183") (pin "2") (pinfunction "2_2") (pintype "passive"))
      (node (ref "R184") (pin "2") (pinfunction "2_2") (pintype "passive"))
      (node (ref "R185") (pin "1") (pinfunction "1_1") (pintype "passive"))
      (node (ref "R195") (pin "2") (pinfunction "2_2") (pintype "passive"))
      (node (ref "R196") (pin "2") (pinfunction "2_2") (pintype "passive"))
      (node (ref "R197") (pin "2") (pinfunction "2_2") (pintype "passive"))
      (node (ref "R20") (pin "2") (pinfunction "1_2") (pintype "passive"))
      (node (ref "R21") (pin "5") (pinfunction "2_5") (pintype "passive"))
      (node (ref "R21") (pin "6") (pinfunction "2_6") (pintype "passive"))
      (node (ref "R22") (pin "1") (pinfunction "1_1") (pintype "passive"))
      (node (ref "R25") (pin "1") (pinfunction "1_1") (pintype "passive"))
      (node (ref "R29") (pin "2") (pinfunction "2_2") (pintype "passive"))
      (node (ref "R30") (pin "2") (pinfunction "2_2") (pintype "passive"))
      (node (ref "R5") (pin "1") (pinfunction "1_1") (pintype "passive"))
      (node (ref "R6") (pin "1") (pinfunction "1_1") (pintype "passive"))
      (node (ref "TP11") (pin "P$1") (pinfunction "TP_P$1") (pintype "passive"))
      (node (ref "TP12") (pin "1") (pinfunction "TP_1") (pintype "passive"))
      (node (ref "TP66") (pin "1") (pinfunction "TP_1") (pintype "passive"))
      (node (ref "TP67") (pin "1") (pinfunction "TP_1") (pintype "passive"))
      (node (ref "U1") (pin "10") (pinfunction "PGND_10") (pintype "bidirectional"))
      (node (ref "U1") (pin "21") (pinfunction "PRESB_21") (pintype "bidirectional"))
      (node (ref "U1") (pin "9") (pinfunction "SGND_9") (pintype "bidirectional"))
      (node (ref "U1") (pin "PAD") (pinfunction "PAD_PAD") (pintype "bidirectional"))
      (node (ref "U2") (pin "7") (pinfunction "GND_7") (pintype "bidirectional"))
      (node (ref "U3") (pin "3") (pinfunction "VSS_3") (pintype "bidirectional"))
      (node (ref "U6") (pin "16") (pinfunction "AGND_16") (pintype "power_in"))
      (node (ref "U6") (pin "9") (pinfunction "PGND_9") (pintype "power_in"))
      (node (ref "U6") (pin "EP") (pinfunction "PPAD_EP") (pintype "power_in"))
      (node (ref "U7") (pin "16") (pinfunction "AGND_16") (pintype "power_in"))
      (node (ref "U7") (pin "9") (pinfunction "PGND_9") (pintype "power_in"))
      (node (ref "U7") (pin "EP") (pinfunction "PPAD_EP") (pintype "power_in"))
      (node (ref "X1") (pin "7") (pinfunction "1_7") (pintype "passive"))
      (node (ref "X1") (pin "8") (pinfunction "1_8") (pintype "passive"))
    )
    (net (code "56") (name "DIN_SM") (class "Default")
      (node (ref "IC3") (pin "6") (pinfunction "RC1/CN45/RPI38_6") (pintype "bidirectional"))
      (node (ref "U1") (pin "27") (pinfunction "DIN_27") (pintype "bidirectional"))
    )
    (net (code "57") (name "DOOR_L") (class "Default")
      (node (ref "IC3") (pin "73") (pinfunction "RC13/SOSCI/CN1_73") (pintype "bidirectional"))
      (node (ref "R21") (pin "2") (pinfunction "1_2") (pintype "passive"))
      (node (ref "R21") (pin "3") (pinfunction "1_3") (pintype "passive"))
    )
    (net (code "58") (name "DOOR_L_SW") (class "Default")
      (node (ref "C25") (pin "1") (pinfunction "1_1") (pintype "passive"))
      (node (ref "J13") (pin "2") (pinfunction "2_2") (pintype "passive"))
      (node (ref "R18") (pin "2") (pinfunction "2_2") (pintype "passive"))
      (node (ref "R21") (pin "7") (pinfunction "2_7") (pintype "passive"))
    )
    (net (code "59") (name "DOOR_ON") (class "Default")
      (node (ref "IC3") (pin "87") (pinfunction "CN68/RF0_87") (pintype "bidirectional"))
      (node (ref "Q5") (pin "5") (pinfunction "Q1G_5") (pintype "input"))
      (node (ref "R20") (pin "7") (pinfunction "2_7") (pintype "passive"))
    )
    (net (code "60") (name "DOOR_R") (class "Default")
      (node (ref "IC3") (pin "83") (pinfunction "CN15/RD6_83") (pintype "bidirectional"))
      (node (ref "R21") (pin "1") (pinfunction "1_1") (pintype "passive"))
      (node (ref "R21") (pin "4") (pinfunction "1_4") (pintype "passive"))
    )
    (net (code "61") (name "DOOR_R_SW") (class "Default")
      (node (ref "C26") (pin "1") (pinfunction "1_1") (pintype "passive"))
      (node (ref "J13") (pin "3") (pinfunction "3_3") (pintype "passive"))
      (node (ref "R19") (pin "2") (pinfunction "2_2") (pintype "passive"))
      (node (ref "R21") (pin "8") (pinfunction "2_8") (pintype "passive"))
    )
    (net (code "62") (name "DOUT_SM_B") (class "Default")
      (node (ref "IC3") (pin "7") (pinfunction "RC2/CN46/RPI39_7") (pintype "bidirectional"))
      (node (ref "U1") (pin "28") (pinfunction "DOUT_28") (pintype "bidirectional"))
    )
    (net (code "63") (name "GNDBREAK") (class "Default")
      (node (ref "CN1") (pin "GNDBREAK") (pinfunction "GNDBREAK_GNDBREAK") (pintype "power_in"))
    )
    (net (code "64") (name "ID_PWM") (class "Default")
      (node (ref "IC3") (pin "51") (pinfunction "CN71/RP16/RF3_51") (pintype "bidirectional"))
      (node (ref "R23") (pin "1") (pinfunction "1_1") (pintype "passive"))
    )
    (net (code "65") (name "IOB") (class "Default")
      (node (ref "J10") (pin "C7") (pinfunction "C7_C7") (pintype "bidirectional"))
      (node (ref "U1") (pin "20") (pinfunction "IOB_20") (pintype "bidirectional"))
    )
    (net (code "66") (name "ISENSEA") (class "Default")
      (node (ref "IC19") (pin "1") (pinfunction "OUT_1") (pintype "output"))
      (node (ref "IC19") (pin "2") (pinfunction "-IN_2") (pintype "input"))
      (node (ref "IC3") (pin "43") (pinfunction "RB14/AN14/CN32/RP14_43") (pintype "bidirectional"))
    )
    (net (code "67") (name "ISENSEB") (class "Default")
      (node (ref "IC19") (pin "6") (pinfunction "-IN_6") (pintype "input"))
      (node (ref "IC19") (pin "7") (pinfunction "OUT_7") (pintype "output"))
      (node (ref "IC3") (pin "44") (pinfunction "RB15/AN15/CN12/RP29_44") (pintype "bidirectional"))
    )
    (net (code "68") (name "ISEN_OP_EN") (class "Default")
      (node (ref "C134") (pin "1") (pinfunction "1_1") (pintype "passive"))
      (node (ref "IC19") (pin "8") (pinfunction "V+_8") (pintype "power_in"))
      (node (ref "IC3") (pin "68") (pinfunction "CN53/RP2/RD8_68") (pintype "bidirectional"))
    )
    (net (code "69") (name "LCD_SI") (class "Default")
      (node (ref "IC3") (pin "32") (pinfunction "RB8/AN8/CN26/RP8_32") (pintype "bidirectional"))
    )
    (net (code "70") (name "LD_SM") (class "Default")
      (node (ref "IC3") (pin "9") (pinfunction "RC4/CN48/RPI41_9") (pintype "bidirectional"))
      (node (ref "U1") (pin "25") (pinfunction "/LD_25") (pintype "bidirectional"))
    )
    (net (code "71") (name "MH_DATA") (class "Default")
      (node (ref "IC3") (pin "59") (pinfunction "RA3/SDA2_59") (pintype "bidirectional"))
      (node (ref "J4") (pin "2") (pinfunction "2_2") (pintype "passive"))
    )
    (net (code "72") (name "MH_STROBE") (class "Default")
      (node (ref "IC3") (pin "58") (pinfunction "RA2/SCL2_58") (pintype "bidirectional"))
      (node (ref "J4") (pin "1") (pinfunction "1_1") (pintype "passive"))
    )
    (net (code "73") (name "MICROPHONE") (class "Default")
      (node (ref "J48") (pin "2") (pinfunction "2_2") (pintype "passive"))
      (node (ref "R207") (pin "2") (pinfunction "2_2") (pintype "passive"))
      (node (ref "R208") (pin "1") (pinfunction "1_1") (pintype "passive"))
      (node (ref "U9") (pin "3") (pinfunction "+IN_3") (pintype "input"))
    )
    (net (code "74") (name "MIC_AMP_EN") (class "Default")
      (node (ref "J49") (pin "1") (pinfunction "1_1") (pintype "passive"))
      (node (ref "Q24") (pin "1") (pinfunction "G_1") (pintype "passive"))
      (node (ref "R210") (pin "1") (pinfunction "1_1") (pintype "passive"))
      (node (ref "U9") (pin "5") (pinfunction "~{SHDN}_5") (pintype "power_in"))
    )
    (net (code "75") (name "Net-(C31-Pad1)") (class "Default")
      (node (ref "C31") (pin "1") (pinfunction "1_1") (pintype "passive"))
      (node (ref "C32") (pin "1") (pinfunction "1_1") (pintype "passive"))
      (node (ref "D3") (pin "A") (pinfunction "A_A") (pintype "passive"))
      (node (ref "J14") (pin "2") (pinfunction "2_2") (pintype "passive"))
      (node (ref "L3") (pin "2") (pinfunction "2_2") (pintype "passive"))
    )
    (net (code "76") (name "Net-(C162-Pad1)") (class "Default")
      (node (ref "C162") (pin "1") (pinfunction "1_1") (pintype "passive"))
      (node (ref "R191") (pin "1") (pinfunction "1_1") (pintype "passive"))
    )
    (net (code "77") (name "Net-(C164-Pad1)") (class "Default")
      (node (ref "C164") (pin "1") (pinfunction "1_1") (pintype "passive"))
      (node (ref "R193") (pin "1") (pinfunction "1_1") (pintype "passive"))
    )
    (net (code "78") (name "Net-(C171-Pad1)") (class "Default")
      (node (ref "C171") (pin "1") (pinfunction "1_1") (pintype "passive"))
      (node (ref "R198") (pin "1") (pinfunction "1_1") (pintype "passive"))
      (node (ref "R199") (pin "2") (pinfunction "2_2") (pintype "passive"))
      (node (ref "U8") (pin "7") (pinfunction "AVCC_7") (pintype "power_in"))
    )
    (net (code "79") (name "Net-(C185-Pad2)") (class "Default")
      (node (ref "C185") (pin "2") (pinfunction "2_2") (pintype "passive"))
      (node (ref "R211") (pin "1") (pinfunction "1_1") (pintype "passive"))
    )
    (net (code "80") (name "Net-(D1-A1)") (class "Default")
      (node (ref "B1") (pin "+") (pinfunction "+_+") (pintype "passive"))
      (node (ref "D1") (pin "1") (pinfunction "A1_1") (pintype "passive"))
      (node (ref "TP7") (pin "P$1") (pinfunction "TP_P$1") (pintype "passive"))
    )
    (net (code "81") (name "Net-(D1-K)") (class "Default")
      (node (ref "C24") (pin "1") (pinfunction "1_1") (pintype "passive"))
      (node (ref "D1") (pin "3") (pinfunction "K_3") (pintype "passive"))
      (node (ref "IC7") (pin "14") (pinfunction "VDD_14") (pintype "power_in"))
    )
    (net (code "82") (name "Net-(D2-K)") (class "Default")
      (node (ref "C30") (pin "1") (pinfunction "1_1") (pintype "passive"))
      (node (ref "D2") (pin "C") (pinfunction "K_C") (pintype "passive"))
      (node (ref "D3") (pin "C") (pinfunction "K_C") (pintype "passive"))
      (node (ref "IC9") (pin "1") (pinfunction "BOOST_1") (pintype "input"))
    )
    (net (code "83") (name "Net-(D7-A)") (class "Default")
      (node (ref "D7") (pin "2") (pinfunction "A_2") (pintype "passive"))
      (node (ref "R27") (pin "1") (pinfunction "1_1") (pintype "passive"))
    )
    (net (code "84") (name "Net-(D8-A)") (class "Default")
      (node (ref "D8") (pin "2") (pinfunction "A_2") (pintype "passive"))
      (node (ref "R28") (pin "1") (pinfunction "1_1") (pintype "passive"))
    )
    (net (code "85") (name "Net-(D17-A)") (class "Default")
      (node (ref "D17") (pin "2") (pinfunction "A_2") (pintype "passive"))
      (node (ref "R151") (pin "1") (pinfunction "1_1") (pintype "passive"))
    )
    (net (code "86") (name "Net-(D17-K)") (class "Default")
      (node (ref "D17") (pin "1+") (pinfunction "K_1+") (pintype "passive"))
      (node (ref "IC18") (pin "22") (pinfunction "GPIO0_22") (pintype "output"))
    )
    (net (code "87") (name "Net-(D19-A)") (class "Default")
      (node (ref "D19") (pin "2") (pinfunction "A_2") (pintype "passive"))
      (node (ref "R152") (pin "1") (pinfunction "1_1") (pintype "passive"))
    )
    (net (code "88") (name "Net-(D19-K)") (class "Default")
      (node (ref "D19") (pin "1+") (pinfunction "K_1+") (pintype "passive"))
      (node (ref "IC18") (pin "23") (pinfunction "GPIO1_23") (pintype "output"))
    )
    (net (code "89") (name "Net-(D23-A)") (class "Default")
      (node (ref "D23") (pin "2") (pinfunction "A_2") (pintype "passive"))
      (node (ref "R175") (pin "1") (pinfunction "1_1") (pintype "passive"))
    )
    (net (code "90") (name "Net-(D24-A)") (class "Default")
      (node (ref "D24") (pin "2") (pinfunction "A_2") (pintype "passive"))
      (node (ref "R176") (pin "1") (pinfunction "1_1") (pintype "passive"))
    )
    (net (code "91") (name "Net-(D29-K)") (class "Default")
      (node (ref "D29") (pin "C") (pinfunction "K_C") (pintype "passive"))
      (node (ref "L13") (pin "1") (pinfunction "1_1") (pintype "passive"))
      (node (ref "Q22") (pin "3") (pinfunction "D_3") (pintype "passive"))
    )
    (net (code "92") (name "Net-(F3-Pad1)") (class "Default")
      (node (ref "F3") (pin "1") (pinfunction "1_1") (pintype "passive"))
      (node (ref "J45") (pin "4") (pinfunction "4_4") (pintype "passive"))
    )
    (net (code "93") (name "Net-(IC3-AVDD)") (class "Default")
      (node (ref "C7") (pin "1") (pinfunction "1_1") (pintype "passive"))
      (node (ref "IC3") (pin "30") (pinfunction "AVDD_30") (pintype "power_in"))
      (node (ref "R1") (pin "1") (pinfunction "1_1") (pintype "passive"))
    )
    (net (code "94") (name "Net-(IC3-OSC1{slash}CLKI{slash}RC12)") (class "Default")
      (node (ref "C18") (pin "2") (pinfunction "2_2") (pintype "passive"))
      (node (ref "IC3") (pin "63") (pinfunction "OSC1/CLKI/RC12_63") (pintype "bidirectional"))
      (node (ref "Q4") (pin "3") (pinfunction "2_3") (pintype "passive"))
    )
    (net (code "95") (name "Net-(IC3-OSC2{slash}CLKO{slash}RC15)") (class "Default")
      (node (ref "C19") (pin "2") (pinfunction "2_2") (pintype "passive"))
      (node (ref "IC3") (pin "64") (pinfunction "OSC2/CLKO/RC15_64") (pintype "bidirectional"))
      (node (ref "Q4") (pin "1") (pinfunction "1_1") (pintype "passive"))
    )
    (net (code "96") (name "Net-(IC3-RA4{slash}TDI{slash}CN37)") (class "Default")
      (node (ref "IC3") (pin "60") (pinfunction "RA4/TDI/CN37_60") (pintype "bidirectional"))
      (node (ref "TP2") (pin "P$1") (pinfunction "TP_P$1") (pintype "passive"))
    )
    (net (code "97") (name "Net-(IC3-RB10{slash}AN10{slash}CN28{slash}CVREF)") (class "Default")
      (node (ref "IC3") (pin "34") (pinfunction "RB10/AN10/CN28/CVREF_34") (pintype "bidirectional"))
      (node (ref "TP3") (pin "P$1") (pinfunction "TP_P$1") (pintype "passive"))
    )
    (net (code "98") (name "Net-(IC3-VDDCORE)") (class "Default")
      (node (ref "C10") (pin "2") (pinfunction "2_2") (pintype "passive"))
      (node (ref "IC3") (pin "85") (pinfunction "VDDCORE_85") (pintype "passive"))
    )
    (net (code "99") (name "Net-(IC4-VDD)") (class "Default")
      (node (ref "C21") (pin "1") (pinfunction "1_1") (pintype "passive"))
      (node (ref "IC4") (pin "5") (pinfunction "VDD_5") (pintype "power_in"))
      (node (ref "J12") (pin "2") (pinfunction "2_2") (pintype "passive"))
      (node (ref "R15") (pin "1") (pinfunction "1_1") (pintype "passive"))
    )
    (net (code "100") (name "Net-(IC7-OSCI)") (class "Default")
      (node (ref "IC7") (pin "1") (pinfunction "OSCI_1") (pintype "input"))
      (node (ref "Q6") (pin "2") (pinfunction "2_2") (pintype "passive"))
    )
    (net (code "101") (name "Net-(IC7-OSCO)") (class "Default")
      (node (ref "IC7") (pin "2") (pinfunction "OSCO_2") (pintype "output"))
      (node (ref "Q6") (pin "1") (pinfunction "1_1") (pintype "passive"))
    )
    (net (code "102") (name "Net-(IC9-EN{slash}DIM)") (class "Default")
      (node (ref "C34") (pin "1") (pinfunction "1_1") (pintype "passive"))
      (node (ref "IC9") (pin "4") (pinfunction "EN/DIM_4") (pintype "input"))
      (node (ref "R23") (pin "2") (pinfunction "2_2") (pintype "passive"))
    )
    (net (code "103") (name "Net-(IC9-FB)") (class "Default")
      (node (ref "C31") (pin "2") (pinfunction "2_2") (pintype "passive"))
      (node (ref "IC9") (pin "3") (pinfunction "FB_3") (pintype "input"))
      (node (ref "J14") (pin "1") (pinfunction "1_1") (pintype "passive"))
      (node (ref "R25") (pin "2") (pinfunction "2_2") (pintype "passive"))
    )
    (net (code "104") (name "Net-(IC9-SW)") (class "Default")
      (node (ref "C30") (pin "2") (pinfunction "2_2") (pintype "passive"))
      (node (ref "D4") (pin "K") (pinfunction "K_K") (pintype "passive"))
      (node (ref "IC9") (pin "6") (pinfunction "SW_6") (pintype "output"))
      (node (ref "L3") (pin "1") (pinfunction "1_1") (pintype "passive"))
    )
    (net (code "105") (name "Net-(IC18-VCC30)") (class "Default")
      (node (ref "C121") (pin "2") (pinfunction "2_2") (pintype "passive"))
      (node (ref "IC18") (pin "17") (pinfunction "VCC30_17") (pintype "power_in"))
      (node (ref "IC18") (pin "4") (pinfunction "VCCIO_4") (pintype "power_in"))
      (node (ref "TP60") (pin "P$1") (pinfunction "TP_P$1") (pintype "passive"))
    )
    (net (code "106") (name "Net-(IC19A-+IN)") (class "Default")
      (node (ref "IC19") (pin "3") (pinfunction "+IN_3") (pintype "input"))
      (node (ref "Q14") (pin "3") (pinfunction "OUT_3") (pintype "output"))
    )
    (net (code "107") (name "Net-(IC19B-+IN)") (class "Default")
      (node (ref "IC19") (pin "5") (pinfunction "+IN_5") (pintype "input"))
      (node (ref "Q17") (pin "3") (pinfunction "OUT_3") (pintype "output"))
    )
    (net (code "108") (name "Net-(IC20-ITH)") (class "Default")
      (node (ref "IC20") (pin "2") (pinfunction "ITH_2") (pintype "input"))
      (node (ref "R191") (pin "2") (pinfunction "2_2") (pintype "passive"))
    )
    (net (code "109") (name "Net-(IC20-PGATE)") (class "Default")
      (node (ref "IC20") (pin "5") (pinfunction "PGATE_5") (pintype "output"))
      (node (ref "Q22") (pin "1") (pinfunction "G_1") (pintype "passive"))
    )
    (net (code "110") (name "Net-(IC20-RUN{slash}SS)") (class "Default")
      (node (ref "C161") (pin "1") (pinfunction "1_1") (pintype "passive"))
      (node (ref "IC20") (pin "1") (pinfunction "RUN/SS_1") (pintype "input"))
      (node (ref "TP68") (pin "1") (pinfunction "TP_1") (pintype "passive"))
    )
    (net (code "111") (name "Net-(IC20-SENSE)") (class "Default")
      (node (ref "C151") (pin "2") (pinfunction "2_2") (pintype "passive"))
      (node (ref "IC20") (pin "7") (pinfunction "SENSE_7") (pintype "input"))
      (node (ref "Q22") (pin "2") (pinfunction "S_2") (pintype "passive"))
      (node (ref "R188") (pin "1") (pinfunction "1_1") (pintype "passive"))
    )
    (net (code "112") (name "Net-(IC20-VFB)") (class "Default")
      (node (ref "C159") (pin "1") (pinfunction "1_1") (pintype "passive"))
      (node (ref "IC20") (pin "3") (pinfunction "VFB_3") (pintype "input"))
      (node (ref "R192") (pin "2") (pinfunction "2_2") (pintype "passive"))
      (node (ref "R196") (pin "1") (pinfunction "1_1") (pintype "passive"))
    )
    (net (code "113") (name "Net-(IC21-ITH)") (class "Default")
      (node (ref "IC21") (pin "2") (pinfunction "ITH_2") (pintype "input"))
      (node (ref "R193") (pin "2") (pinfunction "2_2") (pintype "passive"))
    )
    (net (code "114") (name "Net-(IC21-PGATE)") (class "Default")
      (node (ref "IC21") (pin "5") (pinfunction "PGATE_5") (pintype "output"))
      (node (ref "Q23") (pin "1") (pinfunction "G_1") (pintype "passive"))
    )
    (net (code "115") (name "Net-(IC21-SENSE)") (class "Default")
      (node (ref "C155") (pin "2") (pinfunction "2_2") (pintype "passive"))
      (node (ref "IC21") (pin "7") (pinfunction "SENSE_7") (pintype "input"))
      (node (ref "Q23") (pin "2") (pinfunction "S_2") (pintype "passive"))
      (node (ref "R189") (pin "1") (pinfunction "1_1") (pintype "passive"))
    )
    (net (code "116") (name "Net-(IC21-VFB)") (class "Default")
      (node (ref "C160") (pin "1") (pinfunction "1_1") (pintype "passive"))
      (node (ref "IC21") (pin "3") (pinfunction "VFB_3") (pintype "input"))
      (node (ref "R194") (pin "2") (pinfunction "2_2") (pintype "passive"))
      (node (ref "R197") (pin "1") (pinfunction "1_1") (pintype "passive"))
    )
    (net (code "117") (name "Net-(Q1A-D)") (class "Default")
      (node (ref "J4") (pin "3") (pinfunction "3_3") (pintype "passive"))
      (node (ref "Q1") (pin "6") (pinfunction "D_6") (pintype "passive"))
      (node (ref "Q1") (pin "P1") (pinfunction "D1_P1") (pintype "passive"))
    )
    (net (code "118") (name "Net-(Q2-Q2G)") (class "Default")
      (node (ref "Q2") (pin "6") (pinfunction "Q2G_6") (pintype "input"))
      (node (ref "R3") (pin "2") (pinfunction "2_2") (pintype "passive"))
    )
    (net (code "119") (name "Net-(Q5-Q2D1)") (class "Default")
      (node (ref "Q5") (pin "2") (pinfunction "Q2D1_2") (pintype "bidirectional"))
      (node (ref "Q5") (pin "3") (pinfunction "Q2D2_3") (pintype "bidirectional"))
      (node (ref "R18") (pin "1") (pinfunction "1_1") (pintype "passive"))
      (node (ref "R19") (pin "1") (pinfunction "1_1") (pintype "passive"))
    )
    (net (code "120") (name "Net-(Q5-Q2G)") (class "Default")
      (node (ref "Q5") (pin "6") (pinfunction "Q2G_6") (pintype "input"))
      (node (ref "R20") (pin "3") (pinfunction "1_3") (pintype "passive"))
    )
    (net (code "121") (name "Net-(Q14-VIN+)") (class "Default")
      (node (ref "Q14") (pin "5") (pinfunction "VIN+_5") (pintype "input"))
      (node (ref "Q15") (pin "5") (pinfunction "D_5") (pintype "passive"))
      (node (ref "Q15") (pin "6") (pinfunction "D1_6") (pintype "passive"))
      (node (ref "R154") (pin "1") (pinfunction "1_1") (pintype "passive"))
    )
    (net (code "122") (name "Net-(Q14-VIN-)") (class "Default")
      (node (ref "C122") (pin "1") (pinfunction "1_1") (pintype "passive"))
      (node (ref "C123") (pin "1") (pinfunction "1_1") (pintype "passive"))
      (node (ref "C125") (pin "1") (pinfunction "1_1") (pintype "passive"))
      (node (ref "Q14") (pin "4") (pinfunction "VIN-_4") (pintype "input"))
      (node (ref "R153") (pin "1") (pinfunction "1_1") (pintype "passive"))
      (node (ref "R154") (pin "2") (pinfunction "2_2") (pintype "passive"))
      (node (ref "R155") (pin "1") (pinfunction "1_1") (pintype "passive"))
      (node (ref "R157") (pin "2") (pinfunction "2_2") (pintype "passive"))
      (node (ref "U6") (pin "7") (pinfunction "VIN_7") (pintype "power_in"))
    )
    (net (code "123") (name "Net-(Q15A-D)") (class "Default")
      (node (ref "Q15") (pin "7") (pinfunction "D_7") (pintype "passive"))
      (node (ref "Q15") (pin "8") (pinfunction "D1_8") (pintype "passive"))
      (node (ref "R159") (pin "1") (pinfunction "1_1") (pintype "passive"))
    )
    (net (code "124") (name "Net-(Q15B-G)") (class "Default")
      (node (ref "Q15") (pin "4") (pinfunction "G_4") (pintype "passive"))
      (node (ref "R156") (pin "1") (pinfunction "1_1") (pintype "passive"))
      (node (ref "R159") (pin "2") (pinfunction "2_2") (pintype "passive"))
    )
    (net (code "125") (name "Net-(Q17-VIN+)") (class "Default")
      (node (ref "Q17") (pin "5") (pinfunction "VIN+_5") (pintype "input"))
      (node (ref "Q18") (pin "5") (pinfunction "D_5") (pintype "passive"))
      (node (ref "Q18") (pin "6") (pinfunction "D1_6") (pintype "passive"))
      (node (ref "R168") (pin "1") (pinfunction "1_1") (pintype "passive"))
    )
    (net (code "126") (name "Net-(Q17-VIN-)") (class "Default")
      (node (ref "C136") (pin "1") (pinfunction "1_1") (pintype "passive"))
      (node (ref "C137") (pin "1") (pinfunction "1_1") (pintype "passive"))
      (node (ref "C139") (pin "1") (pinfunction "1_1") (pintype "passive"))
      (node (ref "Q17") (pin "4") (pinfunction "VIN-_4") (pintype "input"))
      (node (ref "R168") (pin "2") (pinfunction "2_2") (pintype "passive"))
      (node (ref "R169") (pin "1") (pinfunction "1_1") (pintype "passive"))
      (node (ref "R171") (pin "2") (pinfunction "2_2") (pintype "passive"))
      (node (ref "U7") (pin "7") (pinfunction "VIN_7") (pintype "power_in"))
    )
    (net (code "127") (name "Net-(Q18A-D)") (class "Default")
      (node (ref "Q18") (pin "7") (pinfunction "D_7") (pintype "passive"))
      (node (ref "Q18") (pin "8") (pinfunction "D1_8") (pintype "passive"))
      (node (ref "R173") (pin "2") (pinfunction "2_2") (pintype "passive"))
    )
    (net (code "128") (name "Net-(Q18B-G)") (class "Default")
      (node (ref "Q18") (pin "4") (pinfunction "G_4") (pintype "passive"))
      (node (ref "R170") (pin "2") (pinfunction "2_2") (pintype "passive"))
      (node (ref "R173") (pin "1") (pinfunction "1_1") (pintype "passive"))
    )
    (net (code "129") (name "Net-(Q23-D)") (class "Default")
      (node (ref "D30") (pin "K") (pinfunction "K_K") (pintype "passive"))
      (node (ref "L14") (pin "1") (pinfunction "1_1") (pintype "passive"))
      (node (ref "Q23") (pin "3") (pinfunction "D_3") (pintype "passive"))
    )
    (net (code "130") (name "Net-(Q24-D)") (class "Default")
      (node (ref "Q24") (pin "3") (pinfunction "D_3") (pintype "passive"))
      (node (ref "R208") (pin "2") (pinfunction "2_2") (pintype "passive"))
    )
    (net (code "131") (name "Net-(R199-Pad1)") (class "Default")
      (node (ref "R199") (pin "1") (pinfunction "1_1") (pintype "passive"))
      (node (ref "U8") (pin "14") (pinfunction "AVCC_14") (pintype "power_in"))
    )
    (net (code "132") (name "Net-(TP69-TP)") (class "Default")
      (node (ref "R204") (pin "2") (pinfunction "2_2") (pintype "passive"))
      (node (ref "TP69") (pin "1") (pinfunction "TP_1") (pintype "passive"))
    )
    (net (code "133") (name "Net-(U1--UNDERV)") (class "Default")
      (node (ref "R12") (pin "1") (pinfunction "1_1") (pintype "passive"))
      (node (ref "U1") (pin "23") (pinfunction "-UNDERV_23") (pintype "bidirectional"))
    )
    (net (code "134") (name "Net-(U1-C+)") (class "Default")
      (node (ref "C15") (pin "2") (pinfunction "2_2") (pintype "passive"))
      (node (ref "U1") (pin "14") (pinfunction "C+_14") (pintype "bidirectional"))
    )
    (net (code "135") (name "Net-(U1-C-)") (class "Default")
      (node (ref "C15") (pin "1") (pinfunction "1_1") (pintype "passive"))
      (node (ref "U1") (pin "11") (pinfunction "C-_11") (pintype "bidirectional"))
    )
    (net (code "136") (name "Net-(U1-CLKB)") (class "Default")
      (node (ref "J10") (pin "C3") (pinfunction "C3_C3") (pintype "bidirectional"))
      (node (ref "U1") (pin "18") (pinfunction "CLKB_18") (pintype "bidirectional"))
    )
    (net (code "137") (name "Net-(U1-CPO)") (class "Default")
      (node (ref "C20") (pin "2") (pinfunction "2_2") (pintype "passive"))
      (node (ref "U1") (pin "15") (pinfunction "CPO_15") (pintype "bidirectional"))
    )
    (net (code "138") (name "Net-(U1-NC{slash}-NO)") (class "Default")
      (node (ref "R13") (pin "2") (pinfunction "2_2") (pintype "passive"))
      (node (ref "U1") (pin "22") (pinfunction "NC/-NO_22") (pintype "bidirectional"))
    )
    (net (code "139") (name "Net-(U1-RSTB)") (class "Default")
      (node (ref "J10") (pin "C2") (pinfunction "C2_C2") (pintype "bidirectional"))
      (node (ref "U1") (pin "19") (pinfunction "RSTB_19") (pintype "bidirectional"))
    )
    (net (code "140") (name "Net-(U1-VCCB)") (class "Default")
      (node (ref "J10") (pin "C1") (pinfunction "C1_C1") (pintype "bidirectional"))
      (node (ref "U1") (pin "17") (pinfunction "VCCB_17") (pintype "bidirectional"))
    )
    (net (code "141") (name "Net-(U2-EN)") (class "Default")
      (node (ref "R26") (pin "1") (pinfunction "1_1") (pintype "passive"))
      (node (ref "U2") (pin "4") (pinfunction "EN_4") (pintype "bidirectional"))
    )
    (net (code "142") (name "Net-(U3-AIN0)") (class "Default")
      (node (ref "R33") (pin "1") (pinfunction "1_1") (pintype "passive"))
      (node (ref "R34") (pin "2") (pinfunction "2_2") (pintype "passive"))
      (node (ref "U3") (pin "4") (pinfunction "AIN0_4") (pintype "bidirectional"))
    )
    (net (code "143") (name "Net-(U3-AIN2)") (class "Default")
      (node (ref "R35") (pin "1") (pinfunction "1_1") (pintype "passive"))
      (node (ref "R36") (pin "2") (pinfunction "2_2") (pintype "passive"))
      (node (ref "U3") (pin "6") (pinfunction "AIN2_6") (pintype "bidirectional"))
    )
    (net (code "144") (name "Net-(U9--IN)") (class "Default")
      (node (ref "C185") (pin "1") (pinfunction "1_1") (pintype "passive"))
      (node (ref "C186") (pin "1") (pinfunction "1_1") (pintype "passive"))
      (node (ref "R209") (pin "2") (pinfunction "2_2") (pintype "passive"))
      (node (ref "U9") (pin "4") (pinfunction "-IN_4") (pintype "input"))
    )
    (net (code "145") (name "Net-(U9-OUT)") (class "Default")
      (node (ref "C183") (pin "1") (pinfunction "1_1") (pintype "passive"))
      (node (ref "C184") (pin "1") (pinfunction "1_1") (pintype "passive"))
      (node (ref "C186") (pin "2") (pinfunction "2_2") (pintype "passive"))
      (node (ref "R209") (pin "1") (pinfunction "1_1") (pintype "passive"))
      (node (ref "U9") (pin "1") (pinfunction "OUT_1") (pintype "output"))
    )
    (net (code "146") (name "OUTN_UNF") (class "Default")
      (node (ref "C178") (pin "2") (pinfunction "2_2") (pintype "passive"))
      (node (ref "L16") (pin "2") (pinfunction "2_2") (pintype "passive"))
      (node (ref "U8") (pin "23") (pinfunction "OUTN_23") (pintype "output"))
      (node (ref "U8") (pin "25") (pinfunction "OUTN_25") (pintype "output"))
    )
    (net (code "147") (name "OUTP_UNF") (class "Default")
      (node (ref "C173") (pin "2") (pinfunction "2_2") (pintype "passive"))
      (node (ref "L15") (pin "2") (pinfunction "2_2") (pintype "passive"))
      (node (ref "U8") (pin "18") (pinfunction "OUTP_18") (pintype "output"))
      (node (ref "U8") (pin "20") (pinfunction "OUTP_20") (pintype "output"))
    )
    (net (code "148") (name "OUT_S1") (class "Default")
      (node (ref "D23") (pin "1+") (pinfunction "K_1+") (pintype "passive"))
      (node (ref "D25") (pin "C") (pinfunction "K_C") (pintype "passive"))
      (node (ref "J43") (pin "2") (pinfunction "2_2") (pintype "passive"))
      (node (ref "J44") (pin "2") (pinfunction "2_2") (pintype "passive"))
      (node (ref "Q20") (pin "3") (pinfunction "D_3") (pintype "passive"))
    )
    (net (code "149") (name "OUT_S2") (class "Default")
      (node (ref "D24") (pin "1+") (pinfunction "K_1+") (pintype "passive"))
      (node (ref "D26") (pin "C") (pinfunction "K_C") (pintype "passive"))
      (node (ref "J43") (pin "3") (pinfunction "3_3") (pintype "passive"))
      (node (ref "J44") (pin "3") (pinfunction "3_3") (pintype "passive"))
      (node (ref "Q21") (pin "3") (pinfunction "D_3") (pintype "passive"))
    )
    (net (code "150") (name "OUT_S3") (class "Default")
      (node (ref "D5") (pin "C") (pinfunction "K_C") (pintype "passive"))
      (node (ref "D7") (pin "1+") (pinfunction "K_1+") (pintype "passive"))
      (node (ref "J15") (pin "2") (pinfunction "2_2") (pintype "passive"))
      (node (ref "J16") (pin "2") (pinfunction "2_2") (pintype "passive"))
      (node (ref "Q8") (pin "3") (pinfunction "D_3") (pintype "passive"))
    )
    (net (code "151") (name "OUT_S4") (class "Default")
      (node (ref "D6") (pin "C") (pinfunction "K_C") (pintype "passive"))
      (node (ref "D8") (pin "1+") (pinfunction "K_1+") (pintype "passive"))
      (node (ref "J15") (pin "3") (pinfunction "3_3") (pintype "passive"))
      (node (ref "J16") (pin "3") (pinfunction "3_3") (pintype "passive"))
      (node (ref "Q9") (pin "3") (pinfunction "D_3") (pintype "passive"))
    )
    (net (code "152") (name "P12V") (class "Default")
      (node (ref "C128") (pin "1") (pinfunction "1_1") (pintype "passive"))
      (node (ref "C129") (pin "1") (pinfunction "1_1") (pintype "passive"))
      (node (ref "C130") (pin "1") (pinfunction "1_1") (pintype "passive"))
      (node (ref "C165") (pin "1") (pinfunction "1_1") (pintype "passive"))
      (node (ref "C166") (pin "1") (pinfunction "1_1") (pintype "passive"))
      (node (ref "C167") (pin "1") (pinfunction "1_1") (pintype "passive"))
      (node (ref "C168") (pin "1") (pinfunction "1_1") (pintype "passive"))
      (node (ref "C169") (pin "1") (pinfunction "1_1") (pintype "passive"))
      (node (ref "C170") (pin "1") (pinfunction "1_1") (pintype "passive"))
      (node (ref "D20") (pin "K") (pinfunction "K_K") (pintype "passive"))
      (node (ref "J50") (pin "2") (pinfunction "2_2") (pintype "passive"))
      (node (ref "Q16") (pin "1_2") (pinfunction "VIN_1_2") (pintype "passive"))
      (node (ref "R160") (pin "2") (pinfunction "2_2") (pintype "passive"))
      (node (ref "R198") (pin "2") (pinfunction "2_2") (pintype "passive"))
      (node (ref "TP61") (pin "1") (pinfunction "TP_1") (pintype "passive"))
      (node (ref "U8") (pin "15") (pinfunction "PVCC_15") (pintype "power_in"))
      (node (ref "U8") (pin "16") (pinfunction "PVCC_16") (pintype "power_in"))
      (node (ref "U8") (pin "27") (pinfunction "PVCC_27") (pintype "power_in"))
      (node (ref "U8") (pin "28") (pinfunction "PVCC_28") (pintype "power_in"))
    )
    (net (code "153") (name "PGC") (class "Default")
      (node (ref "IC3") (pin "26") (pinfunction "RB6/AN6/PGC2/RP6_26") (pintype "bidirectional"))
      (node (ref "J11") (pin "5") (pinfunction "5_5") (pintype "passive"))
    )
    (net (code "154") (name "PGD") (class "Default")
      (node (ref "IC3") (pin "27") (pinfunction "RB7/AN7/PGD2/RP7_27") (pintype "bidirectional"))
      (node (ref "J11") (pin "4") (pinfunction "4_4") (pintype "passive"))
    )
    (net (code "155") (name "PHOTOCELL") (class "Default")
      (node (ref "J3") (pin "5") (pinfunction "5_5") (pintype "passive"))
      (node (ref "R7") (pin "2") (pinfunction "2_2") (pintype "passive"))
      (node (ref "R8") (pin "2") (pinfunction "2_2") (pintype "passive"))
    )
    (net (code "156") (name "PHOTO_PIN") (class "Default")
      (node (ref "IC3") (pin "24") (pinfunction "RB1/AN1/CN3/PGC1/RP1_24") (pintype "bidirectional"))
      (node (ref "R8") (pin "1") (pinfunction "1_1") (pintype "passive"))
    )
    (net (code "157") (name "PHOTO_PWR") (class "Default")
      (node (ref "IC3") (pin "25") (pinfunction "RB0/AN0/CN2/PGD1/RP0_25") (pintype "bidirectional"))
      (node (ref "R7") (pin "1") (pinfunction "1_1") (pintype "passive"))
    )
    (net (code "158") (name "PIC_INT") (class "Default")
      (node (ref "IC3") (pin "38") (pinfunction "RA1/TCK_38") (pintype "bidirectional"))
      (node (ref "J1") (pin "3") (pinfunction "3_3") (pintype "passive"))
      (node (ref "J3") (pin "7") (pinfunction "7_7") (pintype "passive"))
    )
    (net (code "159") (name "RTC_CS") (class "Default")
      (node (ref "IC3") (pin "79") (pinfunction "CN57/RPI42/RD12_79") (pintype "bidirectional"))
      (node (ref "IC7") (pin "6") (pinfunction "CE_6") (pintype "input"))
      (node (ref "R22") (pin "2") (pinfunction "2_2") (pintype "passive"))
    )
    (net (code "160") (name "RTC_INT") (class "Default")
      (node (ref "IC3") (pin "80") (pinfunction "CN19/RD13_80") (pintype "bidirectional"))
      (node (ref "IC7") (pin "5") (pinfunction "/INT_5") (pintype "output"))
    )
    (net (code "161") (name "SBC_5V_VBUS") (class "Default")
      (node (ref "C114") (pin "2") (pinfunction "2_2") (pintype "passive"))
      (node (ref "C115") (pin "2") (pinfunction "2_2") (pintype "passive"))
      (node (ref "IC18") (pin "19") (pinfunction "/RESET_19") (pintype "bidirectional"))
      (node (ref "IC18") (pin "20") (pinfunction "VCC5I_20") (pintype "power_in"))
      (node (ref "J40") (pin "1") (pinfunction "1_1") (pintype "bidirectional"))
      (node (ref "J41") (pin "3") (pinfunction "3_3") (pintype "passive"))
      (node (ref "R151") (pin "2") (pinfunction "2_2") (pintype "passive"))
      (node (ref "R152") (pin "2") (pinfunction "2_2") (pintype "passive"))
    )
    (net (code "162") (name "SBC_LINL") (class "Default")
      (node (ref "C184") (pin "2") (pinfunction "2_2") (pintype "passive"))
      (node (ref "J47") (pin "6") (pinfunction "6_6") (pintype "passive"))
    )
    (net (code "163") (name "SBC_LINR") (class "Default")
      (node (ref "C183") (pin "2") (pinfunction "2_2") (pintype "passive"))
      (node (ref "J47") (pin "2") (pinfunction "2_2") (pintype "passive"))
    )
    (net (code "164") (name "SBC_LOUTL") (class "Default")
      (node (ref "C175") (pin "1") (pinfunction "1_1") (pintype "passive"))
      (node (ref "J47") (pin "5") (pinfunction "5_5") (pintype "passive"))
    )
    (net (code "165") (name "SBC_LOUTR") (class "Default")
      (node (ref "C174") (pin "1") (pinfunction "1_1") (pintype "passive"))
      (node (ref "J47") (pin "1") (pinfunction "1_1") (pintype "passive"))
    )
    (net (code "166") (name "SBC_USB_B_D_N") (class "Default")
      (node (ref "IC18") (pin "16") (pinfunction "USBDM_16") (pintype "bidirectional"))
      (node (ref "J40") (pin "2") (pinfunction "2_2") (pintype "bidirectional"))
    )
    (net (code "167") (name "SBC_USB_B_D_P") (class "Default")
      (node (ref "IC18") (pin "15") (pinfunction "USBDP_15") (pintype "bidirectional"))
      (node (ref "J40") (pin "3") (pinfunction "3_3") (pintype "bidirectional"))
    )
    (net (code "168") (name "SCL1") (class "Default")
      (node (ref "IC3") (pin "57") (pinfunction "RG2/SCL1/CN83_57") (pintype "bidirectional"))
      (node (ref "IC5") (pin "2") (pinfunction "SCL_2") (pintype "input"))
      (node (ref "IC6") (pin "6") (pinfunction "SCL_6") (pintype "input"))
      (node (ref "J8") (pin "16") (pinfunction "16_16") (pintype "passive"))
      (node (ref "R16") (pin "1") (pinfunction "1_1") (pintype "passive"))
      (node (ref "R32") (pin "1") (pinfunction "1_1") (pintype "passive"))
      (node (ref "U3") (pin "1") (pinfunction "ADDR_1") (pintype "bidirectional"))
      (node (ref "U3") (pin "10") (pinfunction "SCL_10") (pintype "bidirectional"))
    )
    (net (code "169") (name "SCLK1") (class "Default")
      (node (ref "IC3") (pin "77") (pinfunction "CN51/RP23/RD2_77") (pintype "bidirectional"))
      (node (ref "IC7") (pin "10") (pinfunction "SCL_10") (pintype "input"))
      (node (ref "IC8") (pin "6") (pinfunction "C_6") (pintype "input"))
    )
    (net (code "170") (name "SCLK2") (class "Default")
      (node (ref "IC3") (pin "10") (pinfunction "RG6/CN8/RP21_10") (pintype "bidirectional"))
      (node (ref "J1") (pin "5") (pinfunction "5_5") (pintype "passive"))
      (node (ref "J3") (pin "15") (pinfunction "15_15") (pintype "passive"))
      (node (ref "J8") (pin "12") (pinfunction "12_12") (pintype "passive"))
      (node (ref "U1") (pin "31") (pinfunction "ASYNC_31") (pintype "bidirectional"))
    )
    (net (code "171") (name "SCLK_SM_B") (class "Default")
      (node (ref "IC3") (pin "8") (pinfunction "RC3/CN47/RPI40_8") (pintype "bidirectional"))
      (node (ref "U1") (pin "26") (pinfunction "SCLK_26") (pintype "bidirectional"))
    )
    (net (code "172") (name "SDA1") (class "Default")
      (node (ref "IC3") (pin "56") (pinfunction "RG3/SDA1/CN84_56") (pintype "bidirectional"))
      (node (ref "IC5") (pin "1") (pinfunction "SDA_1") (pintype "bidirectional"))
      (node (ref "IC6") (pin "5") (pinfunction "SDA_5") (pintype "bidirectional"))
      (node (ref "J8") (pin "15") (pinfunction "15_15") (pintype "passive"))
      (node (ref "R17") (pin "1") (pinfunction "1_1") (pintype "passive"))
      (node (ref "R31") (pin "1") (pinfunction "1_1") (pintype "passive"))
      (node (ref "U3") (pin "9") (pinfunction "SDA_9") (pintype "bidirectional"))
    )
    (net (code "173") (name "SDI1") (class "Default")
      (node (ref "IC3") (pin "72") (pinfunction "CN49/RP11/RD0_72") (pintype "bidirectional"))
      (node (ref "IC7") (pin "8") (pinfunction "SDO_8") (pintype "output"))
      (node (ref "IC8") (pin "2") (pinfunction "Q_2") (pintype "bidirectional"))
    )
    (net (code "174") (name "SDI2") (class "Default")
      (node (ref "IC3") (pin "11") (pinfunction "RG7/CN9/RP26_11") (pintype "bidirectional"))
      (node (ref "J1") (pin "8") (pinfunction "8_8") (pintype "passive"))
      (node (ref "J3") (pin "21") (pinfunction "21_21") (pintype "passive"))
      (node (ref "J8") (pin "11") (pinfunction "11_11") (pintype "passive"))
    )
    (net (code "175") (name "SDO1") (class "Default")
      (node (ref "IC3") (pin "76") (pinfunction "CN50/RP24/RD1_76") (pintype "bidirectional"))
      (node (ref "IC7") (pin "9") (pinfunction "SDI_9") (pintype "input"))
      (node (ref "IC8") (pin "5") (pinfunction "D_5") (pintype "input"))
    )
    (net (code "176") (name "SDO2") (class "Default")
      (node (ref "IC3") (pin "12") (pinfunction "CN10/RP19/RG8_12") (pintype "bidirectional"))
      (node (ref "J1") (pin "6") (pinfunction "6_6") (pintype "passive"))
      (node (ref "J3") (pin "17") (pinfunction "17_17") (pintype "passive"))
      (node (ref "J8") (pin "14") (pinfunction "14_14") (pintype "passive"))
    )
    (net (code "177") (name "SMB_SCL") (class "Default")
      (node (ref "D31") (pin "6") (pinfunction "AK_6") (pintype "passive"))
      (node (ref "IC3") (pin "66") (pinfunction "RA14/RPI36/CN43_66") (pintype "bidirectional"))
      (node (ref "J45") (pin "2") (pinfunction "2_2") (pintype "passive"))
      (node (ref "R190") (pin "1") (pinfunction "1_1") (pintype "passive"))
    )
    (net (code "178") (name "SMB_SDA") (class "Default")
      (node (ref "D31") (pin "3") (pinfunction "AK_3") (pintype "passive"))
      (node (ref "IC3") (pin "67") (pinfunction "RA15/RPI35/CN44_67") (pintype "bidirectional"))
      (node (ref "J45") (pin "3") (pinfunction "3_3") (pintype "passive"))
      (node (ref "R187") (pin "1") (pinfunction "1_1") (pintype "passive"))
    )
    (net (code "179") (name "SM_C4A") (class "Default")
      (node (ref "U1") (pin "4") (pinfunction "C4A_4") (pintype "bidirectional"))
      (node (ref "X1") (pin "2") (pinfunction "1_2") (pintype "passive"))
    )
    (net (code "180") (name "SM_C8A") (class "Default")
      (node (ref "U1") (pin "3") (pinfunction "C8A_3") (pintype "bidirectional"))
      (node (ref "X1") (pin "1") (pinfunction "1_1") (pintype "passive"))
    )
    (net (code "181") (name "SM_CLK_A") (class "Default")
      (node (ref "U1") (pin "7") (pinfunction "CLKA_7") (pintype "bidirectional"))
      (node (ref "X1") (pin "4") (pinfunction "1_4") (pintype "passive"))
    )
    (net (code "182") (name "SM_DATA") (class "Default")
      (node (ref "IC3") (pin "14") (pinfunction "CN11/RP27/RG9_14") (pintype "bidirectional"))
      (node (ref "U1") (pin "29") (pinfunction "DATA_29") (pintype "bidirectional"))
    )
    (net (code "183") (name "SM_DET_A") (class "Default")
      (node (ref "U1") (pin "2") (pinfunction "PRESA_2") (pintype "bidirectional"))
      (node (ref "X1") (pin "10") (pinfunction "1_10") (pintype "passive"))
    )
    (net (code "184") (name "SM_IO_A") (class "Default")
      (node (ref "U1") (pin "5") (pinfunction "IOA_5") (pintype "bidirectional"))
      (node (ref "X1") (pin "3") (pinfunction "1_3") (pintype "passive"))
    )
    (net (code "185") (name "SM_RST") (class "Default")
      (node (ref "IC3") (pin "5") (pinfunction "CN65/SDA3/RE7_5") (pintype "bidirectional"))
      (node (ref "U1") (pin "30") (pinfunction "RIN_30") (pintype "bidirectional"))
    )
    (net (code "186") (name "SM_RST_A") (class "Default")
      (node (ref "U1") (pin "6") (pinfunction "RSTA_6") (pintype "bidirectional"))
      (node (ref "X1") (pin "6") (pinfunction "1_6") (pintype "passive"))
    )
    (net (code "187") (name "SM_SYNC") (class "Default")
      (node (ref "IC3") (pin "4") (pinfunction "CN64/SCL3/RE6_4") (pintype "bidirectional"))
      (node (ref "U1") (pin "32") (pinfunction "SYNC_32") (pintype "bidirectional"))
    )
    (net (code "188") (name "SM_VCC_A") (class "Default")
      (node (ref "U1") (pin "8") (pinfunction "VCCA_8") (pintype "bidirectional"))
      (node (ref "X1") (pin "9") (pinfunction "1_9") (pintype "passive"))
    )
    (net (code "189") (name "SNDR") (class "Default")
      (node (ref "IC3") (pin "35") (pinfunction "RB11/AN11/CN29_35") (pintype "bidirectional"))
    )
    (net (code "190") (name "SPKR1_P") (class "Default")
      (node (ref "C176") (pin "1") (pinfunction "1_1") (pintype "passive"))
      (node (ref "J46") (pin "2") (pinfunction "2_2") (pintype "passive"))
      (node (ref "L15") (pin "1") (pinfunction "1_1") (pintype "passive"))
    )
    (net (code "191") (name "SPKR_N") (class "Default")
      (node (ref "C179") (pin "1") (pinfunction "1_1") (pintype "passive"))
      (node (ref "J46") (pin "4") (pinfunction "4_4") (pintype "passive"))
      (node (ref "L16") (pin "1") (pinfunction "1_1") (pintype "passive"))
    )
    (net (code "192") (name "STRIKE_EN") (class "Default")
      (node (ref "IC3") (pin "47") (pinfunction "CN20/RPI43/RD14_47") (pintype "bidirectional"))
      (node (ref "Q18") (pin "2") (pinfunction "G_2") (pintype "passive"))
      (node (ref "R174") (pin "1") (pinfunction "1_1") (pintype "passive"))
      (node (ref "R179") (pin "2") (pinfunction "2_2") (pintype "passive"))
      (node (ref "U7") (pin "15") (pinfunction "EN_15") (pintype "input"))
    )
    (net (code "193") (name "STR_BOOT") (class "Default")
      (node (ref "C140") (pin "1") (pinfunction "1_1") (pintype "passive"))
      (node (ref "U7") (pin "11") (pinfunction "BOOT_11") (pintype "passive"))
    )
    (net (code "194") (name "STR_COMP") (class "Default")
      (node (ref "C146") (pin "1") (pinfunction "1_1") (pintype "passive"))
      (node (ref "R181") (pin "2") (pinfunction "2_2") (pintype "passive"))
      (node (ref "U7") (pin "3") (pinfunction "COMP_3") (pintype "passive"))
    )
    (net (code "195") (name "STR_FB") (class "Default")
      (node (ref "R177") (pin "1") (pinfunction "1_1") (pintype "passive"))
      (node (ref "R185") (pin "2") (pinfunction "2_2") (pintype "passive"))
      (node (ref "U7") (pin "4") (pinfunction "FB_4") (pintype "input"))
    )
    (net (code "196") (name "STR_FEED") (class "Default")
      (node (ref "L12") (pin "2") (pinfunction "2_2") (pintype "passive"))
      (node (ref "R169") (pin "2") (pinfunction "2_2") (pintype "passive"))
      (node (ref "R172") (pin "2") (pinfunction "2_2") (pintype "passive"))
    )
    (net (code "197") (name "STR_HDRV") (class "Default")
      (node (ref "R178") (pin "2") (pinfunction "2_2") (pintype "passive"))
      (node (ref "U7") (pin "13") (pinfunction "HDRV_13") (pintype "output"))
    )
    (net (code "198") (name "STR_HG1") (class "Default")
      (node (ref "Q19") (pin "3") (pinfunction "TG_3") (pintype "passive"))
      (node (ref "R178") (pin "1") (pinfunction "1_1") (pintype "passive"))
    )
    (net (code "199") (name "STR_ISNS+") (class "Default")
      (node (ref "C138") (pin "1") (pinfunction "1_1") (pintype "passive"))
      (node (ref "R171") (pin "1") (pinfunction "1_1") (pintype "passive"))
      (node (ref "U7") (pin "6") (pinfunction "ISNS+_6") (pintype "input"))
    )
    (net (code "200") (name "STR_ISNS-") (class "Default")
      (node (ref "C138") (pin "2") (pinfunction "2_2") (pintype "passive"))
      (node (ref "R172") (pin "1") (pinfunction "1_1") (pintype "passive"))
      (node (ref "U7") (pin "5") (pinfunction "ISNS-_5") (pintype "input"))
    )
    (net (code "201") (name "STR_L") (class "Default")
      (node (ref "D22") (pin "A") (pinfunction "A_A") (pintype "passive"))
      (node (ref "L12") (pin "1") (pinfunction "1_1") (pintype "passive"))
      (node (ref "Q19") (pin "6") (pinfunction "VSW_6") (pintype "passive"))
      (node (ref "Q19") (pin "7") (pinfunction "VSW_7") (pintype "passive"))
      (node (ref "Q19") (pin "8") (pinfunction "VSW_8") (pintype "passive"))
    )
    (net (code "202") (name "STR_LDRV") (class "Default")
      (node (ref "R180") (pin "2") (pinfunction "2_2") (pintype "passive"))
      (node (ref "U7") (pin "8") (pinfunction "LDRV_8") (pintype "output"))
    )
    (net (code "203") (name "STR_LG1") (class "Default")
      (node (ref "Q19") (pin "5") (pinfunction "BG_5") (pintype "passive"))
      (node (ref "R180") (pin "1") (pinfunction "1_1") (pintype "passive"))
    )
    (net (code "204") (name "STR_PG") (class "Default")
      (node (ref "IC3") (pin "74") (pinfunction "RC14/SOSCO/CN0/RPI37_74") (pintype "bidirectional"))
      (node (ref "R186") (pin "1") (pinfunction "1_1") (pintype "passive"))
      (node (ref "U7") (pin "14") (pinfunction "PGOOD_14") (pintype "open_collector"))
    )
    (net (code "205") (name "STR_RC") (class "Default")
      (node (ref "C148") (pin "1") (pinfunction "1_1") (pintype "passive"))
      (node (ref "R181") (pin "1") (pinfunction "1_1") (pintype "passive"))
    )
    (net (code "206") (name "STR_RT") (class "Default")
      (node (ref "R182") (pin "2") (pinfunction "2_2") (pintype "passive"))
      (node (ref "U7") (pin "1") (pinfunction "RT/CLK_1") (pintype "passive"))
    )
    (net (code "207") (name "STR_SS") (class "Default")
      (node (ref "C147") (pin "1") (pinfunction "1_1") (pintype "passive"))
      (node (ref "U7") (pin "2") (pinfunction "SS_2") (pintype "passive"))
    )
    (net (code "208") (name "STR_SW") (class "Default")
      (node (ref "C140") (pin "2") (pinfunction "2_2") (pintype "passive"))
      (node (ref "Q19") (pin "4") (pinfunction "TGR_4") (pintype "passive"))
      (node (ref "U7") (pin "12") (pinfunction "SW_12") (pintype "output"))
    )
    (net (code "209") (name "STR_VCC") (class "Default")
      (node (ref "C141") (pin "1") (pinfunction "1_1") (pintype "passive"))
      (node (ref "U7") (pin "10") (pinfunction "VCC_10") (pintype "output"))
    )
    (net (code "210") (name "U1RX") (class "Default")
      (node (ref "IC18") (pin "1") (pinfunction "TXD_1") (pintype "output"))
      (node (ref "IC3") (pin "70") (pinfunction "CN55/RP3/RD10_70") (pintype "bidirectional"))
      (node (ref "J41") (pin "4") (pinfunction "4_4") (pintype "passive"))
    )
    (net (code "211") (name "U1TX") (class "Default")
      (node (ref "IC18") (pin "5") (pinfunction "RXD_5") (pintype "input"))
      (node (ref "IC3") (pin "71") (pinfunction "CN56/RP12/RD11_71") (pintype "bidirectional"))
      (node (ref "J41") (pin "5") (pinfunction "5_5") (pintype "passive"))
    )
    (net (code "212") (name "U2CTL") (class "Default")
      (node (ref "IC2") (pin "2") (pinfunction "/RE_2") (pintype "input"))
      (node (ref "IC2") (pin "3") (pinfunction "DE_3") (pintype "input"))
      (node (ref "IC3") (pin "19") (pinfunction "RPI34/CN67/RE9_19") (pintype "bidirectional"))
      (node (ref "J3") (pin "26") (pinfunction "26_26") (pintype "passive"))
      (node (ref "J8") (pin "6") (pinfunction "6_6") (pintype "passive"))
    )
    (net (code "213") (name "U2RX") (class "Default")
      (node (ref "IC2") (pin "1") (pinfunction "R_1") (pintype "output"))
      (node (ref "IC3") (pin "81") (pinfunction "CN13/RP25/RD4_81") (pintype "bidirectional"))
      (node (ref "J8") (pin "4") (pinfunction "4_4") (pintype "passive"))
    )
    (net (code "214") (name "U2TX") (class "Default")
      (node (ref "IC2") (pin "4") (pinfunction "D_4") (pintype "input"))
      (node (ref "IC3") (pin "82") (pinfunction "CN14/RP20/RD5_82") (pintype "bidirectional"))
      (node (ref "J8") (pin "2") (pinfunction "2_2") (pintype "passive"))
    )
    (net (code "215") (name "U3RX") (class "Default")
      (node (ref "IC3") (pin "23") (pinfunction "RB2/AN2/CN4/RP13_23") (pintype "bidirectional"))
      (node (ref "J2") (pin "3") (pinfunction "3_3") (pintype "passive"))
    )
    (net (code "216") (name "U3TX") (class "Default")
      (node (ref "IC3") (pin "33") (pinfunction "RB9/AN9/CN27/RP9_33") (pintype "bidirectional"))
      (node (ref "J2") (pin "4") (pinfunction "4_4") (pintype "passive"))
    )
    (net (code "217") (name "US-S_O") (class "Default")
      (node (ref "IC3") (pin "78") (pinfunction "CN52/RP22/RD3_78") (pintype "bidirectional"))
      (node (ref "U2") (pin "5") (pinfunction "SERIAL_5") (pintype "bidirectional"))
    )
    (net (code "218") (name "VACT") (class "Default")
      (node (ref "C142") (pin "1") (pinfunction "1_1") (pintype "passive"))
      (node (ref "C143") (pin "1") (pinfunction "1_1") (pintype "passive"))
      (node (ref "C144") (pin "1") (pinfunction "1_1") (pintype "passive"))
      (node (ref "C145") (pin "1") (pinfunction "1_1") (pintype "passive"))
      (node (ref "C36") (pin "1") (pinfunction "1_1") (pintype "passive"))
      (node (ref "D21") (pin "+") (pinfunction "C_+") (pintype "passive"))
      (node (ref "D22") (pin "K") (pinfunction "K_K") (pintype "passive"))
      (node (ref "D9") (pin "+") (pinfunction "C_+") (pintype "passive"))
      (node (ref "J15") (pin "4") (pinfunction "4_4") (pintype "passive"))
      (node (ref "J16") (pin "4") (pinfunction "4_4") (pintype "passive"))
      (node (ref "J43") (pin "4") (pinfunction "4_4") (pintype "passive"))
      (node (ref "J44") (pin "4") (pinfunction "4_4") (pintype "passive"))
      (node (ref "Q19") (pin "1_2") (pinfunction "VIN_1_2") (pintype "passive"))
      (node (ref "R175") (pin "2") (pinfunction "2_2") (pintype "passive"))
      (node (ref "R176") (pin "2") (pinfunction "2_2") (pintype "passive"))
      (node (ref "R177") (pin "2") (pinfunction "2_2") (pintype "passive"))
      (node (ref "R27") (pin "2") (pinfunction "2_2") (pintype "passive"))
      (node (ref "R28") (pin "2") (pinfunction "2_2") (pintype "passive"))
      (node (ref "TP62") (pin "1") (pinfunction "TP_1") (pintype "passive"))
    )
    (net (code "219") (name "VPS_ON") (class "Default")
      (node (ref "IC3") (pin "100") (pinfunction "CN62/RE4_100") (pintype "bidirectional"))
      (node (ref "J8") (pin "8") (pinfunction "8_8") (pintype "passive"))
      (node (ref "Q2") (pin "5") (pinfunction "Q1G_5") (pintype "input"))
      (node (ref "R5") (pin "2") (pinfunction "2_2") (pintype "passive"))
    )
    (net (code "220") (name "VPS_PWR") (class "Default")
      (node (ref "J7") (pin "5") (pinfunction "5_5") (pintype "passive"))
      (node (ref "J9") (pin "5") (pinfunction "5_5") (pintype "passive"))
      (node (ref "Q2") (pin "2") (pinfunction "Q2D1_2") (pintype "bidirectional"))
      (node (ref "Q2") (pin "3") (pinfunction "Q2D2_3") (pintype "bidirectional"))
      (node (ref "R4") (pin "2") (pinfunction "2_2") (pintype "passive"))
    )
    (net (code "221") (name "VPS_SEN") (class "Default")
      (node (ref "IC3") (pin "99") (pinfunction "CN61/RE3_99") (pintype "bidirectional"))
      (node (ref "J8") (pin "3") (pinfunction "3_3") (pintype "passive"))
      (node (ref "R4") (pin "1") (pinfunction "1_1") (pintype "passive"))
      (node (ref "R6") (pin "2") (pinfunction "2_2") (pintype "passive"))
    )
    (net (code "222") (name "VREF2.5") (class "Default")
      (node (ref "C4") (pin "1") (pinfunction "1_1") (pintype "passive"))
      (node (ref "IC1") (pin "2") (pinfunction "VOUT_2") (pintype "output"))
      (node (ref "IC3") (pin "29") (pinfunction "RA10/VR+/CN42_29") (pintype "bidirectional"))
      (node (ref "TP1") (pin "P$1") (pinfunction "TP_P$1") (pintype "passive"))
    )
    (net (code "223") (name "VSOLAR") (class "Default")
      (node (ref "J1") (pin "2") (pinfunction "2_2") (pintype "passive"))
    )
    (net (code "224") (name "XB_RTS") (class "Default")
      (node (ref "IC3") (pin "48") (pinfunction "CN21/RP5/RD15_48") (pintype "bidirectional"))
      (node (ref "J2") (pin "7") (pinfunction "7_7") (pintype "passive"))
    )
    (net (code "225") (name "XB_SLEEP") (class "Default")
      (node (ref "IC3") (pin "22") (pinfunction "RB3/AN3/CN5_22") (pintype "bidirectional"))
      (node (ref "J2") (pin "5") (pinfunction "5_5") (pintype "passive"))
    )
    (net (code "226") (name "unconnected-(B1-+-Pad+2)") (class "Default")
      (node (ref "B1") (pin "+2") (pinfunction "+_+2") (pintype "passive"))
    )
    (net (code "227") (name "unconnected-(IC3-CN18{slash}RP17{slash}RF5-Pad50)") (class "Default")
      (node (ref "IC3") (pin "50") (pinfunction "CN18/RP17/RF5_50") (pintype "bidirectional"))
    )
    (net (code "228") (name "unconnected-(IC3-CN58{slash}RE0-Pad93)") (class "Default")
      (node (ref "IC3") (pin "93") (pinfunction "CN58/RE0_93") (pintype "bidirectional"))
    )
    (net (code "229") (name "unconnected-(IC3-CN72{slash}RPI45{slash}RF6-Pad55)") (class "Default")
      (node (ref "IC3") (pin "55") (pinfunction "CN72/RPI45/RF6_55") (pintype "bidirectional"))
    )
    (net (code "230") (name "unconnected-(IC3-CN75{slash}RPI32{slash}RF12-Pad40)") (class "Default")
      (node (ref "IC3") (pin "40") (pinfunction "CN75/RPI32/RF12_40") (pintype "bidirectional"))
    )
    (net (code "231") (name "unconnected-(IC3-CN76{slash}RP31{slash}RF13-Pad39)") (class "Default")
      (node (ref "IC3") (pin "39") (pinfunction "CN76/RP31/RF13_39") (pintype "bidirectional"))
    )
    (net (code "232") (name "unconnected-(IC3-RA6{slash}CN39-Pad91)") (class "Default")
      (node (ref "IC3") (pin "91") (pinfunction "RA6/CN39_91") (pintype "bidirectional"))
    )
    (net (code "233") (name "unconnected-(IC5-OS-Pad3)") (class "Default")
      (node (ref "IC5") (pin "3") (pinfunction "OS_3") (pintype "output"))
    )
    (net (code "234") (name "unconnected-(IC7-CLKOUT-Pad13)") (class "Default")
      (node (ref "IC7") (pin "13") (pinfunction "CLKOUT_13") (pintype "output"))
    )
    (net (code "235") (name "unconnected-(IC7-TEST-Pad4)") (class "Default")
      (node (ref "IC7") (pin "4") (pinfunction "TEST_4") (pintype "output"))
    )
    (net (code "236") (name "unconnected-(IC18-AVCC-NC-Pad24)") (class "Default")
      (node (ref "IC18") (pin "24") (pinfunction "AVCC-NC_24") (pintype "no_connect"))
    )
    (net (code "237") (name "unconnected-(IC18-GPIO2-Pad13)") (class "Default")
      (node (ref "IC18") (pin "13") (pinfunction "GPIO2_13") (pintype "output"))
    )
    (net (code "238") (name "unconnected-(IC18-GPIO3-Pad14)") (class "Default")
      (node (ref "IC18") (pin "14") (pinfunction "GPIO3_14") (pintype "bidirectional"))
    )
    (net (code "239") (name "unconnected-(IC18-OSCI-Pad27)") (class "Default")
      (node (ref "IC18") (pin "27") (pinfunction "OSCI_27") (pintype "bidirectional"))
    )
    (net (code "240") (name "unconnected-(IC18-OSCO-Pad28)") (class "Default")
      (node (ref "IC18") (pin "28") (pinfunction "OSCO_28") (pintype "output"))
    )
    (net (code "241") (name "unconnected-(IC18-VCC3I-NC-Pad8)") (class "Default")
      (node (ref "IC18") (pin "8") (pinfunction "VCC3I-NC_8") (pintype "no_connect"))
    )
    (net (code "242") (name "unconnected-(IC18-{slash}DCD-Pad10)") (class "Default")
      (node (ref "IC18") (pin "10") (pinfunction "/DCD_10") (pintype "bidirectional"))
    )
    (net (code "243") (name "unconnected-(IC18-{slash}DSR-Pad9)") (class "Default")
      (node (ref "IC18") (pin "9") (pinfunction "/DSR_9") (pintype "bidirectional"))
    )
    (net (code "244") (name "unconnected-(IC18-{slash}DTR-Pad2)") (class "Default")
      (node (ref "IC18") (pin "2") (pinfunction "/DTR_2") (pintype "output"))
    )
    (net (code "245") (name "unconnected-(IC18-{slash}RI-Pad6)") (class "Default")
      (node (ref "IC18") (pin "6") (pinfunction "/RI_6") (pintype "bidirectional"))
    )
    (net (code "246") (name "unconnected-(IC18-{slash}SLEEP-Pad12)") (class "Default")
      (node (ref "IC18") (pin "12") (pinfunction "/SLEEP_12") (pintype "bidirectional"))
    )
    (net (code "247") (name "unconnected-(J3-Pad1)") (class "Default")
      (node (ref "J3") (pin "1") (pinfunction "1_1") (pintype "passive"))
    )
    (net (code "248") (name "unconnected-(J3-Pad2)") (class "Default")
      (node (ref "J3") (pin "2") (pinfunction "2_2") (pintype "passive"))
    )
    (net (code "249") (name "unconnected-(J3-Pad3)") (class "Default")
      (node (ref "J3") (pin "3") (pinfunction "3_3") (pintype "passive"))
    )
    (net (code "250") (name "unconnected-(J3-Pad4)") (class "Default")
      (node (ref "J3") (pin "4") (pinfunction "4_4") (pintype "passive"))
    )
    (net (code "251") (name "unconnected-(J3-Pad6)") (class "Default")
      (node (ref "J3") (pin "6") (pinfunction "6_6") (pintype "passive"))
    )
    (net (code "252") (name "unconnected-(J3-Pad8)") (class "Default")
      (node (ref "J3") (pin "8") (pinfunction "8_8") (pintype "passive"))
    )
    (net (code "253") (name "unconnected-(J3-Pad10)") (class "Default")
      (node (ref "J3") (pin "10") (pinfunction "10_10") (pintype "passive"))
    )
    (net (code "254") (name "unconnected-(J3-Pad11)") (class "Default")
      (node (ref "J3") (pin "11") (pinfunction "11_11") (pintype "passive"))
    )
    (net (code "255") (name "unconnected-(J3-Pad12)") (class "Default")
      (node (ref "J3") (pin "12") (pinfunction "12_12") (pintype "passive"))
    )
    (net (code "256") (name "unconnected-(J3-Pad14)") (class "Default")
      (node (ref "J3") (pin "14") (pinfunction "14_14") (pintype "passive"))
    )
    (net (code "257") (name "unconnected-(J3-Pad16)") (class "Default")
      (node (ref "J3") (pin "16") (pinfunction "16_16") (pintype "passive"))
    )
    (net (code "258") (name "unconnected-(J3-Pad18)") (class "Default")
      (node (ref "J3") (pin "18") (pinfunction "18_18") (pintype "passive"))
    )
    (net (code "259") (name "unconnected-(J3-Pad20)") (class "Default")
      (node (ref "J3") (pin "20") (pinfunction "20_20") (pintype "passive"))
    )
    (net (code "260") (name "unconnected-(J3-Pad22)") (class "Default")
      (node (ref "J3") (pin "22") (pinfunction "22_22") (pintype "passive"))
    )
    (net (code "261") (name "unconnected-(J3-Pad24)") (class "Default")
      (node (ref "J3") (pin "24") (pinfunction "24_24") (pintype "passive"))
    )
    (net (code "262") (name "unconnected-(J10-PadC4)") (class "Default")
      (node (ref "J10") (pin "C4") (pinfunction "C4_C4") (pintype "bidirectional"))
    )
    (net (code "263") (name "unconnected-(J10-PadC6)") (class "Default")
      (node (ref "J10") (pin "C6") (pinfunction "C6_C6") (pintype "bidirectional"))
    )
    (net (code "264") (name "unconnected-(J10-PadC8)") (class "Default")
      (node (ref "J10") (pin "C8") (pinfunction "C8_C8") (pintype "bidirectional"))
    )
    (net (code "265") (name "unconnected-(J40-Pad4)") (class "Default")
      (node (ref "J40") (pin "4") (pinfunction "4_4") (pintype "bidirectional"))
    )
    (net (code "266") (name "unconnected-(J47-Pad7)") (class "Default")
      (node (ref "J47") (pin "7") (pinfunction "7_7") (pintype "passive"))
    )
    (net (code "267") (name "unconnected-(J47-Pad8)") (class "Default")
      (node (ref "J47") (pin "8") (pinfunction "8_8") (pintype "passive"))
    )
    (net (code "268") (name "unconnected-(J47-Pad9)") (class "Default")
      (node (ref "J47") (pin "9") (pinfunction "9_9") (pintype "passive"))
    )
    (net (code "269") (name "unconnected-(J47-Pad10)") (class "Default")
      (node (ref "J47") (pin "10") (pinfunction "10_10") (pintype "passive"))
    )
    (net (code "270") (name "unconnected-(Q3-Pad4)") (class "Default")
      (node (ref "Q3") (pin "4") (pinfunction "4_4") (pintype "passive"))
    )
    (net (code "271") (name "unconnected-(U1-NC-Pad16)") (class "Default")
      (node (ref "U1") (pin "16") (pinfunction "NC_16") (pintype "bidirectional"))
    )
    (net (code "272") (name "unconnected-(U2-AN{slash}O-Pad3)") (class "Default")
      (node (ref "U2") (pin "3") (pinfunction "AN/O_3") (pintype "bidirectional"))
    )
    (net (code "273") (name "unconnected-(U2-PWM-Pad2)") (class "Default")
      (node (ref "U2") (pin "2") (pinfunction "PWM_2") (pintype "bidirectional"))
    )
    (net (code "274") (name "unconnected-(U2-TEMP(NC)-Pad1)") (class "Default")
      (node (ref "U2") (pin "1") (pinfunction "TEMP(NC)_1") (pintype "bidirectional"))
    )
    (net (code "275") (name "unconnected-(U3-ALERT{slash}RDY-Pad2)") (class "Default")
      (node (ref "U3") (pin "2") (pinfunction "ALERT/RDY_2") (pintype "bidirectional"))
    )
    (net (code "276") (name "unconnected-(U8-NC-Pad13)") (class "Default")
      (node (ref "U8") (pin "13") (pinfunction "NC_13") (pintype "no_connect"))
    )
    (net (code "277") (name "unconnected-(X1F-1-Pad5)") (class "Default")
      (node (ref "X1") (pin "5") (pinfunction "1_5") (pintype "passive"))
    )
    (net (code "278") (name "{slash}3.3V1_ON") (class "Default")
      (node (ref "IC3") (pin "95") (pinfunction "CN81/RG14_95") (pintype "bidirectional"))
      (node (ref "Q7") (pin "2") (pinfunction "G_2") (pintype "passive"))
    )
    (net (code "279") (name "{slash}3.3V2_ON") (class "Default")
      (node (ref "IC3") (pin "94") (pinfunction "CN59/RE1_94") (pintype "bidirectional"))
      (node (ref "Q7") (pin "5") (pinfunction "G_5") (pintype "passive"))
    )
    (net (code "280") (name "{slash}3.3V3_ON") (class "Default")
      (node (ref "IC3") (pin "61") (pinfunction "RA5/TDO/CN38_61") (pintype "bidirectional"))
    )
    (net (code "281") (name "{slash}3.3V{slash}7_ON") (class "Default")
      (node (ref "IC3") (pin "96") (pinfunction "CN79/RG12_96") (pintype "bidirectional"))
      (node (ref "Q1") (pin "5") (pinfunction "G_5") (pintype "passive"))
    )
    (net (code "282") (name "{slash}CL_CS1") (class "Default")
      (node (ref "IC3") (pin "1") (pinfunction "CN82/RG15_1") (pintype "bidirectional"))
      (node (ref "J3") (pin "19") (pinfunction "19_19") (pintype "passive"))
    )
    (net (code "283") (name "{slash}CL_CS2") (class "Default")
      (node (ref "IC3") (pin "17") (pinfunction "RA0/TMS_17") (pintype "bidirectional"))
      (node (ref "J1") (pin "7") (pinfunction "7_7") (pintype "passive"))
    )
    (net (code "284") (name "{slash}CTS") (class "Default")
      (node (ref "IC18") (pin "11") (pinfunction "/CTS_11") (pintype "bidirectional"))
      (node (ref "J41") (pin "2") (pinfunction "2_2") (pintype "passive"))
    )
    (net (code "285") (name "{slash}FMEM1_CS") (class "Default")
      (node (ref "IC3") (pin "28") (pinfunction "RA9/VR-/CN41_28") (pintype "bidirectional"))
      (node (ref "IC8") (pin "1") (pinfunction "/S_1") (pintype "input"))
      (node (ref "R24") (pin "2") (pinfunction "2_2") (pintype "passive"))
    )
    (net (code "286") (name "{slash}MCLR") (class "Default")
      (node (ref "IC3") (pin "13") (pinfunction "MCLR_13") (pintype "input"))
      (node (ref "IC4") (pin "4") (pinfunction "GP2/T0CK_4") (pintype "bidirectional"))
      (node (ref "J11") (pin "1") (pinfunction "1_1") (pintype "passive"))
      (node (ref "R14") (pin "1") (pinfunction "1_1") (pintype "passive"))
    )
    (net (code "287") (name "{slash}MCLR2") (class "Default")
      (node (ref "IC4") (pin "6") (pinfunction "GP3/MCLR_6") (pintype "bidirectional"))
      (node (ref "J12") (pin "1") (pinfunction "1_1") (pintype "passive"))
    )
    (net (code "288") (name "{slash}MH_PWR") (class "Default")
      (node (ref "IC3") (pin "97") (pinfunction "CN80/RG13_97") (pintype "bidirectional"))
      (node (ref "Q1") (pin "2") (pinfunction "G_2") (pintype "passive"))
    )
    (net (code "289") (name "{slash}RAM_CS") (class "Default")
      (node (ref "IC3") (pin "3") (pinfunction "CN63/RE5_3") (pintype "bidirectional"))
      (node (ref "J8") (pin "13") (pinfunction "13_13") (pintype "passive"))
    )
    (net (code "290") (name "{slash}RTS") (class "Default")
      (node (ref "IC18") (pin "3") (pinfunction "/RTS_3") (pintype "output"))
      (node (ref "J41") (pin "6") (pinfunction "6_6") (pintype "passive"))
    )
    (net (code "291") (name "{slash}SM_FAULT") (class "Default")
      (node (ref "IC3") (pin "21") (pinfunction "RB4/AN4/CN6/RP28_21") (pintype "bidirectional"))
      (node (ref "U1") (pin "24") (pinfunction "-FAULT_24") (pintype "bidirectional"))
    )
    (net (code "292") (name "{slash}XB_RESET") (class "Default")
      (node (ref "IC3") (pin "18") (pinfunction "RPI33/CN66/RE8_18") (pintype "bidirectional"))
      (node (ref "J2") (pin "6") (pinfunction "6_6") (pintype "passive"))
    )
  )
)
